# -V5_0.net
KiCad netlist of a schematic drawn in Altium Designer
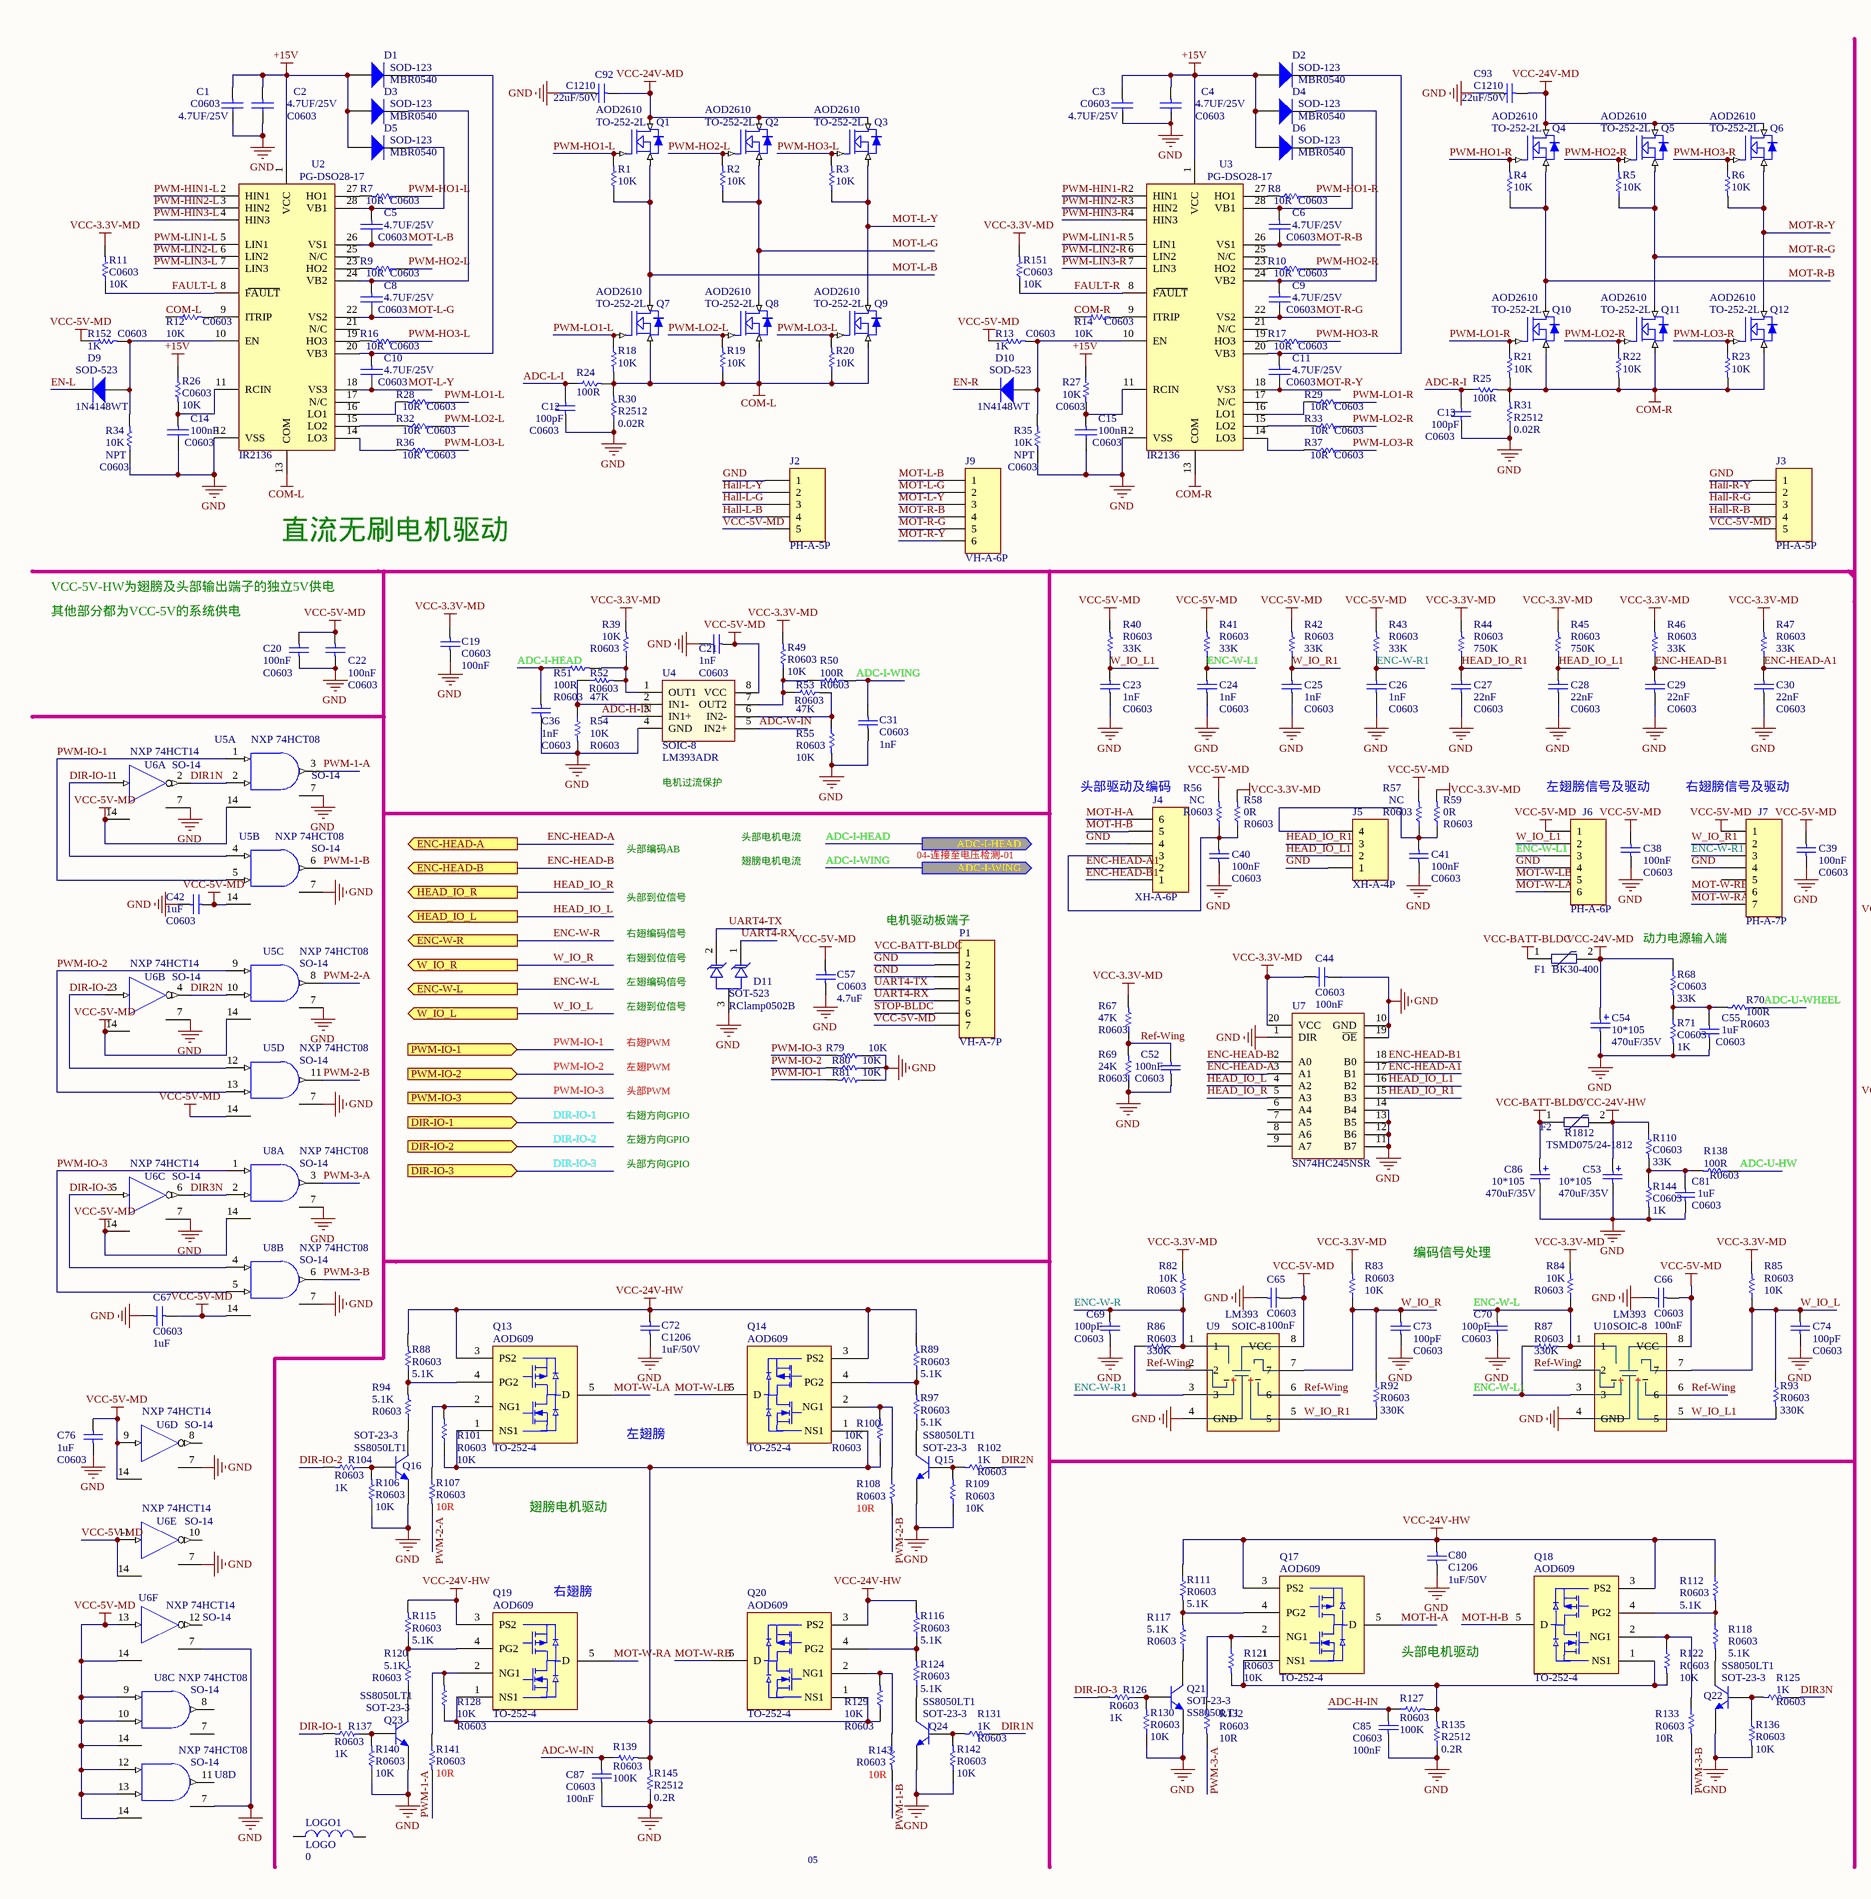
[diagram p0: 电机驱动板-V5.0.SchDoc, left]
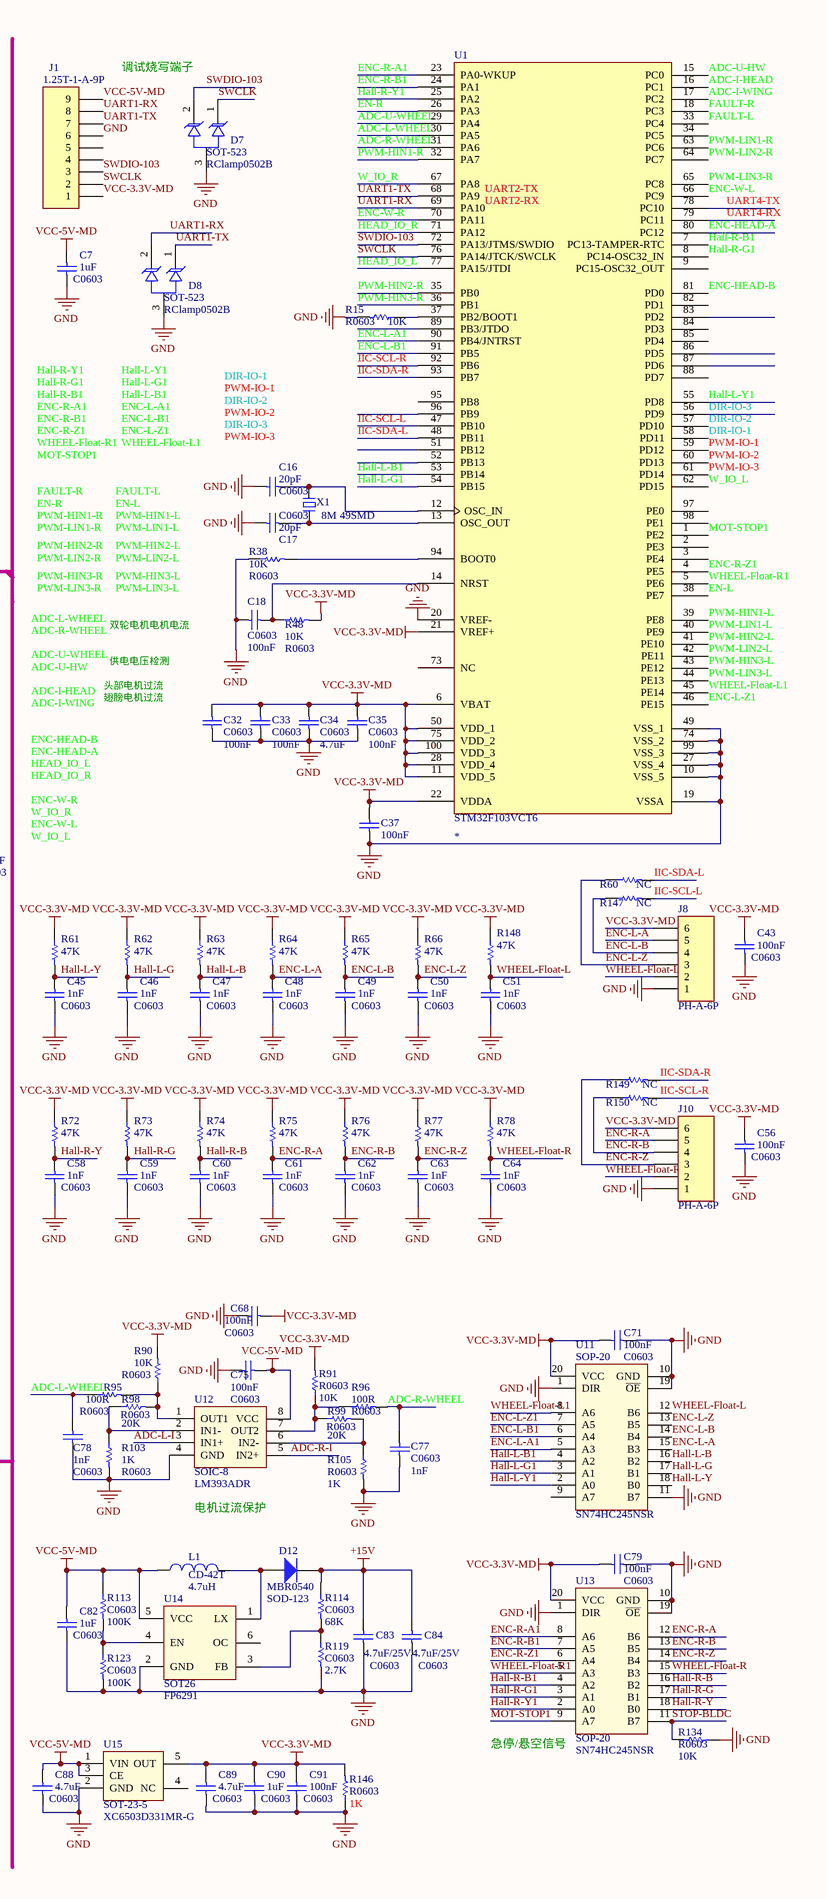
[diagram p1: 电机驱动板-V5.0.SchDoc, right]

(export (version "E")
  (design (tool "Eeschema 10.0.6"))
  (components
    (comp (ref "C1")
      (value "C0603")
      (footprint "C0603_M1608")
      (description "Capacitor")
      (fields (field (name "ALTIUM_VALUE") "4.7UF/25V"))
      (libsource (lib "*") (part "CAP"))
    )
    (comp (ref "C2")
      (value "C0603")
      (footprint "C0603_M1608")
      (description "Capacitor")
      (fields (field (name "ALTIUM_VALUE") "4.7UF/25V"))
      (libsource (lib "*") (part "CAP"))
    )
    (comp (ref "C3")
      (value "C0603")
      (footprint "C0603_M1608")
      (description "Capacitor")
      (fields (field (name "ALTIUM_VALUE") "4.7UF/25V"))
      (libsource (lib "*") (part "CAP"))
    )
    (comp (ref "C4")
      (value "C0603")
      (footprint "C0603_M1608")
      (description "Capacitor")
      (fields (field (name "ALTIUM_VALUE") "4.7UF/25V"))
      (libsource (lib "*") (part "CAP"))
    )
    (comp (ref "C5")
      (value "C0603")
      (footprint "C0603_M1608")
      (description "Capacitor")
      (fields (field (name "ALTIUM_VALUE") "4.7UF/25V"))
      (libsource (lib "*") (part "CAP"))
    )
    (comp (ref "C6")
      (value "C0603")
      (footprint "C0603_M1608")
      (description "Capacitor")
      (fields (field (name "ALTIUM_VALUE") "4.7UF/25V"))
      (libsource (lib "*") (part "CAP"))
    )
    (comp (ref "C7")
      (value "C0603")
      (footprint "C0603_M1608")
      (description "Capacitor")
      (fields (field (name "ALTIUM_VALUE") "1uF"))
      (libsource (lib "Miscellaneous Devices") (part "Cap"))
    )
    (comp (ref "C8")
      (value "C0603")
      (footprint "C0603_M1608")
      (description "Capacitor")
      (fields (field (name "ALTIUM_VALUE") "4.7UF/25V"))
      (libsource (lib "*") (part "CAP"))
    )
    (comp (ref "C9")
      (value "C0603")
      (footprint "C0603_M1608")
      (description "Capacitor")
      (fields (field (name "ALTIUM_VALUE") "4.7UF/25V"))
      (libsource (lib "*") (part "CAP"))
    )
    (comp (ref "C10")
      (value "C0603")
      (footprint "C0603_M1608")
      (description "Capacitor")
      (fields (field (name "ALTIUM_VALUE") "4.7UF/25V"))
      (libsource (lib "*") (part "CAP"))
    )
    (comp (ref "C11")
      (value "C0603")
      (footprint "C0603_M1608")
      (description "Capacitor")
      (fields (field (name "ALTIUM_VALUE") "4.7UF/25V"))
      (libsource (lib "*") (part "CAP"))
    )
    (comp (ref "C12")
      (value "C0603")
      (footprint "C0603_M1608")
      (description "Multilayer Ceramic Capacitor 0603")
      (fields (field (name "ALTIUM_VALUE") "100pF"))
      (libsource (lib "1.电阻、电容、电感原理库") (part "MCC0603"))
    )
    (comp (ref "C13")
      (value "C0603")
      (footprint "C0603_M1608")
      (description "Multilayer Ceramic Capacitor 0603")
      (fields (field (name "ALTIUM_VALUE") "100pF"))
      (libsource (lib "1.电阻、电容、电感原理库") (part "MCC0603"))
    )
    (comp (ref "C14")
      (value "C0603")
      (footprint "C0603_M1608")
      (description "Capacitor")
      (fields (field (name "ALTIUM_VALUE") "100nF"))
      (libsource (lib "*") (part "CAP"))
    )
    (comp (ref "C15")
      (value "C0603")
      (footprint "C0603_M1608")
      (description "Capacitor")
      (fields (field (name "ALTIUM_VALUE") "100nF"))
      (libsource (lib "*") (part "CAP"))
    )
    (comp (ref "C16")
      (value "C0603")
      (footprint "C0603_M1608")
      (description "Multilayer Ceramic Capacitor 0603")
      (fields (field (name "ALTIUM_VALUE") "20pF"))
      (libsource (lib "1.电阻、电容、电感原理库") (part "MCC0603"))
    )
    (comp (ref "C17")
      (value "C0603")
      (footprint "C0603_M1608")
      (description "Multilayer Ceramic Capacitor 0603")
      (fields (field (name "ALTIUM_VALUE") "20pF"))
      (libsource (lib "1.电阻、电容、电感原理库") (part "MCC0603"))
    )
    (comp (ref "C18")
      (value "C0603")
      (footprint "C0603_M1608")
      (description "Multilayer Ceramic Capacitor 0603")
      (fields (field (name "ALTIUM_VALUE") "100nF"))
      (libsource (lib "1.电阻、电容、电感原理库") (part "MCC0603"))
    )
    (comp (ref "C19")
      (value "C0603")
      (footprint "C0603_M1608")
      (description "Multilayer Ceramic Capacitor 0603")
      (fields (field (name "ALTIUM_VALUE") "100nF"))
      (libsource (lib "1.电阻、电容、电感原理库") (part "MCC0603"))
    )
    (comp (ref "C20")
      (value "C0603")
      (footprint "C0603_M1608")
      (description "Multilayer Ceramic Capacitor 0603")
      (fields (field (name "ALTIUM_VALUE") "100nF"))
      (libsource (lib "1.电阻、电容、电感原理库") (part "MCC0603"))
    )
    (comp (ref "C21")
      (value "C0603")
      (footprint "C0603_M1608")
      (description "Multilayer Ceramic Capacitor 0603")
      (fields (field (name "ALTIUM_VALUE") "1nF"))
      (libsource (lib "1.电阻、电容、电感原理库") (part "MCC0603"))
    )
    (comp (ref "C22")
      (value "C0603")
      (footprint "C0603_M1608")
      (description "Multilayer Ceramic Capacitor 0603")
      (fields (field (name "ALTIUM_VALUE") "100nF"))
      (libsource (lib "1.电阻、电容、电感原理库") (part "MCC0603"))
    )
    (comp (ref "C23")
      (value "C0603")
      (footprint "C0603_M1608")
      (description "Multilayer Ceramic Capacitor 0603")
      (fields (field (name "ALTIUM_VALUE") "1nF"))
      (libsource (lib "1.电阻、电容、电感原理库") (part "MCC0603"))
    )
    (comp (ref "C24")
      (value "C0603")
      (footprint "C0603_M1608")
      (description "Multilayer Ceramic Capacitor 0603")
      (fields (field (name "ALTIUM_VALUE") "1nF"))
      (libsource (lib "1.电阻、电容、电感原理库") (part "MCC0603"))
    )
    (comp (ref "C25")
      (value "C0603")
      (footprint "C0603_M1608")
      (description "Multilayer Ceramic Capacitor 0603")
      (fields (field (name "ALTIUM_VALUE") "1nF"))
      (libsource (lib "1.电阻、电容、电感原理库") (part "MCC0603"))
    )
    (comp (ref "C26")
      (value "C0603")
      (footprint "C0603_M1608")
      (description "Multilayer Ceramic Capacitor 0603")
      (fields (field (name "ALTIUM_VALUE") "1nF"))
      (libsource (lib "1.电阻、电容、电感原理库") (part "MCC0603"))
    )
    (comp (ref "C27")
      (value "C0603")
      (footprint "C0603_M1608")
      (description "Multilayer Ceramic Capacitor 0603")
      (fields (field (name "ALTIUM_VALUE") "22nF"))
      (libsource (lib "1.电阻、电容、电感原理库") (part "MCC0603"))
    )
    (comp (ref "C28")
      (value "C0603")
      (footprint "C0603_M1608")
      (description "Multilayer Ceramic Capacitor 0603")
      (fields (field (name "ALTIUM_VALUE") "22nF"))
      (libsource (lib "1.电阻、电容、电感原理库") (part "MCC0603"))
    )
    (comp (ref "C29")
      (value "C0603")
      (footprint "C0603_M1608")
      (description "Multilayer Ceramic Capacitor 0603")
      (fields (field (name "ALTIUM_VALUE") "22nF"))
      (libsource (lib "1.电阻、电容、电感原理库") (part "MCC0603"))
    )
    (comp (ref "C30")
      (value "C0603")
      (footprint "C0603_M1608")
      (description "Multilayer Ceramic Capacitor 0603")
      (fields (field (name "ALTIUM_VALUE") "22nF"))
      (libsource (lib "1.电阻、电容、电感原理库") (part "MCC0603"))
    )
    (comp (ref "C31")
      (value "C0603")
      (footprint "C0603_M1608")
      (description "Multilayer Ceramic Capacitor 0603")
      (fields (field (name "ALTIUM_VALUE") "1nF"))
      (libsource (lib "1.电阻、电容、电感原理库") (part "MCC0603"))
    )
    (comp (ref "C32")
      (value "C0603")
      (footprint "C0603_M1608")
      (description "Multilayer Ceramic Capacitor 0603")
      (fields (field (name "ALTIUM_VALUE") "100nF"))
      (libsource (lib "1.电阻、电容、电感原理库") (part "MCC0603"))
    )
    (comp (ref "C33")
      (value "C0603")
      (footprint "C0603_M1608")
      (description "Multilayer Ceramic Capacitor 0603")
      (fields (field (name "ALTIUM_VALUE") "100nF"))
      (libsource (lib "1.电阻、电容、电感原理库") (part "MCC0603"))
    )
    (comp (ref "C34")
      (value "C0603")
      (footprint "C0603_M1608")
      (description "Multilayer Ceramic Capacitor 0603")
      (fields (field (name "ALTIUM_VALUE") "4.7uF"))
      (libsource (lib "1.电阻、电容、电感原理库") (part "MCC0603"))
    )
    (comp (ref "C35")
      (value "C0603")
      (footprint "C0603_M1608")
      (description "Multilayer Ceramic Capacitor 0603")
      (fields (field (name "ALTIUM_VALUE") "100nF"))
      (libsource (lib "1.电阻、电容、电感原理库") (part "MCC0603"))
    )
    (comp (ref "C36")
      (value "C0603")
      (footprint "C0603_M1608")
      (description "Multilayer Ceramic Capacitor 0603")
      (fields (field (name "ALTIUM_VALUE") "1nF"))
      (libsource (lib "1.电阻、电容、电感原理库") (part "MCC0603"))
    )
    (comp (ref "C37")
      (value "100nF")
      (footprint "C0603_M1608")
      (description "Capacitor")
      (fields (field (name "Comment") "C0603"))
      (libsource (lib "") (part "Cap_1"))
    )
    (comp (ref "C38")
      (value "C0603")
      (footprint "C0603_M1608")
      (description "Multilayer Ceramic Capacitor 0603")
      (fields (field (name "ALTIUM_VALUE") "100nF"))
      (libsource (lib "1.电阻、电容、电感原理库") (part "MCC0603"))
    )
    (comp (ref "C39")
      (value "C0603")
      (footprint "C0603_M1608")
      (description "Multilayer Ceramic Capacitor 0603")
      (fields (field (name "ALTIUM_VALUE") "100nF"))
      (libsource (lib "1.电阻、电容、电感原理库") (part "MCC0603"))
    )
    (comp (ref "C40")
      (value "C0603")
      (footprint "C0603_M1608")
      (description "Multilayer Ceramic Capacitor 0603")
      (fields (field (name "ALTIUM_VALUE") "100nF"))
      (libsource (lib "1.电阻、电容、电感原理库") (part "MCC0603"))
    )
    (comp (ref "C41")
      (value "C0603")
      (footprint "C0603_M1608")
      (description "Multilayer Ceramic Capacitor 0603")
      (fields (field (name "ALTIUM_VALUE") "100nF"))
      (libsource (lib "1.电阻、电容、电感原理库") (part "MCC0603"))
    )
    (comp (ref "C42")
      (value "C0603")
      (footprint "C0603_M1608")
      (description "Capacitor")
      (fields (field (name "ALTIUM_VALUE") "1uF") (field (name "PUBLISHER") "Altium Limited"))
      (libsource (lib "Miscellaneous Devices") (part "Cap"))
    )
    (comp (ref "C43")
      (value "C0603")
      (footprint "C0603_M1608")
      (description "Multilayer Ceramic Capacitor 0603")
      (fields (field (name "ALTIUM_VALUE") "100nF"))
      (libsource (lib "1.电阻、电容、电感原理库") (part "MCC0603"))
    )
    (comp (ref "C44")
      (value "C0603")
      (footprint "C0603_M1608")
      (description "Multilayer Ceramic Capacitor 0603")
      (fields (field (name "ALTIUM_VALUE") "100nF"))
      (libsource (lib "1.电阻、电容、电感原理库") (part "MCC0603"))
    )
    (comp (ref "C45")
      (value "C0603")
      (footprint "C0603_M1608")
      (description "Multilayer Ceramic Capacitor 0603")
      (fields (field (name "ALTIUM_VALUE") "1nF"))
      (libsource (lib "1.电阻、电容、电感原理库") (part "MCC0603"))
    )
    (comp (ref "C46")
      (value "C0603")
      (footprint "C0603_M1608")
      (description "Multilayer Ceramic Capacitor 0603")
      (fields (field (name "ALTIUM_VALUE") "1nF"))
      (libsource (lib "1.电阻、电容、电感原理库") (part "MCC0603"))
    )
    (comp (ref "C47")
      (value "C0603")
      (footprint "C0603_M1608")
      (description "Multilayer Ceramic Capacitor 0603")
      (fields (field (name "ALTIUM_VALUE") "1nF"))
      (libsource (lib "1.电阻、电容、电感原理库") (part "MCC0603"))
    )
    (comp (ref "C48")
      (value "C0603")
      (footprint "C0603_M1608")
      (description "Multilayer Ceramic Capacitor 0603")
      (fields (field (name "ALTIUM_VALUE") "1nF"))
      (libsource (lib "1.电阻、电容、电感原理库") (part "MCC0603"))
    )
    (comp (ref "C49")
      (value "C0603")
      (footprint "C0603_M1608")
      (description "Multilayer Ceramic Capacitor 0603")
      (fields (field (name "ALTIUM_VALUE") "1nF"))
      (libsource (lib "1.电阻、电容、电感原理库") (part "MCC0603"))
    )
    (comp (ref "C50")
      (value "C0603")
      (footprint "C0603_M1608")
      (description "Multilayer Ceramic Capacitor 0603")
      (fields (field (name "ALTIUM_VALUE") "1nF"))
      (libsource (lib "1.电阻、电容、电感原理库") (part "MCC0603"))
    )
    (comp (ref "C51")
      (value "C0603")
      (footprint "C0603_M1608")
      (description "Multilayer Ceramic Capacitor 0603")
      (fields (field (name "ALTIUM_VALUE") "1nF"))
      (libsource (lib "1.电阻、电容、电感原理库") (part "MCC0603"))
    )
    (comp (ref "C52")
      (value "C0603")
      (footprint "C0603_M1608")
      (description "Multilayer Ceramic Capacitor 0603")
      (fields (field (name "ALTIUM_VALUE") "100nF"))
      (libsource (lib "1.电阻、电容、电感原理库") (part "MCC0603"))
    )
    (comp (ref "C53")
      (value "10*105")
      (footprint "CAP_SMD_10*105")
      (description "SMD Capacitor 10*105")
      (fields (field (name "ALTIUM_VALUE") "470uF/35V"))
      (libsource (lib "1.电阻、电容、电感原理库") (part "CAP_SMD_10*105"))
    )
    (comp (ref "C54")
      (value "10*105")
      (footprint "CAP_SMD_10*105")
      (description "SMD Capacitor 10*105")
      (fields (field (name "ALTIUM_VALUE") "470uF/35V"))
      (libsource (lib "1.电阻、电容、电感原理库") (part "CAP_SMD_10*105"))
    )
    (comp (ref "C55")
      (value "C0603")
      (footprint "C0603_M1608")
      (description "Multilayer Ceramic Capacitor 0603")
      (fields (field (name "ALTIUM_VALUE") "1uF"))
      (libsource (lib "1.电阻、电容、电感原理库") (part "MCC0603"))
    )
    (comp (ref "C56")
      (value "C0603")
      (footprint "C0603_M1608")
      (description "Multilayer Ceramic Capacitor 0603")
      (fields (field (name "ALTIUM_VALUE") "100nF"))
      (libsource (lib "1.电阻、电容、电感原理库") (part "MCC0603"))
    )
    (comp (ref "C57")
      (value "C0603")
      (footprint "C0603_M1608")
      (description "Capacitor")
      (fields (field (name "ALTIUM_VALUE") "4.7uF"))
      (libsource (lib "Miscellaneous Devices") (part "Cap"))
    )
    (comp (ref "C58")
      (value "C0603")
      (footprint "C0603_M1608")
      (description "Multilayer Ceramic Capacitor 0603")
      (fields (field (name "ALTIUM_VALUE") "1nF"))
      (libsource (lib "1.电阻、电容、电感原理库") (part "MCC0603"))
    )
    (comp (ref "C59")
      (value "C0603")
      (footprint "C0603_M1608")
      (description "Multilayer Ceramic Capacitor 0603")
      (fields (field (name "ALTIUM_VALUE") "1nF"))
      (libsource (lib "1.电阻、电容、电感原理库") (part "MCC0603"))
    )
    (comp (ref "C60")
      (value "C0603")
      (footprint "C0603_M1608")
      (description "Multilayer Ceramic Capacitor 0603")
      (fields (field (name "ALTIUM_VALUE") "1nF"))
      (libsource (lib "1.电阻、电容、电感原理库") (part "MCC0603"))
    )
    (comp (ref "C61")
      (value "C0603")
      (footprint "C0603_M1608")
      (description "Multilayer Ceramic Capacitor 0603")
      (fields (field (name "ALTIUM_VALUE") "1nF"))
      (libsource (lib "1.电阻、电容、电感原理库") (part "MCC0603"))
    )
    (comp (ref "C62")
      (value "C0603")
      (footprint "C0603_M1608")
      (description "Multilayer Ceramic Capacitor 0603")
      (fields (field (name "ALTIUM_VALUE") "1nF"))
      (libsource (lib "1.电阻、电容、电感原理库") (part "MCC0603"))
    )
    (comp (ref "C63")
      (value "C0603")
      (footprint "C0603_M1608")
      (description "Multilayer Ceramic Capacitor 0603")
      (fields (field (name "ALTIUM_VALUE") "1nF"))
      (libsource (lib "1.电阻、电容、电感原理库") (part "MCC0603"))
    )
    (comp (ref "C64")
      (value "C0603")
      (footprint "C0603_M1608")
      (description "Multilayer Ceramic Capacitor 0603")
      (fields (field (name "ALTIUM_VALUE") "1nF"))
      (libsource (lib "1.电阻、电容、电感原理库") (part "MCC0603"))
    )
    (comp (ref "C65")
      (value "C0603")
      (footprint "C0603_M1608")
      (description "Multilayer Ceramic Capacitor 0603")
      (fields (field (name "ALTIUM_VALUE") "100nF"))
      (libsource (lib "1.电阻、电容、电感原理库") (part "MCC0603"))
    )
    (comp (ref "C66")
      (value "C0603")
      (footprint "C0603_M1608")
      (description "Multilayer Ceramic Capacitor 0603")
      (fields (field (name "ALTIUM_VALUE") "100nF"))
      (libsource (lib "1.电阻、电容、电感原理库") (part "MCC0603"))
    )
    (comp (ref "C67")
      (value "C0603")
      (footprint "C0603_M1608")
      (description "Capacitor")
      (fields (field (name "ALTIUM_VALUE") "1uF") (field (name "PUBLISHER") "Altium Limited"))
      (libsource (lib "Miscellaneous Devices") (part "Cap"))
    )
    (comp (ref "C68")
      (value "C0603")
      (footprint "C0603_M1608")
      (description "Multilayer Ceramic Capacitor 0603")
      (fields (field (name "ALTIUM_VALUE") "100nF"))
      (libsource (lib "1.电阻、电容、电感原理库") (part "MCC0603"))
    )
    (comp (ref "C69")
      (value "C0603")
      (footprint "C0603_M1608")
      (description "Multilayer Ceramic Capacitor 0603")
      (fields (field (name "ALTIUM_VALUE") "100pF"))
      (libsource (lib "1.电阻、电容、电感原理库") (part "MCC0603"))
    )
    (comp (ref "C70")
      (value "C0603")
      (footprint "C0603_M1608")
      (description "Multilayer Ceramic Capacitor 0603")
      (fields (field (name "ALTIUM_VALUE") "100pF"))
      (libsource (lib "1.电阻、电容、电感原理库") (part "MCC0603"))
    )
    (comp (ref "C71")
      (value "C0603")
      (footprint "C0603_M1608")
      (description "Multilayer Ceramic Capacitor 0603")
      (fields (field (name "ALTIUM_VALUE") "100nF"))
      (libsource (lib "1.电阻、电容、电感原理库") (part "MCC0603"))
    )
    (comp (ref "C72")
      (value "C1206")
      (footprint "C1206_M3216")
      (description "Multilayer Ceramic Capacitor 1206")
      (fields (field (name "ALTIUM_VALUE") "1uF/50V"))
      (libsource (lib "1.电阻、电容、电感原理库") (part "MCC1206"))
    )
    (comp (ref "C73")
      (value "C0603")
      (footprint "C0603_M1608")
      (description "Multilayer Ceramic Capacitor 0603")
      (fields (field (name "ALTIUM_VALUE") "100pF"))
      (libsource (lib "1.电阻、电容、电感原理库") (part "MCC0603"))
    )
    (comp (ref "C74")
      (value "C0603")
      (footprint "C0603_M1608")
      (description "Multilayer Ceramic Capacitor 0603")
      (fields (field (name "ALTIUM_VALUE") "100pF"))
      (libsource (lib "1.电阻、电容、电感原理库") (part "MCC0603"))
    )
    (comp (ref "C75")
      (value "C0603")
      (footprint "C0603_M1608")
      (description "Multilayer Ceramic Capacitor 0603")
      (fields (field (name "ALTIUM_VALUE") "100nF"))
      (libsource (lib "1.电阻、电容、电感原理库") (part "MCC0603"))
    )
    (comp (ref "C76")
      (value "C0603")
      (footprint "C0603_M1608")
      (description "Capacitor")
      (fields (field (name "ALTIUM_VALUE") "1uF") (field (name "PUBLISHER") "Altium Limited"))
      (libsource (lib "Miscellaneous Devices") (part "Cap"))
    )
    (comp (ref "C77")
      (value "C0603")
      (footprint "C0603_M1608")
      (description "Multilayer Ceramic Capacitor 0603")
      (fields (field (name "ALTIUM_VALUE") "1nF"))
      (libsource (lib "1.电阻、电容、电感原理库") (part "MCC0603"))
    )
    (comp (ref "C78")
      (value "C0603")
      (footprint "C0603_M1608")
      (description "Multilayer Ceramic Capacitor 0603")
      (fields (field (name "ALTIUM_VALUE") "1nF"))
      (libsource (lib "1.电阻、电容、电感原理库") (part "MCC0603"))
    )
    (comp (ref "C79")
      (value "C0603")
      (footprint "C0603_M1608")
      (description "Multilayer Ceramic Capacitor 0603")
      (fields (field (name "ALTIUM_VALUE") "100nF"))
      (libsource (lib "1.电阻、电容、电感原理库") (part "MCC0603"))
    )
    (comp (ref "C80")
      (value "C1206")
      (footprint "C1206_M3216")
      (description "Multilayer Ceramic Capacitor 1206")
      (fields (field (name "ALTIUM_VALUE") "1uF/50V"))
      (libsource (lib "1.电阻、电容、电感原理库") (part "MCC1206"))
    )
    (comp (ref "C81")
      (value "C0603")
      (footprint "C0603_M1608")
      (description "Multilayer Ceramic Capacitor 0603")
      (fields (field (name "ALTIUM_VALUE") "1uF"))
      (libsource (lib "1.电阻、电容、电感原理库") (part "MCC0603"))
    )
    (comp (ref "C82")
      (value "C0603")
      (footprint "C0603_M1608")
      (description "Multilayer Ceramic Capacitor 0603")
      (fields (field (name "ALTIUM_VALUE") "1uF"))
      (libsource (lib "1.电阻、电容、电感原理库") (part "MCC0603"))
    )
    (comp (ref "C83")
      (value "C0603")
      (footprint "C0603_M1608")
      (description "Capacitor")
      (fields (field (name "ALTIUM_VALUE") "4.7uF/25V") (field (name "PUBLISHER") "Altium Limited"))
      (libsource (lib "Miscellaneous Devices") (part "Cap"))
    )
    (comp (ref "C84")
      (value "C0603")
      (footprint "C0603_M1608")
      (description "Capacitor")
      (fields (field (name "ALTIUM_VALUE") "4.7uF/25V"))
      (libsource (lib "Miscellaneous Devices") (part "Cap"))
    )
    (comp (ref "C85")
      (value "C0603")
      (footprint "C0603_M1608")
      (description "Capacitor")
      (fields (field (name "ALTIUM_VALUE") "100nF") (field (name "PUBLISHER") "Altium Limited"))
      (libsource (lib "Miscellaneous Devices") (part "Cap"))
    )
    (comp (ref "C86")
      (value "10*105")
      (footprint "CAP_SMD_10*105")
      (description "SMD Capacitor 10*105")
      (fields (field (name "ALTIUM_VALUE") "470uF/35V"))
      (libsource (lib "1.电阻、电容、电感原理库") (part "CAP_SMD_10*105"))
    )
    (comp (ref "C87")
      (value "C0603")
      (footprint "C0603_M1608")
      (description "Capacitor")
      (fields (field (name "ALTIUM_VALUE") "100nF") (field (name "PUBLISHER") "Altium Limited"))
      (libsource (lib "Miscellaneous Devices") (part "Cap"))
    )
    (comp (ref "C88")
      (value "C0603")
      (footprint "C0603_M1608")
      (description "Capacitor")
      (fields (field (name "ALTIUM_VALUE") "4.7uF") (field (name "PUBLISHER") "Altium Limited"))
      (libsource (lib "Miscellaneous Devices") (part "Cap"))
    )
    (comp (ref "C89")
      (value "C0603")
      (footprint "C0603_M1608")
      (description "Capacitor")
      (fields (field (name "ALTIUM_VALUE") "4.7uF"))
      (libsource (lib "Miscellaneous Devices") (part "Cap"))
    )
    (comp (ref "C90")
      (value "C0603")
      (footprint "C0603_M1608")
      (description "Capacitor")
      (fields (field (name "ALTIUM_VALUE") "1uF"))
      (libsource (lib "Miscellaneous Devices") (part "Cap"))
    )
    (comp (ref "C91")
      (value "C0603")
      (footprint "C0603_M1608")
      (description "Capacitor")
      (fields (field (name "ALTIUM_VALUE") "100nF"))
      (libsource (lib "Miscellaneous Devices") (part "Cap"))
    )
    (comp (ref "C92")
      (value "C1210")
      (footprint "C1210_M3225")
      (description "Multilayer Ceramic Capacitor 0603")
      (fields (field (name "ALTIUM_VALUE") "22uF/50V"))
      (libsource (lib "1.电阻、电容、电感原理库") (part "MCC0603"))
    )
    (comp (ref "C93")
      (value "C1210")
      (footprint "C1210_M3225")
      (description "Multilayer Ceramic Capacitor 0603")
      (fields (field (name "ALTIUM_VALUE") "22uF/50V"))
      (libsource (lib "1.电阻、电容、电感原理库") (part "MCC0603"))
    )
    (comp (ref "D1")
      (value "SOD-123")
      (footprint "SOD-123")
      (description "Default Diode")
      (fields (field (name "ALTIUM_VALUE") "MBR0540") (field (name "PUBLISHER") "Altium Limited"))
      (libsource (lib "Miscellaneous Devices") (part "Diode"))
    )
    (comp (ref "D2")
      (value "SOD-123")
      (footprint "SOD-123")
      (description "Default Diode")
      (fields (field (name "ALTIUM_VALUE") "MBR0540") (field (name "PUBLISHER") "Altium Limited"))
      (libsource (lib "Miscellaneous Devices") (part "Diode"))
    )
    (comp (ref "D3")
      (value "SOD-123")
      (footprint "SOD-123")
      (description "Default Diode")
      (fields (field (name "ALTIUM_VALUE") "MBR0540") (field (name "PUBLISHER") "Altium Limited"))
      (libsource (lib "Miscellaneous Devices") (part "Diode"))
    )
    (comp (ref "D4")
      (value "SOD-123")
      (footprint "SOD-123")
      (description "Default Diode")
      (fields (field (name "ALTIUM_VALUE") "MBR0540") (field (name "PUBLISHER") "Altium Limited"))
      (libsource (lib "Miscellaneous Devices") (part "Diode"))
    )
    (comp (ref "D5")
      (value "SOD-123")
      (footprint "SOD-123")
      (description "Default Diode")
      (fields (field (name "ALTIUM_VALUE") "MBR0540") (field (name "PUBLISHER") "Altium Limited"))
      (libsource (lib "Miscellaneous Devices") (part "Diode"))
    )
    (comp (ref "D6")
      (value "SOD-123")
      (footprint "SOD-123")
      (description "Default Diode")
      (fields (field (name "ALTIUM_VALUE") "MBR0540") (field (name "PUBLISHER") "Altium Limited"))
      (libsource (lib "Miscellaneous Devices") (part "Diode"))
    )
    (comp (ref "D7")
      (value "SOT-523")
      (footprint "SOT-523")
      (description "Ultra-Low Capacitance TVS for ESD and CDE Protection")
      (fields (field (name "ALTIUM_VALUE") "RClamp0502B"))
      (libsource (lib "2.二极管原理库") (part "RClamp0502B"))
    )
    (comp (ref "D8")
      (value "SOT-523")
      (footprint "SOT-523")
      (description "Ultra-Low Capacitance TVS for ESD and CDE Protection")
      (fields (field (name "ALTIUM_VALUE") "RClamp0502B"))
      (libsource (lib "2.二极管原理库") (part "RClamp0502B"))
    )
    (comp (ref "D9")
      (value "SOD-523")
      (footprint "SOD-523")
      (description "FAST SWITCHING DIODES")
      (fields (field (name "ALTIUM_VALUE") "1N4148WT"))
      (libsource (lib "2.二极管原理库") (part "1N4148WT"))
    )
    (comp (ref "D10")
      (value "SOD-523")
      (footprint "SOD-523")
      (description "FAST SWITCHING DIODES")
      (fields (field (name "ALTIUM_VALUE") "1N4148WT"))
      (libsource (lib "2.二极管原理库") (part "1N4148WT"))
    )
    (comp (ref "D11")
      (value "SOT-523")
      (footprint "SOT-523")
      (description "Ultra-Low Capacitance TVS for ESD and CDE Protection")
      (fields (field (name "ALTIUM_VALUE") "RClamp0502B"))
      (libsource (lib "2.二极管原理库") (part "RClamp0502B"))
    )
    (comp (ref "D12")
      (value "SOD-123")
      (footprint "SOD-123")
      (description "Default Diode")
      (fields (field (name "ALTIUM_VALUE") "MBR0540") (field (name "PUBLISHER") "Altium Limited"))
      (libsource (lib "Miscellaneous Devices") (part "Diode"))
    )
    (comp (ref "F1") (value "BK30-400") (footprint "FUSE-FRG-5MM") (libsource (lib "SCH") (part "PPTC")))
    (comp (ref "F2")
      (value "R1812")
      (footprint "R1812_M4532")
      (fields (field (name "ALTIUM_VALUE") "TSMD075/24-1812"))
      (libsource (lib "SCH") (part "PPTC"))
    )
    (comp (ref "J1")
      (value "1.25T-1-A-9P")
      (footprint "1.25T-1-A-9P")
      (description "Header, 1.25mm,9-Pin")
      (libsource (lib "7.PH XH VH KF2510连接器原理库") (part "1.25T-1-A-9P"))
    )
    (comp (ref "J2")
      (value "PH-A-5P")
      (footprint "PH-A-5P")
      (description "Header, 2.0mm,5-Pin")
      (libsource (lib "7.PH XH VH KF2510连接器原理库") (part "PH-A-5P"))
    )
    (comp (ref "J3")
      (value "PH-A-5P")
      (footprint "PH-A-5P")
      (description "Header, 2.0mm,5-Pin")
      (libsource (lib "7.PH XH VH KF2510连接器原理库") (part "PH-A-5P"))
    )
    (comp (ref "J4")
      (value "XH-A-6P")
      (footprint "XH-A-6P")
      (description "Header, 2.5mm,6-Pin")
      (libsource (lib "7.PH XH VH KF2510连接器原理库") (part "XH-A-6P"))
    )
    (comp (ref "J5")
      (value "XH-A-4P")
      (footprint "XH-A-4P")
      (description "Header, 2.5mm,4-Pin")
      (libsource (lib "7.PH XH VH KF2510连接器原理库") (part "XH-A-4P"))
    )
    (comp (ref "J6")
      (value "PH-A-6P")
      (footprint "PH-A-6P")
      (description "Header, 2.0mm,6-Pin")
      (libsource (lib "") (part "PH-A-6P_1"))
    )
    (comp (ref "J7")
      (value "PH-A-7P")
      (footprint "PH-A-7P")
      (description "Header, 2.0mm,7-Pin")
      (libsource (lib "7.PH XH VH KF2510连接器原理库") (part "PH-A-7P"))
    )
    (comp (ref "J8")
      (value "PH-A-6P")
      (footprint "PH-A-6P")
      (description "Header, 2.0mm,6-Pin")
      (libsource (lib "7.PH XH VH KF2510连接器原理库") (part "PH-A-6P"))
    )
    (comp (ref "J9")
      (value "VH-A-6P")
      (footprint "VH-A-6P")
      (description "Header, 3.96mm,6-Pin")
      (libsource (lib "7.PH XH VH KF2510连接器原理库") (part "VH-A-6P"))
    )
    (comp (ref "J10")
      (value "PH-A-6P")
      (footprint "PH-A-6P")
      (description "Header, 2.0mm,6-Pin")
      (libsource (lib "7.PH XH VH KF2510连接器原理库") (part "PH-A-6P"))
    )
    (comp (ref "L1")
      (value "CD-42T")
      (footprint "CD-42T")
      (description "Inductor")
      (fields (field (name "ALTIUM_VALUE") "4.7uH"))
      (libsource (lib "1.电阻、电容、电感原理库") (part "L3*3*2-3A"))
    )
    (comp (ref "LOGO1")
      (value "LOGO")
      (footprint "LOGO")
      (description "Inductor CD54 Type")
      (fields (field (name "ALTIUM_VALUE") "0"))
      (libsource (lib "1.电阻、电容、电感原理库") (part "L-CD54"))
    )
    (comp (ref "P1")
      (value "VH-A-7P")
      (footprint "VH-A-7P")
      (description "Header, 3.96mm,7-Pin")
      (libsource (lib "7.PH XH VH KF2510连接器原理库") (part "VH-A-7P"))
    )
    (comp (ref "Q1")
      (value "TO-252-2L")
      (footprint "TO-252-2L")
      (fields (field (name "ALTIUM_VALUE") "AOD2610"))
      (libsource (lib "SCH-S") (part "MOSN_1"))
    )
    (comp (ref "Q2")
      (value "TO-252-2L")
      (footprint "TO-252-2L")
      (fields (field (name "ALTIUM_VALUE") "AOD2610"))
      (libsource (lib "SCH-S") (part "MOSN_1"))
    )
    (comp (ref "Q3")
      (value "TO-252-2L")
      (footprint "TO-252-2L")
      (fields (field (name "ALTIUM_VALUE") "AOD2610"))
      (libsource (lib "SCH-S") (part "MOSN_1"))
    )
    (comp (ref "Q4")
      (value "TO-252-2L")
      (footprint "TO-252-2L")
      (fields (field (name "ALTIUM_VALUE") "AOD2610"))
      (libsource (lib "SCH-S") (part "MOSN_1"))
    )
    (comp (ref "Q5")
      (value "TO-252-2L")
      (footprint "TO-252-2L")
      (fields (field (name "ALTIUM_VALUE") "AOD2610"))
      (libsource (lib "SCH-S") (part "MOSN_1"))
    )
    (comp (ref "Q6")
      (value "TO-252-2L")
      (footprint "TO-252-2L")
      (fields (field (name "ALTIUM_VALUE") "AOD2610"))
      (libsource (lib "SCH-S") (part "MOSN_1"))
    )
    (comp (ref "Q7")
      (value "TO-252-2L")
      (footprint "TO-252-2L")
      (fields (field (name "ALTIUM_VALUE") "AOD2610"))
      (libsource (lib "SCH-S") (part "MOSN_1"))
    )
    (comp (ref "Q8")
      (value "TO-252-2L")
      (footprint "TO-252-2L")
      (fields (field (name "ALTIUM_VALUE") "AOD2610"))
      (libsource (lib "SCH-S") (part "MOSN_1"))
    )
    (comp (ref "Q9")
      (value "TO-252-2L")
      (footprint "TO-252-2L")
      (fields (field (name "ALTIUM_VALUE") "AOD2610"))
      (libsource (lib "SCH-S") (part "MOSN_1"))
    )
    (comp (ref "Q10")
      (value "TO-252-2L")
      (footprint "TO-252-2L")
      (fields (field (name "ALTIUM_VALUE") "AOD2610"))
      (libsource (lib "SCH-S") (part "MOSN_1"))
    )
    (comp (ref "Q11")
      (value "TO-252-2L")
      (footprint "TO-252-2L")
      (fields (field (name "ALTIUM_VALUE") "AOD2610"))
      (libsource (lib "SCH-S") (part "MOSN_1"))
    )
    (comp (ref "Q12")
      (value "TO-252-2L")
      (footprint "TO-252-2L")
      (fields (field (name "ALTIUM_VALUE") "AOD2610"))
      (libsource (lib "SCH-S") (part "MOSN_1"))
    )
    (comp (ref "Q13")
      (value "TO-252-4")
      (footprint "TO-252-4L")
      (fields (field (name "ALTIUM_VALUE") "AOD609"))
      (libsource (lib "CYSchlib") (part "MOS-DUAL-N/P"))
    )
    (comp (ref "Q14")
      (value "TO-252-4")
      (footprint "TO-252-4L")
      (fields (field (name "ALTIUM_VALUE") "AOD609"))
      (libsource (lib "") (part "MOS-DUAL-N/P_1"))
    )
    (comp (ref "Q15")
      (value "SOT-23-3")
      (footprint "SOT-23-3")
      (description "NPN Bipolar Transistor")
      (fields (field (name "ALTIUM_VALUE") "SS8050LT1"))
      (libsource (lib "3.三极管原理库") (part "SS8050LT1"))
    )
    (comp (ref "Q16")
      (value "SOT-23-3")
      (footprint "SOT-23-3")
      (description "NPN Bipolar Transistor")
      (fields (field (name "ALTIUM_VALUE") "SS8050LT1"))
      (libsource (lib "3.三极管原理库") (part "SS8050LT1"))
    )
    (comp (ref "Q17")
      (value "TO-252-4")
      (footprint "TO-252-4L")
      (fields (field (name "ALTIUM_VALUE") "AOD609"))
      (libsource (lib "CYSchlib") (part "MOS-DUAL-N/P"))
    )
    (comp (ref "Q18")
      (value "TO-252-4")
      (footprint "TO-252-4L")
      (fields (field (name "ALTIUM_VALUE") "AOD609"))
      (libsource (lib "") (part "MOS-DUAL-N/P_1"))
    )
    (comp (ref "Q19")
      (value "TO-252-4")
      (footprint "TO-252-4L")
      (fields (field (name "ALTIUM_VALUE") "AOD609"))
      (libsource (lib "CYSchlib") (part "MOS-DUAL-N/P"))
    )
    (comp (ref "Q20")
      (value "TO-252-4")
      (footprint "TO-252-4L")
      (fields (field (name "ALTIUM_VALUE") "AOD609"))
      (libsource (lib "") (part "MOS-DUAL-N/P_1"))
    )
    (comp (ref "Q21")
      (value "SOT-23-3")
      (footprint "SOT-23-3")
      (description "NPN Bipolar Transistor")
      (fields (field (name "ALTIUM_VALUE") "SS8050LT1"))
      (libsource (lib "3.三极管原理库") (part "SS8050LT1"))
    )
    (comp (ref "Q22")
      (value "SOT-23-3")
      (footprint "SOT-23-3")
      (description "NPN Bipolar Transistor")
      (fields (field (name "ALTIUM_VALUE") "SS8050LT1"))
      (libsource (lib "3.三极管原理库") (part "SS8050LT1"))
    )
    (comp (ref "Q23")
      (value "SOT-23-3")
      (footprint "SOT-23-3")
      (description "NPN Bipolar Transistor")
      (fields (field (name "ALTIUM_VALUE") "SS8050LT1"))
      (libsource (lib "3.三极管原理库") (part "SS8050LT1"))
    )
    (comp (ref "Q24")
      (value "SOT-23-3")
      (footprint "SOT-23-3")
      (description "NPN Bipolar Transistor")
      (fields (field (name "ALTIUM_VALUE") "SS8050LT1"))
      (libsource (lib "3.三极管原理库") (part "SS8050LT1"))
    )
    (comp (ref "R1")
      (value "10K")
      (footprint "R0603_M1608")
      (description "Resistor")
      (fields (field (name "PUBLISHER") "Altium Limited"))
      (libsource (lib "Miscellaneous Devices") (part "Res1"))
    )
    (comp (ref "R2")
      (value "10K")
      (footprint "R0603_M1608")
      (description "Resistor")
      (fields (field (name "PUBLISHER") "Altium Limited"))
      (libsource (lib "Miscellaneous Devices") (part "Res1"))
    )
    (comp (ref "R3")
      (value "10K")
      (footprint "R0603_M1608")
      (description "Resistor")
      (fields (field (name "PUBLISHER") "Altium Limited"))
      (libsource (lib "Miscellaneous Devices") (part "Res1"))
    )
    (comp (ref "R4")
      (value "10K")
      (footprint "R0603_M1608")
      (description "Resistor")
      (fields (field (name "PUBLISHER") "Altium Limited"))
      (libsource (lib "Miscellaneous Devices") (part "Res1"))
    )
    (comp (ref "R5")
      (value "10K")
      (footprint "R0603_M1608")
      (description "Resistor")
      (fields (field (name "PUBLISHER") "Altium Limited"))
      (libsource (lib "Miscellaneous Devices") (part "Res1"))
    )
    (comp (ref "R6")
      (value "10K")
      (footprint "R0603_M1608")
      (description "Resistor")
      (fields (field (name "PUBLISHER") "Altium Limited"))
      (libsource (lib "Miscellaneous Devices") (part "Res1"))
    )
    (comp (ref "R7")
      (value "C0603")
      (footprint "R0603_M1608")
      (description "Resistor")
      (fields (field (name "ALTIUM_VALUE") "10R"))
      (libsource (lib "Miscellaneous Devices") (part "Res1"))
    )
    (comp (ref "R8")
      (value "C0603")
      (footprint "R0603_M1608")
      (description "Resistor")
      (fields (field (name "ALTIUM_VALUE") "10R"))
      (libsource (lib "Miscellaneous Devices") (part "Res1"))
    )
    (comp (ref "R9")
      (value "C0603")
      (footprint "R0603_M1608")
      (description "Resistor")
      (fields (field (name "ALTIUM_VALUE") "10R"))
      (libsource (lib "Miscellaneous Devices") (part "Res1"))
    )
    (comp (ref "R10")
      (value "C0603")
      (footprint "R0603_M1608")
      (description "Resistor")
      (fields (field (name "ALTIUM_VALUE") "10R"))
      (libsource (lib "Miscellaneous Devices") (part "Res1"))
    )
    (comp (ref "R11")
      (value "C0603")
      (footprint "R0603_M1608")
      (description "Resistor")
      (fields (field (name "ALTIUM_VALUE") "10K"))
      (libsource (lib "Miscellaneous Devices") (part "Res1"))
    )
    (comp (ref "R12")
      (value "C0603")
      (footprint "R0603_M1608")
      (description "Resistor")
      (fields (field (name "ALTIUM_VALUE") "10K"))
      (libsource (lib "Miscellaneous Devices") (part "Res1"))
    )
    (comp (ref "R13")
      (value "C0603")
      (footprint "R0603_M1608")
      (description "Resistor")
      (fields (field (name "ALTIUM_VALUE") "1K"))
      (libsource (lib "Miscellaneous Devices") (part "Res1"))
    )
    (comp (ref "R14")
      (value "C0603")
      (footprint "R0603_M1608")
      (description "Resistor")
      (fields (field (name "ALTIUM_VALUE") "10K"))
      (libsource (lib "Miscellaneous Devices") (part "Res1"))
    )
    (comp (ref "R15")
      (value "R0603")
      (footprint "R0603_M1608")
      (description "Resistor")
      (fields (field (name "ALTIUM_VALUE") "10K"))
      (libsource (lib "1.电阻、电容、电感原理库") (part "R0603_M1608"))
    )
    (comp (ref "R16")
      (value "C0603")
      (footprint "R0603_M1608")
      (description "Resistor")
      (fields (field (name "ALTIUM_VALUE") "10R"))
      (libsource (lib "Miscellaneous Devices") (part "Res1"))
    )
    (comp (ref "R17")
      (value "C0603")
      (footprint "R0603_M1608")
      (description "Resistor")
      (fields (field (name "ALTIUM_VALUE") "10R"))
      (libsource (lib "Miscellaneous Devices") (part "Res1"))
    )
    (comp (ref "R18")
      (value "10K")
      (footprint "R0603_M1608")
      (description "Resistor")
      (fields (field (name "PUBLISHER") "Altium Limited"))
      (libsource (lib "Miscellaneous Devices") (part "Res1"))
    )
    (comp (ref "R19")
      (value "10K")
      (footprint "R0603_M1608")
      (description "Resistor")
      (fields (field (name "PUBLISHER") "Altium Limited"))
      (libsource (lib "Miscellaneous Devices") (part "Res1"))
    )
    (comp (ref "R20")
      (value "10K")
      (footprint "R0603_M1608")
      (description "Resistor")
      (fields (field (name "PUBLISHER") "Altium Limited"))
      (libsource (lib "Miscellaneous Devices") (part "Res1"))
    )
    (comp (ref "R21")
      (value "10K")
      (footprint "R0603_M1608")
      (description "Resistor")
      (fields (field (name "PUBLISHER") "Altium Limited"))
      (libsource (lib "Miscellaneous Devices") (part "Res1"))
    )
    (comp (ref "R22")
      (value "10K")
      (footprint "R0603_M1608")
      (description "Resistor")
      (fields (field (name "PUBLISHER") "Altium Limited"))
      (libsource (lib "Miscellaneous Devices") (part "Res1"))
    )
    (comp (ref "R23")
      (value "10K")
      (footprint "R0603_M1608")
      (description "Resistor")
      (fields (field (name "PUBLISHER") "Altium Limited"))
      (libsource (lib "Miscellaneous Devices") (part "Res1"))
    )
    (comp (ref "R24")
      (value "100R")
      (footprint "R0603_M1608")
      (description "Resistor")
      (fields (field (name "PUBLISHER") "Altium Limited"))
      (libsource (lib "Miscellaneous Devices") (part "Res1"))
    )
    (comp (ref "R25")
      (value "100R")
      (footprint "R0603_M1608")
      (description "Resistor")
      (fields (field (name "PUBLISHER") "Altium Limited"))
      (libsource (lib "Miscellaneous Devices") (part "Res1"))
    )
    (comp (ref "R26")
      (value "C0603")
      (footprint "R0603_M1608")
      (description "Resistor")
      (fields (field (name "ALTIUM_VALUE") "10K"))
      (libsource (lib "Miscellaneous Devices") (part "Res1"))
    )
    (comp (ref "R27")
      (value "C0603")
      (footprint "R0603_M1608")
      (description "Resistor")
      (fields (field (name "ALTIUM_VALUE") "10K"))
      (libsource (lib "Miscellaneous Devices") (part "Res1"))
    )
    (comp (ref "R28")
      (value "C0603")
      (footprint "R0603_M1608")
      (description "Resistor")
      (fields (field (name "ALTIUM_VALUE") "10R"))
      (libsource (lib "Miscellaneous Devices") (part "Res1"))
    )
    (comp (ref "R29")
      (value "C0603")
      (footprint "R0603_M1608")
      (description "Resistor")
      (fields (field (name "ALTIUM_VALUE") "10R"))
      (libsource (lib "Miscellaneous Devices") (part "Res1"))
    )
    (comp (ref "R30")
      (value "R2512")
      (footprint "R2512_M6332")
      (description "Resistor")
      (fields (field (name "ALTIUM_VALUE") "0.02R"))
      (libsource (lib "1.电阻、电容、电感原理库") (part "R2512_M6332"))
    )
    (comp (ref "R31")
      (value "R2512")
      (footprint "R2512_M6332")
      (description "Resistor")
      (fields (field (name "ALTIUM_VALUE") "0.02R"))
      (libsource (lib "1.电阻、电容、电感原理库") (part "R2512_M6332"))
    )
    (comp (ref "R32")
      (value "C0603")
      (footprint "R0603_M1608")
      (description "Resistor")
      (fields (field (name "ALTIUM_VALUE") "10R"))
      (libsource (lib "Miscellaneous Devices") (part "Res1"))
    )
    (comp (ref "R33")
      (value "C0603")
      (footprint "R0603_M1608")
      (description "Resistor")
      (fields (field (name "ALTIUM_VALUE") "10R"))
      (libsource (lib "Miscellaneous Devices") (part "Res1"))
    )
    (comp (ref "R34")
      (value "C0603")
      (footprint "R0603_M1608")
      (description "Resistor")
      (fields (field (name "ALTIUM_VALUE") "10K") (field (name "ALTIUM_UNNAMED_1") "NPT"))
      (libsource (lib "Miscellaneous Devices") (part "Res1"))
    )
    (comp (ref "R35")
      (value "C0603")
      (footprint "R0603_M1608")
      (description "Resistor")
      (fields (field (name "ALTIUM_VALUE") "10K") (field (name "ALTIUM_UNNAMED_1") "NPT"))
      (libsource (lib "Miscellaneous Devices") (part "Res1"))
    )
    (comp (ref "R36")
      (value "C0603")
      (footprint "R0603_M1608")
      (description "Resistor")
      (fields (field (name "ALTIUM_VALUE") "10R"))
      (libsource (lib "Miscellaneous Devices") (part "Res1"))
    )
    (comp (ref "R37")
      (value "C0603")
      (footprint "R0603_M1608")
      (description "Resistor")
      (fields (field (name "ALTIUM_VALUE") "10R"))
      (libsource (lib "Miscellaneous Devices") (part "Res1"))
    )
    (comp (ref "R38")
      (value "R0603")
      (footprint "R0603_M1608")
      (description "Resistor")
      (fields (field (name "ALTIUM_VALUE") "10K"))
      (libsource (lib "1.电阻、电容、电感原理库") (part "R0603_M1608"))
    )
    (comp (ref "R39")
      (value "R0603")
      (footprint "R0603_M1608")
      (description "Resistor")
      (fields (field (name "ALTIUM_VALUE") "10K"))
      (libsource (lib "1.电阻、电容、电感原理库") (part "R0603_M1608"))
    )
    (comp (ref "R40")
      (value "R0603")
      (footprint "R0603_M1608")
      (description "Resistor")
      (fields (field (name "ALTIUM_VALUE") "33K"))
      (libsource (lib "1.电阻、电容、电感原理库") (part "R0603_M1608"))
    )
    (comp (ref "R41")
      (value "R0603")
      (footprint "R0603_M1608")
      (description "Resistor")
      (fields (field (name "ALTIUM_VALUE") "33K"))
      (libsource (lib "1.电阻、电容、电感原理库") (part "R0603_M1608"))
    )
    (comp (ref "R42")
      (value "R0603")
      (footprint "R0603_M1608")
      (description "Resistor")
      (fields (field (name "ALTIUM_VALUE") "33K"))
      (libsource (lib "1.电阻、电容、电感原理库") (part "R0603_M1608"))
    )
    (comp (ref "R43")
      (value "R0603")
      (footprint "R0603_M1608")
      (description "Resistor")
      (fields (field (name "ALTIUM_VALUE") "33K"))
      (libsource (lib "1.电阻、电容、电感原理库") (part "R0603_M1608"))
    )
    (comp (ref "R44")
      (value "R0603")
      (footprint "R0603_M1608")
      (description "Resistor")
      (fields (field (name "ALTIUM_VALUE") "750K"))
      (libsource (lib "1.电阻、电容、电感原理库") (part "R0603_M1608"))
    )
    (comp (ref "R45")
      (value "R0603")
      (footprint "R0603_M1608")
      (description "Resistor")
      (fields (field (name "ALTIUM_VALUE") "750K"))
      (libsource (lib "1.电阻、电容、电感原理库") (part "R0603_M1608"))
    )
    (comp (ref "R46")
      (value "R0603")
      (footprint "R0603_M1608")
      (description "Resistor")
      (fields (field (name "ALTIUM_VALUE") "33K"))
      (libsource (lib "1.电阻、电容、电感原理库") (part "R0603_M1608"))
    )
    (comp (ref "R47")
      (value "R0603")
      (footprint "R0603_M1608")
      (description "Resistor")
      (fields (field (name "ALTIUM_VALUE") "33K"))
      (libsource (lib "1.电阻、电容、电感原理库") (part "R0603_M1608"))
    )
    (comp (ref "R48")
      (value "R0603")
      (footprint "R0603_M1608")
      (description "Resistor")
      (fields (field (name "ALTIUM_VALUE") "10K"))
      (libsource (lib "1.电阻、电容、电感原理库") (part "R0603_M1608"))
    )
    (comp (ref "R49")
      (value "R0603")
      (footprint "R0603_M1608")
      (description "Resistor")
      (fields (field (name "ALTIUM_VALUE") "10K"))
      (libsource (lib "1.电阻、电容、电感原理库") (part "R0603_M1608"))
    )
    (comp (ref "R50")
      (value "R0603")
      (footprint "R0603_M1608")
      (description "Resistor")
      (fields (field (name "ALTIUM_VALUE") "100R"))
      (libsource (lib "1.电阻、电容、电感原理库") (part "R0603_M1608"))
    )
    (comp (ref "R51")
      (value "R0603")
      (footprint "R0603_M1608")
      (description "Resistor")
      (fields (field (name "ALTIUM_VALUE") "100R"))
      (libsource (lib "1.电阻、电容、电感原理库") (part "R0603_M1608"))
    )
    (comp (ref "R52")
      (value "R0603")
      (footprint "R0603_M1608")
      (description "Resistor")
      (fields (field (name "ALTIUM_VALUE") "47K"))
      (libsource (lib "1.电阻、电容、电感原理库") (part "R0603_M1608"))
    )
    (comp (ref "R53")
      (value "R0603")
      (footprint "R0603_M1608")
      (description "Resistor")
      (fields (field (name "ALTIUM_VALUE") "47K"))
      (libsource (lib "1.电阻、电容、电感原理库") (part "R0603_M1608"))
    )
    (comp (ref "R54")
      (value "R0603")
      (footprint "R0603_M1608")
      (description "Resistor")
      (fields (field (name "ALTIUM_VALUE") "10K"))
      (libsource (lib "1.电阻、电容、电感原理库") (part "R0603_M1608"))
    )
    (comp (ref "R55")
      (value "R0603")
      (footprint "R0603_M1608")
      (description "Resistor")
      (fields (field (name "ALTIUM_VALUE") "10K"))
      (libsource (lib "1.电阻、电容、电感原理库") (part "R0603_M1608"))
    )
    (comp (ref "R56")
      (value "R0603")
      (footprint "R0603_M1608")
      (description "Resistor")
      (fields (field (name "ALTIUM_VALUE") "NC"))
      (libsource (lib "1.电阻、电容、电感原理库") (part "R0603_M1608"))
    )
    (comp (ref "R57")
      (value "R0603")
      (footprint "R0603_M1608")
      (description "Resistor")
      (fields (field (name "ALTIUM_VALUE") "NC"))
      (libsource (lib "1.电阻、电容、电感原理库") (part "R0603_M1608"))
    )
    (comp (ref "R58")
      (value "R0603")
      (footprint "R0603_M1608")
      (description "Resistor")
      (fields (field (name "ALTIUM_VALUE") "0R"))
      (libsource (lib "1.电阻、电容、电感原理库") (part "R0603_M1608"))
    )
    (comp (ref "R59")
      (value "R0603")
      (footprint "R0603_M1608")
      (description "Resistor")
      (fields (field (name "ALTIUM_VALUE") "0R"))
      (libsource (lib "1.电阻、电容、电感原理库") (part "R0603_M1608"))
    )
    (comp (ref "R60")
      (value "NC")
      (footprint "R0603_M1608")
      (description "Resistor")
      (fields (field (name "Comment") "C0603"))
      (libsource (lib "Miscellaneous Devices") (part "Res1"))
    )
    (comp (ref "R61")
      (value "47K")
      (footprint "R0603_M1608")
      (description "Resistor")
      (fields (field (name "Comment") "C0603"))
      (libsource (lib "Miscellaneous Devices") (part "Res1"))
    )
    (comp (ref "R62")
      (value "47K")
      (footprint "R0603_M1608")
      (description "Resistor")
      (fields (field (name "Comment") "C0603"))
      (libsource (lib "Miscellaneous Devices") (part "Res1"))
    )
    (comp (ref "R63")
      (value "47K")
      (footprint "R0603_M1608")
      (description "Resistor")
      (fields (field (name "Comment") "C0603"))
      (libsource (lib "Miscellaneous Devices") (part "Res1"))
    )
    (comp (ref "R64")
      (value "47K")
      (footprint "R0603_M1608")
      (description "Resistor")
      (fields (field (name "Comment") "C0603"))
      (libsource (lib "Miscellaneous Devices") (part "Res1"))
    )
    (comp (ref "R65")
      (value "47K")
      (footprint "R0603_M1608")
      (description "Resistor")
      (fields (field (name "Comment") "C0603"))
      (libsource (lib "Miscellaneous Devices") (part "Res1"))
    )
    (comp (ref "R66")
      (value "47K")
      (footprint "R0603_M1608")
      (description "Resistor")
      (fields (field (name "Comment") "C0603"))
      (libsource (lib "Miscellaneous Devices") (part "Res1"))
    )
    (comp (ref "R67")
      (value "R0603")
      (footprint "R0603_M1608")
      (description "Resistor")
      (fields (field (name "ALTIUM_VALUE") "47K"))
      (libsource (lib "1.电阻、电容、电感原理库") (part "R0603_M1608"))
    )
    (comp (ref "R68")
      (value "C0603")
      (footprint "R0603_M1608")
      (description "Resistor")
      (fields (field (name "ALTIUM_VALUE") "33K"))
      (libsource (lib "Miscellaneous Devices") (part "Res1"))
    )
    (comp (ref "R69")
      (value "R0603")
      (footprint "R0603_M1608")
      (description "Resistor")
      (fields (field (name "ALTIUM_VALUE") "24K"))
      (libsource (lib "1.电阻、电容、电感原理库") (part "R0603_M1608"))
    )
    (comp (ref "R70")
      (value "R0603")
      (footprint "R0603_M1608")
      (description "Resistor")
      (fields (field (name "ALTIUM_VALUE") "100R") (field (name "PUBLISHER") "Altium Limited"))
      (libsource (lib "Miscellaneous Devices") (part "Res1"))
    )
    (comp (ref "R71")
      (value "C0603")
      (footprint "R0603_M1608")
      (description "Resistor")
      (fields (field (name "ALTIUM_VALUE") "1K"))
      (libsource (lib "Miscellaneous Devices") (part "Res1"))
    )
    (comp (ref "R72")
      (value "47K")
      (footprint "R0603_M1608")
      (description "Resistor")
      (fields (field (name "Comment") "C0603"))
      (libsource (lib "Miscellaneous Devices") (part "Res1"))
    )
    (comp (ref "R73")
      (value "47K")
      (footprint "R0603_M1608")
      (description "Resistor")
      (fields (field (name "Comment") "C0603"))
      (libsource (lib "Miscellaneous Devices") (part "Res1"))
    )
    (comp (ref "R74")
      (value "47K")
      (footprint "R0603_M1608")
      (description "Resistor")
      (fields (field (name "Comment") "C0603"))
      (libsource (lib "Miscellaneous Devices") (part "Res1"))
    )
    (comp (ref "R75")
      (value "47K")
      (footprint "R0603_M1608")
      (description "Resistor")
      (fields (field (name "Comment") "C0603"))
      (libsource (lib "Miscellaneous Devices") (part "Res1"))
    )
    (comp (ref "R76")
      (value "47K")
      (footprint "R0603_M1608")
      (description "Resistor")
      (fields (field (name "Comment") "C0603"))
      (libsource (lib "Miscellaneous Devices") (part "Res1"))
    )
    (comp (ref "R77")
      (value "47K")
      (footprint "R0603_M1608")
      (description "Resistor")
      (fields (field (name "Comment") "C0603"))
      (libsource (lib "Miscellaneous Devices") (part "Res1"))
    )
    (comp (ref "R78")
      (value "47K")
      (footprint "R0603_M1608")
      (description "Resistor")
      (fields (field (name "Comment") "C0603"))
      (libsource (lib "Miscellaneous Devices") (part "Res1"))
    )
    (comp (ref "R79")
      (value "10K")
      (footprint "R0603_M1608")
      (description "Resistor")
      (fields (field (name "Comment") "R0603") (field (name "PUBLISHER") "Altium Limited"))
      (libsource (lib "Miscellaneous Devices") (part "Res1"))
    )
    (comp (ref "R80")
      (value "10K")
      (footprint "R0603_M1608")
      (description "Resistor")
      (fields (field (name "Comment") "R0603") (field (name "PUBLISHER") "Altium Limited"))
      (libsource (lib "Miscellaneous Devices") (part "Res1"))
    )
    (comp (ref "R81")
      (value "10K")
      (footprint "R0603_M1608")
      (description "Resistor")
      (fields (field (name "Comment") "R0603") (field (name "PUBLISHER") "Altium Limited"))
      (libsource (lib "Miscellaneous Devices") (part "Res1"))
    )
    (comp (ref "R82")
      (value "R0603")
      (footprint "R0603_M1608")
      (description "Resistor")
      (fields (field (name "ALTIUM_VALUE") "10K"))
      (libsource (lib "1.电阻、电容、电感原理库") (part "R0603_M1608"))
    )
    (comp (ref "R83")
      (value "R0603")
      (footprint "R0603_M1608")
      (description "Resistor")
      (fields (field (name "ALTIUM_VALUE") "10K"))
      (libsource (lib "1.电阻、电容、电感原理库") (part "R0603_M1608"))
    )
    (comp (ref "R84")
      (value "R0603")
      (footprint "R0603_M1608")
      (description "Resistor")
      (fields (field (name "ALTIUM_VALUE") "10K"))
      (libsource (lib "1.电阻、电容、电感原理库") (part "R0603_M1608"))
    )
    (comp (ref "R85")
      (value "R0603")
      (footprint "R0603_M1608")
      (description "Resistor")
      (fields (field (name "ALTIUM_VALUE") "10K"))
      (libsource (lib "1.电阻、电容、电感原理库") (part "R0603_M1608"))
    )
    (comp (ref "R86")
      (value "R0603")
      (footprint "R0603_M1608")
      (description "Resistor")
      (fields (field (name "ALTIUM_VALUE") "330K"))
      (libsource (lib "1.电阻、电容、电感原理库") (part "R0603_M1608"))
    )
    (comp (ref "R87")
      (value "R0603")
      (footprint "R0603_M1608")
      (description "Resistor")
      (fields (field (name "ALTIUM_VALUE") "330K"))
      (libsource (lib "1.电阻、电容、电感原理库") (part "R0603_M1608"))
    )
    (comp (ref "R88")
      (value "R0603")
      (footprint "R0603_M1608")
      (description "Resistor")
      (fields (field (name "ALTIUM_VALUE") "5.1K") (field (name "PUBLISHER") "Altium Limited"))
      (libsource (lib "Miscellaneous Devices") (part "Res1"))
    )
    (comp (ref "R89")
      (value "R0603")
      (footprint "R0603_M1608")
      (description "Resistor")
      (fields (field (name "ALTIUM_VALUE") "5.1K") (field (name "PUBLISHER") "Altium Limited"))
      (libsource (lib "Miscellaneous Devices") (part "Res1"))
    )
    (comp (ref "R90")
      (value "R0603")
      (footprint "R0603_M1608")
      (description "Resistor")
      (fields (field (name "ALTIUM_VALUE") "10K"))
      (libsource (lib "1.电阻、电容、电感原理库") (part "R0603_M1608"))
    )
    (comp (ref "R91")
      (value "R0603")
      (footprint "R0603_M1608")
      (description "Resistor")
      (fields (field (name "ALTIUM_VALUE") "10K"))
      (libsource (lib "1.电阻、电容、电感原理库") (part "R0603_M1608"))
    )
    (comp (ref "R92")
      (value "R0603")
      (footprint "R0603_M1608")
      (description "Resistor")
      (fields (field (name "ALTIUM_VALUE") "330K"))
      (libsource (lib "1.电阻、电容、电感原理库") (part "R0603_M1608"))
    )
    (comp (ref "R93")
      (value "R0603")
      (footprint "R0603_M1608")
      (description "Resistor")
      (fields (field (name "ALTIUM_VALUE") "330K"))
      (libsource (lib "1.电阻、电容、电感原理库") (part "R0603_M1608"))
    )
    (comp (ref "R94")
      (value "R0603")
      (footprint "R0603_M1608")
      (description "Resistor")
      (fields (field (name "ALTIUM_VALUE") "5.1K") (field (name "PUBLISHER") "Altium Limited"))
      (libsource (lib "Miscellaneous Devices") (part "Res1"))
    )
    (comp (ref "R95")
      (value "R0603")
      (footprint "R0603_M1608")
      (description "Resistor")
      (fields (field (name "ALTIUM_VALUE") "100R"))
      (libsource (lib "1.电阻、电容、电感原理库") (part "R0603_M1608"))
    )
    (comp (ref "R96")
      (value "R0603")
      (footprint "R0603_M1608")
      (description "Resistor")
      (fields (field (name "ALTIUM_VALUE") "100R"))
      (libsource (lib "1.电阻、电容、电感原理库") (part "R0603_M1608"))
    )
    (comp (ref "R97")
      (value "R0603")
      (footprint "R0603_M1608")
      (description "Resistor")
      (fields (field (name "ALTIUM_VALUE") "5.1K") (field (name "PUBLISHER") "Altium Limited"))
      (libsource (lib "Miscellaneous Devices") (part "Res1"))
    )
    (comp (ref "R98")
      (value "R0603")
      (footprint "R0603_M1608")
      (description "Resistor")
      (fields (field (name "ALTIUM_VALUE") "20K"))
      (libsource (lib "1.电阻、电容、电感原理库") (part "R0603_M1608"))
    )
    (comp (ref "R99")
      (value "R0603")
      (footprint "R0603_M1608")
      (description "Resistor")
      (fields (field (name "ALTIUM_VALUE") "20K"))
      (libsource (lib "1.电阻、电容、电感原理库") (part "R0603_M1608"))
    )
    (comp (ref "R100")
      (value "R0603")
      (footprint "R0603_M1608")
      (description "Resistor")
      (fields (field (name "ALTIUM_VALUE") "10K") (field (name "PUBLISHER") "Altium Limited"))
      (libsource (lib "Miscellaneous Devices") (part "Res1"))
    )
    (comp (ref "R101")
      (value "R0603")
      (footprint "R0603_M1608")
      (description "Resistor")
      (fields (field (name "ALTIUM_VALUE") "10K") (field (name "PUBLISHER") "Altium Limited"))
      (libsource (lib "Miscellaneous Devices") (part "Res1"))
    )
    (comp (ref "R102")
      (value "R0603")
      (footprint "R0603_M1608")
      (description "Resistor")
      (fields (field (name "ALTIUM_VALUE") "1K") (field (name "PUBLISHER") "Altium Limited"))
      (libsource (lib "Miscellaneous Devices") (part "Res1"))
    )
    (comp (ref "R103")
      (value "R0603")
      (footprint "R0603_M1608")
      (description "Resistor")
      (fields (field (name "ALTIUM_VALUE") "1K"))
      (libsource (lib "1.电阻、电容、电感原理库") (part "R0603_M1608"))
    )
    (comp (ref "R104")
      (value "R0603")
      (footprint "R0603_M1608")
      (description "Resistor")
      (fields (field (name "ALTIUM_VALUE") "1K") (field (name "PUBLISHER") "Altium Limited"))
      (libsource (lib "Miscellaneous Devices") (part "Res1"))
    )
    (comp (ref "R105")
      (value "R0603")
      (footprint "R0603_M1608")
      (description "Resistor")
      (fields (field (name "ALTIUM_VALUE") "1K"))
      (libsource (lib "1.电阻、电容、电感原理库") (part "R0603_M1608"))
    )
    (comp (ref "R106")
      (value "R0603")
      (footprint "R0603_M1608")
      (description "Resistor")
      (fields (field (name "ALTIUM_VALUE") "10K") (field (name "PUBLISHER") "Altium Limited"))
      (libsource (lib "Miscellaneous Devices") (part "Res1"))
    )
    (comp (ref "R107")
      (value "R0603")
      (footprint "R0603_M1608")
      (description "Resistor")
      (fields (field (name "ALTIUM_VALUE") "10R") (field (name "PUBLISHER") "Altium Limited"))
      (libsource (lib "Miscellaneous Devices") (part "Res1"))
    )
    (comp (ref "R108")
      (value "R0603")
      (footprint "R0603_M1608")
      (description "Resistor")
      (fields (field (name "ALTIUM_VALUE") "10R") (field (name "PUBLISHER") "Altium Limited"))
      (libsource (lib "Miscellaneous Devices") (part "Res1"))
    )
    (comp (ref "R109")
      (value "R0603")
      (footprint "R0603_M1608")
      (description "Resistor")
      (fields (field (name "ALTIUM_VALUE") "10K") (field (name "PUBLISHER") "Altium Limited"))
      (libsource (lib "Miscellaneous Devices") (part "Res1"))
    )
    (comp (ref "R110")
      (value "C0603")
      (footprint "R0603_M1608")
      (description "Resistor")
      (fields (field (name "ALTIUM_VALUE") "33K"))
      (libsource (lib "Miscellaneous Devices") (part "Res1"))
    )
    (comp (ref "R111")
      (value "R0603")
      (footprint "R0603_M1608")
      (description "Resistor")
      (fields (field (name "ALTIUM_VALUE") "5.1K"))
      (libsource (lib "1.电阻、电容、电感原理库") (part "R0603_M1608"))
    )
    (comp (ref "R112")
      (value "R0603")
      (footprint "R0603_M1608")
      (description "Resistor")
      (fields (field (name "ALTIUM_VALUE") "5.1K"))
      (libsource (lib "1.电阻、电容、电感原理库") (part "R0603_M1608"))
    )
    (comp (ref "R113")
      (value "C0603")
      (footprint "R0603_M1608")
      (description "Resistor")
      (fields (field (name "ALTIUM_VALUE") "100K"))
      (libsource (lib "Miscellaneous Devices") (part "Res1"))
    )
    (comp (ref "R114")
      (value "C0603")
      (footprint "R0603_M1608")
      (description "Resistor")
      (fields (field (name "ALTIUM_VALUE") "68K"))
      (libsource (lib "Miscellaneous Devices") (part "Res1"))
    )
    (comp (ref "R115")
      (value "R0603")
      (footprint "R0603_M1608")
      (description "Resistor")
      (fields (field (name "ALTIUM_VALUE") "5.1K") (field (name "PUBLISHER") "Altium Limited"))
      (libsource (lib "Miscellaneous Devices") (part "Res1"))
    )
    (comp (ref "R116")
      (value "R0603")
      (footprint "R0603_M1608")
      (description "Resistor")
      (fields (field (name "ALTIUM_VALUE") "5.1K") (field (name "PUBLISHER") "Altium Limited"))
      (libsource (lib "Miscellaneous Devices") (part "Res1"))
    )
    (comp (ref "R117")
      (value "R0603")
      (footprint "R0603_M1608")
      (description "Resistor")
      (fields (field (name "ALTIUM_VALUE") "5.1K") (field (name "PUBLISHER") "Altium Limited"))
      (libsource (lib "Miscellaneous Devices") (part "Res1"))
    )
    (comp (ref "R118")
      (value "R0603")
      (footprint "R0603_M1608")
      (description "Resistor")
      (fields (field (name "ALTIUM_VALUE") "5.1K"))
      (libsource (lib "1.电阻、电容、电感原理库") (part "R0603_M1608"))
    )
    (comp (ref "R119")
      (value "C0603")
      (footprint "R0603_M1608")
      (description "Resistor")
      (fields (field (name "ALTIUM_VALUE") "2.7K"))
      (libsource (lib "Miscellaneous Devices") (part "Res1"))
    )
    (comp (ref "R120")
      (value "R0603")
      (footprint "R0603_M1608")
      (description "Resistor")
      (fields (field (name "ALTIUM_VALUE") "5.1K") (field (name "PUBLISHER") "Altium Limited"))
      (libsource (lib "Miscellaneous Devices") (part "Res1"))
    )
    (comp (ref "R121")
      (value "R0603")
      (footprint "R0603_M1608")
      (description "Resistor")
      (fields (field (name "ALTIUM_VALUE") "10K"))
      (libsource (lib "1.电阻、电容、电感原理库") (part "R0603_M1608"))
    )
    (comp (ref "R122")
      (value "R0603")
      (footprint "R0603_M1608")
      (description "Resistor")
      (fields (field (name "ALTIUM_VALUE") "10K"))
      (libsource (lib "1.电阻、电容、电感原理库") (part "R0603_M1608"))
    )
    (comp (ref "R123")
      (value "C0603")
      (footprint "R0603_M1608")
      (description "Resistor")
      (fields (field (name "ALTIUM_VALUE") "100K"))
      (libsource (lib "Miscellaneous Devices") (part "Res1"))
    )
    (comp (ref "R124")
      (value "R0603")
      (footprint "R0603_M1608")
      (description "Resistor")
      (fields (field (name "ALTIUM_VALUE") "5.1K") (field (name "PUBLISHER") "Altium Limited"))
      (libsource (lib "Miscellaneous Devices") (part "Res1"))
    )
    (comp (ref "R125")
      (value "R0603")
      (footprint "R0603_M1608")
      (description "Resistor")
      (fields (field (name "ALTIUM_VALUE") "1K") (field (name "PUBLISHER") "Altium Limited"))
      (libsource (lib "Miscellaneous Devices") (part "Res1"))
    )
    (comp (ref "R126")
      (value "R0603")
      (footprint "R0603_M1608")
      (description "Resistor")
      (fields (field (name "ALTIUM_VALUE") "1K") (field (name "PUBLISHER") "Altium Limited"))
      (libsource (lib "Miscellaneous Devices") (part "Res1"))
    )
    (comp (ref "R127")
      (value "R0603")
      (footprint "R0603_M1608")
      (description "Resistor")
      (fields (field (name "ALTIUM_VALUE") "100K") (field (name "PUBLISHER") "Altium Limited"))
      (libsource (lib "Miscellaneous Devices") (part "Res1"))
    )
    (comp (ref "R128")
      (value "R0603")
      (footprint "R0603_M1608")
      (description "Resistor")
      (fields (field (name "ALTIUM_VALUE") "10K") (field (name "PUBLISHER") "Altium Limited"))
      (libsource (lib "Miscellaneous Devices") (part "Res1"))
    )
    (comp (ref "R129")
      (value "R0603")
      (footprint "R0603_M1608")
      (description "Resistor")
      (fields (field (name "ALTIUM_VALUE") "10K") (field (name "PUBLISHER") "Altium Limited"))
      (libsource (lib "Miscellaneous Devices") (part "Res1"))
    )
    (comp (ref "R130")
      (value "R0603")
      (footprint "R0603_M1608")
      (description "Resistor")
      (fields (field (name "ALTIUM_VALUE") "10K") (field (name "PUBLISHER") "Altium Limited"))
      (libsource (lib "Miscellaneous Devices") (part "Res1"))
    )
    (comp (ref "R131")
      (value "R0603")
      (footprint "R0603_M1608")
      (description "Resistor")
      (fields (field (name "ALTIUM_VALUE") "1K") (field (name "PUBLISHER") "Altium Limited"))
      (libsource (lib "Miscellaneous Devices") (part "Res1"))
    )
    (comp (ref "R132")
      (value "R0603")
      (footprint "R0603_M1608")
      (description "Resistor")
      (fields (field (name "ALTIUM_VALUE") "10R"))
      (libsource (lib "1.电阻、电容、电感原理库") (part "R0603_M1608"))
    )
    (comp (ref "R133")
      (value "R0603")
      (footprint "R0603_M1608")
      (description "Resistor")
      (fields (field (name "ALTIUM_VALUE") "10R"))
      (libsource (lib "1.电阻、电容、电感原理库") (part "R0603_M1608"))
    )
    (comp (ref "R134")
      (value "R0603")
      (footprint "R0603_M1608")
      (description "Resistor")
      (fields (field (name "ALTIUM_VALUE") "10K") (field (name "PUBLISHER") "Altium Limited"))
      (libsource (lib "Miscellaneous Devices") (part "Res1"))
    )
    (comp (ref "R135")
      (value "R2512")
      (footprint "R2512_M6332")
      (description "Resistor")
      (fields (field (name "ALTIUM_VALUE") "0.2R"))
      (libsource (lib "1.电阻、电容、电感原理库") (part "R2512_M6332"))
    )
    (comp (ref "R136")
      (value "R0603")
      (footprint "R0603_M1608")
      (description "Resistor")
      (fields (field (name "ALTIUM_VALUE") "10K") (field (name "PUBLISHER") "Altium Limited"))
      (libsource (lib "Miscellaneous Devices") (part "Res1"))
    )
    (comp (ref "R137")
      (value "R0603")
      (footprint "R0603_M1608")
      (description "Resistor")
      (fields (field (name "ALTIUM_VALUE") "1K") (field (name "PUBLISHER") "Altium Limited"))
      (libsource (lib "Miscellaneous Devices") (part "Res1"))
    )
    (comp (ref "R138")
      (value "R0603")
      (footprint "R0603_M1608")
      (description "Resistor")
      (fields (field (name "ALTIUM_VALUE") "100R") (field (name "PUBLISHER") "Altium Limited"))
      (libsource (lib "Miscellaneous Devices") (part "Res1"))
    )
    (comp (ref "R139")
      (value "R0603")
      (footprint "R0603_M1608")
      (description "Resistor")
      (fields (field (name "ALTIUM_VALUE") "100K") (field (name "PUBLISHER") "Altium Limited"))
      (libsource (lib "Miscellaneous Devices") (part "Res1"))
    )
    (comp (ref "R140")
      (value "R0603")
      (footprint "R0603_M1608")
      (description "Resistor")
      (fields (field (name "ALTIUM_VALUE") "10K") (field (name "PUBLISHER") "Altium Limited"))
      (libsource (lib "Miscellaneous Devices") (part "Res1"))
    )
    (comp (ref "R141")
      (value "R0603")
      (footprint "R0603_M1608")
      (description "Resistor")
      (fields (field (name "ALTIUM_VALUE") "10R") (field (name "PUBLISHER") "Altium Limited"))
      (libsource (lib "Miscellaneous Devices") (part "Res1"))
    )
    (comp (ref "R142")
      (value "R0603")
      (footprint "R0603_M1608")
      (description "Resistor")
      (fields (field (name "ALTIUM_VALUE") "10K") (field (name "PUBLISHER") "Altium Limited"))
      (libsource (lib "Miscellaneous Devices") (part "Res1"))
    )
    (comp (ref "R143")
      (value "R0603")
      (footprint "R0603_M1608")
      (description "Resistor")
      (fields (field (name "ALTIUM_VALUE") "10R") (field (name "PUBLISHER") "Altium Limited"))
      (libsource (lib "Miscellaneous Devices") (part "Res1"))
    )
    (comp (ref "R144")
      (value "C0603")
      (footprint "R0603_M1608")
      (description "Resistor")
      (fields (field (name "ALTIUM_VALUE") "1K"))
      (libsource (lib "Miscellaneous Devices") (part "Res1"))
    )
    (comp (ref "R145")
      (value "R2512")
      (footprint "R2512_M6332")
      (description "Resistor")
      (fields (field (name "ALTIUM_VALUE") "0.2R"))
      (libsource (lib "1.电阻、电容、电感原理库") (part "R2512_M6332"))
    )
    (comp (ref "R146")
      (value "R0603")
      (footprint "R0603_M1608")
      (description "Resistor")
      (fields (field (name "ALTIUM_VALUE") "1K") (field (name "PUBLISHER") "Altium Limited"))
      (libsource (lib "Miscellaneous Devices") (part "Res1"))
    )
    (comp (ref "R147")
      (value "NC")
      (footprint "R0603_M1608")
      (description "Resistor")
      (fields (field (name "Comment") "C0603"))
      (libsource (lib "Miscellaneous Devices") (part "Res1"))
    )
    (comp (ref "R148")
      (value "47K")
      (footprint "R0603_M1608")
      (description "Resistor")
      (fields (field (name "Comment") "C0603"))
      (libsource (lib "Miscellaneous Devices") (part "Res1"))
    )
    (comp (ref "R149")
      (value "NC")
      (footprint "R0603_M1608")
      (description "Resistor")
      (fields (field (name "Comment") "C0603"))
      (libsource (lib "Miscellaneous Devices") (part "Res1"))
    )
    (comp (ref "R150")
      (value "NC")
      (footprint "R0603_M1608")
      (description "Resistor")
      (fields (field (name "Comment") "C0603"))
      (libsource (lib "Miscellaneous Devices") (part "Res1"))
    )
    (comp (ref "R151")
      (value "C0603")
      (footprint "R0603_M1608")
      (description "Resistor")
      (fields (field (name "ALTIUM_VALUE") "10K"))
      (libsource (lib "Miscellaneous Devices") (part "Res1"))
    )
    (comp (ref "R152")
      (value "C0603")
      (footprint "R0603_M1608")
      (description "Resistor")
      (fields (field (name "ALTIUM_VALUE") "1K"))
      (libsource (lib "Miscellaneous Devices") (part "Res1"))
    )
    (comp (ref "U1")
      (value "STM32F103VCT6")
      (footprint "LQFP100_N")
      (fields (field (name "ALTIUM_VALUE") "*"))
      (libsource (lib "5.芯片原理库") (part "STM32F103V8T6"))
    )
    (comp (ref "U2")
      (value "PG-DSO28-17")
      (footprint "PG-DSO28-17")
      (fields (field (name "ALTIUM_VALUE") "IR2136"))
      (libsource (lib "PCB_Project1") (part "6EDL04N02"))
    )
    (comp (ref "U3")
      (value "PG-DSO28-17")
      (footprint "PG-DSO28-17")
      (fields (field (name "ALTIUM_VALUE") "IR2136"))
      (libsource (lib "PCB_Project1") (part "6EDL04N02"))
    )
    (comp (ref "U4")
      (value "SOIC-8")
      (footprint "SOIC-8")
      (description "Dual Differential Comparators")
      (fields (field (name "ALTIUM_VALUE") "LM393ADR"))
      (libsource (lib "5.芯片原理库") (part "LM393ADR"))
    )
    (comp (ref "U5")
      (value "SO-14")
      (footprint "SOP-14")
      (description "Quadruple 2-Input Positive-AND Gate")
      (fields (field (name "ALTIUM_VALUE") "NXP 74HCT08") (field (name "PUBLISHER") "Altium Limited"))
      (libsource (lib "TI Logic Gate 1") (part "SN74AHCT08N"))
    )
    (comp (ref "U6")
      (value "SO-14")
      (footprint "SOP-14")
      (description "Hex Schmitt-Trigger Inverter")
      (fields (field (name "ALTIUM_VALUE") "NXP 74HCT14") (field (name "PUBLISHER") "Altium Limited"))
      (libsource (lib "TI Logic Gate 1") (part "SN74ACT14N"))
    )
    (comp (ref "U7")
      (value "SN74HC245NSR")
      (footprint "SOP-20")
      (description "Octal Bus Transceivers With 3-State Outputs")
      (fields (field (name "Comment") "SOIC-20"))
      (libsource (lib "5.芯片原理库") (part "SN74HC245NSR"))
    )
    (comp (ref "U8")
      (value "SO-14")
      (footprint "SOP-14")
      (description "Quadruple 2-Input Positive-AND Gate")
      (fields (field (name "ALTIUM_VALUE") "NXP 74HCT08") (field (name "PUBLISHER") "Altium Limited"))
      (libsource (lib "TI Logic Gate 1") (part "SN74AHCT08N"))
    )
    (comp (ref "U9")
      (value "SOIC-8")
      (footprint "SOIC-8")
      (fields (field (name "ALTIUM_VALUE") "LM393"))
      (libsource (lib "CYSchlib") (part "OP"))
    )
    (comp (ref "U10")
      (value "SOIC-8")
      (footprint "SOIC-8")
      (fields (field (name "ALTIUM_VALUE") "LM393"))
      (libsource (lib "CYSchlib") (part "OP"))
    )
    (comp (ref "U11")
      (value "SOP-20")
      (footprint "SOP-20")
      (fields (field (name "ALTIUM_VALUE") "SN74HC245NSR"))
      (libsource (lib "SCH") (part "74HC245"))
    )
    (comp (ref "U12")
      (value "SOIC-8")
      (footprint "SOIC-8")
      (description "Dual Differential Comparators")
      (fields (field (name "ALTIUM_VALUE") "LM393ADR"))
      (libsource (lib "5.芯片原理库") (part "LM393ADR"))
    )
    (comp (ref "U13")
      (value "SOP-20")
      (footprint "SOP-20")
      (fields (field (name "ALTIUM_VALUE") "SN74HC245NSR"))
      (libsource (lib "SCH") (part "74HC245"))
    )
    (comp (ref "U14")
      (value "SOT26")
      (footprint "SOT26")
      (fields (field (name "ALTIUM_VALUE") "FP6291"))
      (libsource (lib "SCH") (part "FP6291"))
    )
    (comp (ref "U15")
      (value "SOT-23-5")
      (footprint "SOT-23-5")
      (description "Capacitor-Less 500mA Low Power Consumption High Speed LDO Regulator")
      (fields (field (name "ALTIUM_VALUE") "XC6503D331MR-G"))
      (libsource (lib "4.电源芯片原理库") (part "XC6503D331MR-G"))
    )
    (comp (ref "X1") (value "8M 49SMD") (footprint "HC-49SMD") (libsource (lib "CYSchlib") (part "XTAL")))
  )
  (nets
    (net (code "1") (name "+15V") (class "Default")
      (node (ref "C1") (pin "1") (pinfunction "1_1") (pintype "passive"))
      (node (ref "C2") (pin "1") (pinfunction "1_1") (pintype "passive"))
      (node (ref "C3") (pin "1") (pinfunction "1_1") (pintype "passive"))
      (node (ref "C4") (pin "1") (pinfunction "1_1") (pintype "passive"))
      (node (ref "C83") (pin "1") (pinfunction "1_1") (pintype "passive"))
      (node (ref "C84") (pin "1") (pinfunction "1_1") (pintype "passive"))
      (node (ref "D1") (pin "1") (pinfunction "A_1") (pintype "passive"))
      (node (ref "D12") (pin "2") (pinfunction "K_2") (pintype "passive"))
      (node (ref "D2") (pin "1") (pinfunction "A_1") (pintype "passive"))
      (node (ref "D3") (pin "1") (pinfunction "A_1") (pintype "passive"))
      (node (ref "D4") (pin "1") (pinfunction "A_1") (pintype "passive"))
      (node (ref "D5") (pin "1") (pinfunction "A_1") (pintype "passive"))
      (node (ref "D6") (pin "1") (pinfunction "A_1") (pintype "passive"))
      (node (ref "R114") (pin "1") (pinfunction "1_1") (pintype "passive"))
      (node (ref "R26") (pin "1") (pinfunction "1_1") (pintype "passive"))
      (node (ref "R27") (pin "1") (pinfunction "1_1") (pintype "passive"))
      (node (ref "U2") (pin "1") (pinfunction "VCC_1") (pintype "passive"))
      (node (ref "U3") (pin "1") (pinfunction "VCC_1") (pintype "passive"))
    )
    (net (code "2") (name "/ADC-H-IN") (class "Default")
      (node (ref "C85") (pin "1") (pinfunction "1_1") (pintype "passive"))
      (node (ref "R127") (pin "1") (pinfunction "1_1") (pintype "passive"))
      (node (ref "U4") (pin "3") (pinfunction "IN1+_3") (pintype "passive"))
    )
    (net (code "3") (name "/ADC-I-HEAD") (class "Default")
      (node (ref "C36") (pin "1") (pinfunction "1_1") (pintype "passive"))
      (node (ref "R51") (pin "1") (pinfunction "1_1") (pintype "passive"))
      (node (ref "U1") (pin "16") (pinfunction "PC1_16") (pintype "passive"))
    )
    (net (code "4") (name "/ADC-I-WING") (class "Default")
      (node (ref "C31") (pin "1") (pinfunction "1_1") (pintype "passive"))
      (node (ref "R50") (pin "2") (pinfunction "2_2") (pintype "passive"))
      (node (ref "U1") (pin "17") (pinfunction "PC2_17") (pintype "passive"))
    )
    (net (code "5") (name "/ADC-L-I") (class "Default")
      (node (ref "C12") (pin "1") (pinfunction "1_1") (pintype "passive"))
      (node (ref "R24") (pin "1") (pinfunction "1_1") (pintype "passive"))
      (node (ref "U12") (pin "3") (pinfunction "IN1+_3") (pintype "passive"))
    )
    (net (code "6") (name "/ADC-L-WHEEL") (class "Default")
      (node (ref "C78") (pin "1") (pinfunction "1_1") (pintype "passive"))
      (node (ref "R95") (pin "1") (pinfunction "1_1") (pintype "passive"))
      (node (ref "U1") (pin "30") (pinfunction "PA5_30") (pintype "passive"))
    )
    (net (code "7") (name "/ADC-R-I") (class "Default")
      (node (ref "C13") (pin "1") (pinfunction "1_1") (pintype "passive"))
      (node (ref "R25") (pin "1") (pinfunction "1_1") (pintype "passive"))
      (node (ref "U12") (pin "5") (pinfunction "IN2+_5") (pintype "passive"))
    )
    (net (code "8") (name "/ADC-R-WHEEL") (class "Default")
      (node (ref "C77") (pin "1") (pinfunction "1_1") (pintype "passive"))
      (node (ref "R96") (pin "2") (pinfunction "2_2") (pintype "passive"))
      (node (ref "U1") (pin "31") (pinfunction "PA6_31") (pintype "passive"))
    )
    (net (code "9") (name "/ADC-U-HW") (class "Default")
      (node (ref "R138") (pin "1") (pinfunction "1_1") (pintype "passive"))
      (node (ref "U1") (pin "15") (pinfunction "PC0_15") (pintype "passive"))
    )
    (net (code "10") (name "/ADC-U-WHEEL") (class "Default")
      (node (ref "R70") (pin "1") (pinfunction "1_1") (pintype "passive"))
      (node (ref "U1") (pin "29") (pinfunction "PA4_29") (pintype "passive"))
    )
    (net (code "11") (name "/ADC-W-IN") (class "Default")
      (node (ref "C87") (pin "1") (pinfunction "1_1") (pintype "passive"))
      (node (ref "R139") (pin "1") (pinfunction "1_1") (pintype "passive"))
      (node (ref "U4") (pin "5") (pinfunction "IN2+_5") (pintype "passive"))
    )
    (net (code "12") (name "/DIR-IO-1") (class "Default")
      (node (ref "R137") (pin "2") (pinfunction "2_2") (pintype "passive"))
      (node (ref "U1") (pin "58") (pinfunction "PD11_58") (pintype "passive"))
      (node (ref "U5") (pin "4") (pinfunction "A_4") (pintype "input"))
      (node (ref "U6") (pin "1") (pinfunction "A_1") (pintype "input"))
    )
    (net (code "13") (name "/DIR-IO-2") (class "Default")
      (node (ref "R104") (pin "2") (pinfunction "2_2") (pintype "passive"))
      (node (ref "U1") (pin "57") (pinfunction "PD10_57") (pintype "passive"))
      (node (ref "U5") (pin "12") (pinfunction "A_12") (pintype "input"))
      (node (ref "U6") (pin "3") (pinfunction "A_3") (pintype "input"))
    )
    (net (code "14") (name "/DIR-IO-3") (class "Default")
      (node (ref "R126") (pin "2") (pinfunction "2_2") (pintype "passive"))
      (node (ref "U1") (pin "56") (pinfunction "PD9_56") (pintype "passive"))
      (node (ref "U6") (pin "5") (pinfunction "A_5") (pintype "input"))
      (node (ref "U8") (pin "4") (pinfunction "A_4") (pintype "input"))
    )
    (net (code "15") (name "/DIR1N") (class "Default")
      (node (ref "R131") (pin "1") (pinfunction "1_1") (pintype "passive"))
      (node (ref "U5") (pin "2") (pinfunction "B_2") (pintype "input"))
      (node (ref "U6") (pin "2") (pinfunction "Y_2") (pintype "output"))
    )
    (net (code "16") (name "/DIR2N") (class "Default")
      (node (ref "R102") (pin "1") (pinfunction "1_1") (pintype "passive"))
      (node (ref "U5") (pin "10") (pinfunction "B_10") (pintype "input"))
      (node (ref "U6") (pin "4") (pinfunction "Y_4") (pintype "output"))
    )
    (net (code "17") (name "/DIR3N") (class "Default")
      (node (ref "R125") (pin "1") (pinfunction "1_1") (pintype "passive"))
      (node (ref "U6") (pin "6") (pinfunction "Y_6") (pintype "output"))
      (node (ref "U8") (pin "2") (pinfunction "B_2") (pintype "input"))
    )
    (net (code "18") (name "/EN-L") (class "Default")
      (node (ref "D9") (pin "2") (pinfunction "K_2") (pintype "passive"))
      (node (ref "U1") (pin "38") (pinfunction "PE7_38") (pintype "passive"))
    )
    (net (code "19") (name "/EN-R") (class "Default")
      (node (ref "D10") (pin "2") (pinfunction "K_2") (pintype "passive"))
      (node (ref "U1") (pin "26") (pinfunction "PA3_26") (pintype "passive"))
    )
    (net (code "20") (name "/ENC-HEAD-A") (class "Default")
      (node (ref "U1") (pin "80") (pinfunction "PC12_80") (pintype "passive"))
      (node (ref "U7") (pin "3") (pinfunction "A1_3") (pintype "passive"))
    )
    (net (code "21") (name "/ENC-HEAD-A1") (class "Default")
      (node (ref "C30") (pin "1") (pinfunction "1_1") (pintype "passive"))
      (node (ref "J4") (pin "2") (pinfunction "2_2") (pintype "passive"))
      (node (ref "R47") (pin "1") (pinfunction "1_1") (pintype "passive"))
      (node (ref "U7") (pin "17") (pinfunction "B1_17") (pintype "passive"))
    )
    (net (code "22") (name "/ENC-HEAD-B") (class "Default")
      (node (ref "U1") (pin "81") (pinfunction "PD0_81") (pintype "passive"))
      (node (ref "U7") (pin "2") (pinfunction "A0_2") (pintype "passive"))
    )
    (net (code "23") (name "/ENC-HEAD-B1") (class "Default")
      (node (ref "C29") (pin "1") (pinfunction "1_1") (pintype "passive"))
      (node (ref "J4") (pin "1") (pinfunction "1_1") (pintype "passive"))
      (node (ref "R46") (pin "1") (pinfunction "1_1") (pintype "passive"))
      (node (ref "U7") (pin "18") (pinfunction "B0_18") (pintype "passive"))
    )
    (net (code "24") (name "/ENC-L-A") (class "Default")
      (node (ref "C48") (pin "1") (pinfunction "1_1") (pintype "passive"))
      (node (ref "J8") (pin "5") (pinfunction "5_5") (pintype "passive"))
      (node (ref "R64") (pin "2") (pinfunction "2_2") (pintype "passive"))
      (node (ref "U11") (pin "15") (pinfunction "B3_15") (pintype "passive"))
    )
    (net (code "25") (name "/ENC-L-A1") (class "Default")
      (node (ref "U1") (pin "90") (pinfunction "PB4/JNTRST_90") (pintype "passive"))
      (node (ref "U11") (pin "5") (pinfunction "A3_5") (pintype "passive"))
    )
    (net (code "26") (name "/ENC-L-B") (class "Default")
      (node (ref "C49") (pin "1") (pinfunction "1_1") (pintype "passive"))
      (node (ref "J8") (pin "4") (pinfunction "4_4") (pintype "passive"))
      (node (ref "R147") (pin "1") (pinfunction "1_1") (pintype "passive"))
      (node (ref "R65") (pin "2") (pinfunction "2_2") (pintype "passive"))
      (node (ref "U11") (pin "14") (pinfunction "B4_14") (pintype "passive"))
    )
    (net (code "27") (name "/ENC-L-B1") (class "Default")
      (node (ref "U1") (pin "91") (pinfunction "PB5_91") (pintype "passive"))
      (node (ref "U11") (pin "6") (pinfunction "A4_6") (pintype "passive"))
    )
    (net (code "28") (name "/ENC-L-Z") (class "Default")
      (node (ref "C50") (pin "1") (pinfunction "1_1") (pintype "passive"))
      (node (ref "J8") (pin "3") (pinfunction "3_3") (pintype "passive"))
      (node (ref "R60") (pin "1") (pinfunction "1_1") (pintype "passive"))
      (node (ref "R66") (pin "2") (pinfunction "2_2") (pintype "passive"))
      (node (ref "U11") (pin "13") (pinfunction "B5_13") (pintype "passive"))
    )
    (net (code "29") (name "/ENC-L-Z1") (class "Default")
      (node (ref "U1") (pin "46") (pinfunction "PE15_46") (pintype "passive"))
      (node (ref "U11") (pin "7") (pinfunction "A5_7") (pintype "passive"))
    )
    (net (code "30") (name "/ENC-R-A") (class "Default")
      (node (ref "C61") (pin "1") (pinfunction "1_1") (pintype "passive"))
      (node (ref "J10") (pin "5") (pinfunction "5_5") (pintype "passive"))
      (node (ref "R75") (pin "2") (pinfunction "2_2") (pintype "passive"))
      (node (ref "U13") (pin "12") (pinfunction "B6_12") (pintype "passive"))
    )
    (net (code "31") (name "/ENC-R-A1") (class "Default")
      (node (ref "U1") (pin "23") (pinfunction "PA0-WKUP_23") (pintype "passive"))
      (node (ref "U13") (pin "8") (pinfunction "A6_8") (pintype "passive"))
    )
    (net (code "32") (name "/ENC-R-B") (class "Default")
      (node (ref "C62") (pin "1") (pinfunction "1_1") (pintype "passive"))
      (node (ref "J10") (pin "4") (pinfunction "4_4") (pintype "passive"))
      (node (ref "R150") (pin "1") (pinfunction "1_1") (pintype "passive"))
      (node (ref "R76") (pin "2") (pinfunction "2_2") (pintype "passive"))
      (node (ref "U13") (pin "13") (pinfunction "B5_13") (pintype "passive"))
    )
    (net (code "33") (name "/ENC-R-B1") (class "Default")
      (node (ref "U1") (pin "24") (pinfunction "PA1_24") (pintype "passive"))
      (node (ref "U13") (pin "7") (pinfunction "A5_7") (pintype "passive"))
    )
    (net (code "34") (name "/ENC-R-Z") (class "Default")
      (node (ref "C63") (pin "1") (pinfunction "1_1") (pintype "passive"))
      (node (ref "J10") (pin "3") (pinfunction "3_3") (pintype "passive"))
      (node (ref "R149") (pin "1") (pinfunction "1_1") (pintype "passive"))
      (node (ref "R77") (pin "2") (pinfunction "2_2") (pintype "passive"))
      (node (ref "U13") (pin "14") (pinfunction "B4_14") (pintype "passive"))
    )
    (net (code "35") (name "/ENC-R-Z1") (class "Default")
      (node (ref "U1") (pin "4") (pinfunction "PE5_4") (pintype "passive"))
      (node (ref "U13") (pin "6") (pinfunction "A4_6") (pintype "passive"))
    )
    (net (code "36") (name "/ENC-W-L") (class "Default")
      (node (ref "C70") (pin "1") (pinfunction "1_1") (pintype "passive"))
      (node (ref "R84") (pin "1") (pinfunction "1_1") (pintype "passive"))
      (node (ref "R87") (pin "2") (pinfunction "2_2") (pintype "passive"))
      (node (ref "U1") (pin "66") (pinfunction "PC9_66") (pintype "passive"))
      (node (ref "U10") (pin "1") (pinfunction "1_1") (pintype "passive"))
    )
    (net (code "37") (name "/ENC-W-L1") (class "Default")
      (node (ref "C24") (pin "1") (pinfunction "1_1") (pintype "passive"))
      (node (ref "J6") (pin "3") (pinfunction "3_3") (pintype "passive"))
      (node (ref "R41") (pin "1") (pinfunction "1_1") (pintype "passive"))
      (node (ref "R87") (pin "1") (pinfunction "1_1") (pintype "passive"))
      (node (ref "U10") (pin "3") (pinfunction "3_3") (pintype "passive"))
    )
    (net (code "38") (name "/ENC-W-R") (class "Default")
      (node (ref "C69") (pin "1") (pinfunction "1_1") (pintype "passive"))
      (node (ref "R82") (pin "1") (pinfunction "1_1") (pintype "passive"))
      (node (ref "R86") (pin "2") (pinfunction "2_2") (pintype "passive"))
      (node (ref "U1") (pin "70") (pinfunction "PA11_70") (pintype "passive"))
      (node (ref "U9") (pin "1") (pinfunction "1_1") (pintype "passive"))
    )
    (net (code "39") (name "/ENC-W-R1") (class "Default")
      (node (ref "C26") (pin "1") (pinfunction "1_1") (pintype "passive"))
      (node (ref "J7") (pin "3") (pinfunction "3_3") (pintype "passive"))
      (node (ref "R43") (pin "1") (pinfunction "1_1") (pintype "passive"))
      (node (ref "R86") (pin "1") (pinfunction "1_1") (pintype "passive"))
      (node (ref "U9") (pin "3") (pinfunction "3_3") (pintype "passive"))
    )
    (net (code "40") (name "/FAULT-L") (class "Default")
      (node (ref "R11") (pin "1") (pinfunction "1_1") (pintype "passive"))
      (node (ref "U1") (pin "33") (pinfunction "PC4_33") (pintype "passive"))
      (node (ref "U2") (pin "8") (pinfunction "FAULT_8") (pintype "passive"))
    )
    (net (code "41") (name "/FAULT-R") (class "Default")
      (node (ref "R151") (pin "1") (pinfunction "1_1") (pintype "passive"))
      (node (ref "U1") (pin "18") (pinfunction "PC3_18") (pintype "passive"))
      (node (ref "U3") (pin "8") (pinfunction "FAULT_8") (pintype "passive"))
    )
    (net (code "42") (name "/HEAD_IO_L") (class "Default")
      (node (ref "U1") (pin "77") (pinfunction "PA15/JTDI_77") (pintype "passive"))
      (node (ref "U7") (pin "4") (pinfunction "A2_4") (pintype "passive"))
    )
    (net (code "43") (name "/HEAD_IO_L1") (class "Default")
      (node (ref "C28") (pin "1") (pinfunction "1_1") (pintype "passive"))
      (node (ref "J5") (pin "2") (pinfunction "2_2") (pintype "passive"))
      (node (ref "R45") (pin "1") (pinfunction "1_1") (pintype "passive"))
      (node (ref "U7") (pin "16") (pinfunction "B2_16") (pintype "passive"))
    )
    (net (code "44") (name "/HEAD_IO_R") (class "Default")
      (node (ref "U1") (pin "71") (pinfunction "PA12_71") (pintype "passive"))
      (node (ref "U7") (pin "5") (pinfunction "A3_5") (pintype "passive"))
    )
    (net (code "45") (name "/HEAD_IO_R1") (class "Default")
      (node (ref "C27") (pin "1") (pinfunction "1_1") (pintype "passive"))
      (node (ref "J5") (pin "3") (pinfunction "3_3") (pintype "passive"))
      (node (ref "R44") (pin "1") (pinfunction "1_1") (pintype "passive"))
      (node (ref "U7") (pin "15") (pinfunction "B3_15") (pintype "passive"))
    )
    (net (code "46") (name "/Hall-L-B") (class "Default")
      (node (ref "C47") (pin "1") (pinfunction "1_1") (pintype "passive"))
      (node (ref "J2") (pin "4") (pinfunction "4_4") (pintype "passive"))
      (node (ref "R63") (pin "2") (pinfunction "2_2") (pintype "passive"))
      (node (ref "U11") (pin "16") (pinfunction "B2_16") (pintype "passive"))
    )
    (net (code "47") (name "/Hall-L-B1") (class "Default")
      (node (ref "U1") (pin "53") (pinfunction "PB14_53") (pintype "passive"))
      (node (ref "U11") (pin "4") (pinfunction "A2_4") (pintype "passive"))
    )
    (net (code "48") (name "/Hall-L-G") (class "Default")
      (node (ref "C46") (pin "1") (pinfunction "1_1") (pintype "passive"))
      (node (ref "J2") (pin "3") (pinfunction "3_3") (pintype "passive"))
      (node (ref "R62") (pin "2") (pinfunction "2_2") (pintype "passive"))
      (node (ref "U11") (pin "17") (pinfunction "B1_17") (pintype "passive"))
    )
    (net (code "49") (name "/Hall-L-G1") (class "Default")
      (node (ref "U1") (pin "54") (pinfunction "PB15_54") (pintype "passive"))
      (node (ref "U11") (pin "3") (pinfunction "A1_3") (pintype "passive"))
    )
    (net (code "50") (name "/Hall-L-Y") (class "Default")
      (node (ref "C45") (pin "1") (pinfunction "1_1") (pintype "passive"))
      (node (ref "J2") (pin "2") (pinfunction "2_2") (pintype "passive"))
      (node (ref "R61") (pin "2") (pinfunction "2_2") (pintype "passive"))
      (node (ref "U11") (pin "18") (pinfunction "B0_18") (pintype "passive"))
    )
    (net (code "51") (name "/Hall-L-Y1") (class "Default")
      (node (ref "U1") (pin "55") (pinfunction "PD8_55") (pintype "passive"))
      (node (ref "U11") (pin "2") (pinfunction "A0_2") (pintype "passive"))
    )
    (net (code "52") (name "/Hall-R-B") (class "Default")
      (node (ref "C60") (pin "1") (pinfunction "1_1") (pintype "passive"))
      (node (ref "J3") (pin "4") (pinfunction "4_4") (pintype "passive"))
      (node (ref "R74") (pin "2") (pinfunction "2_2") (pintype "passive"))
      (node (ref "U13") (pin "16") (pinfunction "B2_16") (pintype "passive"))
    )
    (net (code "53") (name "/Hall-R-B1") (class "Default")
      (node (ref "U1") (pin "7") (pinfunction "PC13-TAMPER-RTC_7") (pintype "passive"))
      (node (ref "U13") (pin "4") (pinfunction "A2_4") (pintype "passive"))
    )
    (net (code "54") (name "/Hall-R-G") (class "Default")
      (node (ref "C59") (pin "1") (pinfunction "1_1") (pintype "passive"))
      (node (ref "J3") (pin "3") (pinfunction "3_3") (pintype "passive"))
      (node (ref "R73") (pin "2") (pinfunction "2_2") (pintype "passive"))
      (node (ref "U13") (pin "17") (pinfunction "B1_17") (pintype "passive"))
    )
    (net (code "55") (name "/Hall-R-G1") (class "Default")
      (node (ref "U1") (pin "8") (pinfunction "PC14-OSC32_IN_8") (pintype "passive"))
      (node (ref "U13") (pin "3") (pinfunction "A1_3") (pintype "passive"))
    )
    (net (code "56") (name "/Hall-R-Y") (class "Default")
      (node (ref "C58") (pin "1") (pinfunction "1_1") (pintype "passive"))
      (node (ref "J3") (pin "2") (pinfunction "2_2") (pintype "passive"))
      (node (ref "R72") (pin "2") (pinfunction "2_2") (pintype "passive"))
      (node (ref "U13") (pin "18") (pinfunction "B0_18") (pintype "passive"))
    )
    (net (code "57") (name "/Hall-R-Y1") (class "Default")
      (node (ref "U1") (pin "25") (pinfunction "PA2_25") (pintype "passive"))
      (node (ref "U13") (pin "2") (pinfunction "A0_2") (pintype "passive"))
    )
    (net (code "58") (name "/IIC-SCL-L") (class "Default")
      (node (ref "R147") (pin "2") (pinfunction "2_2") (pintype "passive"))
      (node (ref "U1") (pin "47") (pinfunction "PB10_47") (pintype "passive"))
    )
    (net (code "59") (name "/IIC-SCL-R") (class "Default")
      (node (ref "R150") (pin "2") (pinfunction "2_2") (pintype "passive"))
      (node (ref "U1") (pin "92") (pinfunction "PB6_92") (pintype "passive"))
    )
    (net (code "60") (name "/IIC-SDA-L") (class "Default")
      (node (ref "R60") (pin "2") (pinfunction "2_2") (pintype "passive"))
      (node (ref "U1") (pin "48") (pinfunction "PB11_48") (pintype "passive"))
    )
    (net (code "61") (name "/IIC-SDA-R") (class "Default")
      (node (ref "R149") (pin "2") (pinfunction "2_2") (pintype "passive"))
      (node (ref "U1") (pin "93") (pinfunction "PB7_93") (pintype "passive"))
    )
    (net (code "62") (name "/MOT-H-A") (class "Default")
      (node (ref "J4") (pin "6") (pinfunction "6_6") (pintype "passive"))
      (node (ref "Q17") (pin "5") (pinfunction "D_5") (pintype "passive"))
    )
    (net (code "63") (name "/MOT-H-B") (class "Default")
      (node (ref "J4") (pin "5") (pinfunction "5_5") (pintype "passive"))
      (node (ref "Q18") (pin "5") (pinfunction "D_5") (pintype "passive"))
    )
    (net (code "64") (name "/MOT-L-B") (class "Default")
      (node (ref "C5") (pin "2") (pinfunction "2_2") (pintype "passive"))
      (node (ref "J9") (pin "1") (pinfunction "1_1") (pintype "passive"))
      (node (ref "Q1") (pin "2") (pinfunction "S_2") (pintype "input"))
      (node (ref "Q7") (pin "3") (pinfunction "D_3") (pintype "input"))
      (node (ref "R1") (pin "1") (pinfunction "1_1") (pintype "passive"))
      (node (ref "U2") (pin "26") (pinfunction "VS1_26") (pintype "passive"))
    )
    (net (code "65") (name "/MOT-L-G") (class "Default")
      (node (ref "C8") (pin "2") (pinfunction "2_2") (pintype "passive"))
      (node (ref "J9") (pin "2") (pinfunction "2_2") (pintype "passive"))
      (node (ref "Q2") (pin "2") (pinfunction "S_2") (pintype "input"))
      (node (ref "Q8") (pin "3") (pinfunction "D_3") (pintype "input"))
      (node (ref "R2") (pin "1") (pinfunction "1_1") (pintype "passive"))
      (node (ref "U2") (pin "22") (pinfunction "VS2_22") (pintype "passive"))
    )
    (net (code "66") (name "/MOT-L-Y") (class "Default")
      (node (ref "C10") (pin "2") (pinfunction "2_2") (pintype "passive"))
      (node (ref "J9") (pin "3") (pinfunction "3_3") (pintype "passive"))
      (node (ref "Q3") (pin "2") (pinfunction "S_2") (pintype "input"))
      (node (ref "Q9") (pin "3") (pinfunction "D_3") (pintype "input"))
      (node (ref "R3") (pin "1") (pinfunction "1_1") (pintype "passive"))
      (node (ref "U2") (pin "18") (pinfunction "VS3_18") (pintype "passive"))
    )
    (net (code "67") (name "/MOT-R-B") (class "Default")
      (node (ref "C6") (pin "2") (pinfunction "2_2") (pintype "passive"))
      (node (ref "J9") (pin "4") (pinfunction "4_4") (pintype "passive"))
      (node (ref "Q10") (pin "3") (pinfunction "D_3") (pintype "input"))
      (node (ref "Q4") (pin "2") (pinfunction "S_2") (pintype "input"))
      (node (ref "R4") (pin "1") (pinfunction "1_1") (pintype "passive"))
      (node (ref "U3") (pin "26") (pinfunction "VS1_26") (pintype "passive"))
    )
    (net (code "68") (name "/MOT-R-G") (class "Default")
      (node (ref "C9") (pin "2") (pinfunction "2_2") (pintype "passive"))
      (node (ref "J9") (pin "5") (pinfunction "5_5") (pintype "passive"))
      (node (ref "Q11") (pin "3") (pinfunction "D_3") (pintype "input"))
      (node (ref "Q5") (pin "2") (pinfunction "S_2") (pintype "input"))
      (node (ref "R5") (pin "1") (pinfunction "1_1") (pintype "passive"))
      (node (ref "U3") (pin "22") (pinfunction "VS2_22") (pintype "passive"))
    )
    (net (code "69") (name "/MOT-R-Y") (class "Default")
      (node (ref "C11") (pin "2") (pinfunction "2_2") (pintype "passive"))
      (node (ref "J9") (pin "6") (pinfunction "6_6") (pintype "passive"))
      (node (ref "Q12") (pin "3") (pinfunction "D_3") (pintype "input"))
      (node (ref "Q6") (pin "2") (pinfunction "S_2") (pintype "input"))
      (node (ref "R6") (pin "2") (pinfunction "2_2") (pintype "passive"))
      (node (ref "U3") (pin "18") (pinfunction "VS3_18") (pintype "passive"))
    )
    (net (code "70") (name "/MOT-STOP1") (class "Default")
      (node (ref "U1") (pin "1") (pinfunction "PE2_1") (pintype "passive"))
      (node (ref "U13") (pin "9") (pinfunction "A7_9") (pintype "passive"))
    )
    (net (code "71") (name "/MOT-W-LA") (class "Default")
      (node (ref "J6") (pin "6") (pinfunction "6_6") (pintype "passive"))
      (node (ref "Q13") (pin "5") (pinfunction "D_5") (pintype "passive"))
    )
    (net (code "72") (name "/MOT-W-LB") (class "Default")
      (node (ref "J6") (pin "5") (pinfunction "5_5") (pintype "passive"))
      (node (ref "Q14") (pin "5") (pinfunction "D_5") (pintype "passive"))
    )
    (net (code "73") (name "/MOT-W-RA") (class "Default")
      (node (ref "J7") (pin "7") (pinfunction "7_7") (pintype "passive"))
      (node (ref "Q19") (pin "5") (pinfunction "D_5") (pintype "passive"))
    )
    (net (code "74") (name "/MOT-W-RB") (class "Default")
      (node (ref "J7") (pin "6") (pinfunction "6_6") (pintype "passive"))
      (node (ref "Q20") (pin "5") (pinfunction "D_5") (pintype "passive"))
    )
    (net (code "75") (name "/PWM-1-A") (class "Default")
      (node (ref "R141") (pin "2") (pinfunction "2_2") (pintype "passive"))
      (node (ref "U5") (pin "3") (pinfunction "Y_3") (pintype "output"))
    )
    (net (code "76") (name "/PWM-1-B") (class "Default")
      (node (ref "R143") (pin "2") (pinfunction "2_2") (pintype "passive"))
      (node (ref "U5") (pin "6") (pinfunction "Y_6") (pintype "output"))
    )
    (net (code "77") (name "/PWM-2-A") (class "Default")
      (node (ref "R107") (pin "2") (pinfunction "2_2") (pintype "passive"))
      (node (ref "U5") (pin "8") (pinfunction "Y_8") (pintype "output"))
    )
    (net (code "78") (name "/PWM-2-B") (class "Default")
      (node (ref "R108") (pin "2") (pinfunction "2_2") (pintype "passive"))
      (node (ref "U5") (pin "11") (pinfunction "Y_11") (pintype "output"))
    )
    (net (code "79") (name "/PWM-3-A") (class "Default")
      (node (ref "R132") (pin "2") (pinfunction "2_2") (pintype "passive"))
      (node (ref "U8") (pin "3") (pinfunction "Y_3") (pintype "output"))
    )
    (net (code "80") (name "/PWM-3-B") (class "Default")
      (node (ref "R133") (pin "2") (pinfunction "2_2") (pintype "passive"))
      (node (ref "U8") (pin "6") (pinfunction "Y_6") (pintype "output"))
    )
    (net (code "81") (name "/PWM-HIN1-L") (class "Default")
      (node (ref "U1") (pin "39") (pinfunction "PE8_39") (pintype "passive"))
      (node (ref "U2") (pin "2") (pinfunction "HIN1_2") (pintype "passive"))
    )
    (net (code "82") (name "/PWM-HIN1-R") (class "Default")
      (node (ref "U1") (pin "32") (pinfunction "PA7_32") (pintype "passive"))
      (node (ref "U3") (pin "2") (pinfunction "HIN1_2") (pintype "passive"))
    )
    (net (code "83") (name "/PWM-HIN2-L") (class "Default")
      (node (ref "U1") (pin "41") (pinfunction "PE10_41") (pintype "passive"))
      (node (ref "U2") (pin "3") (pinfunction "HIN2_3") (pintype "passive"))
    )
    (net (code "84") (name "/PWM-HIN2-R") (class "Default")
      (node (ref "U1") (pin "35") (pinfunction "PB0_35") (pintype "passive"))
      (node (ref "U3") (pin "3") (pinfunction "HIN2_3") (pintype "passive"))
    )
    (net (code "85") (name "/PWM-HIN3-L") (class "Default")
      (node (ref "U1") (pin "43") (pinfunction "PE12_43") (pintype "passive"))
      (node (ref "U2") (pin "4") (pinfunction "HIN3_4") (pintype "passive"))
    )
    (net (code "86") (name "/PWM-HIN3-R") (class "Default")
      (node (ref "U1") (pin "36") (pinfunction "PB1_36") (pintype "passive"))
      (node (ref "U3") (pin "4") (pinfunction "HIN3_4") (pintype "passive"))
    )
    (net (code "87") (name "/PWM-HO1-L") (class "Default")
      (node (ref "Q1") (pin "1") (pinfunction "G_1") (pintype "input"))
      (node (ref "R1") (pin "2") (pinfunction "2_2") (pintype "passive"))
      (node (ref "R7") (pin "1") (pinfunction "1_1") (pintype "passive"))
    )
    (net (code "88") (name "/PWM-HO1-R") (class "Default")
      (node (ref "Q4") (pin "1") (pinfunction "G_1") (pintype "input"))
      (node (ref "R4") (pin "2") (pinfunction "2_2") (pintype "passive"))
      (node (ref "R8") (pin "1") (pinfunction "1_1") (pintype "passive"))
    )
    (net (code "89") (name "/PWM-HO2-L") (class "Default")
      (node (ref "Q2") (pin "1") (pinfunction "G_1") (pintype "input"))
      (node (ref "R2") (pin "2") (pinfunction "2_2") (pintype "passive"))
      (node (ref "R9") (pin "1") (pinfunction "1_1") (pintype "passive"))
    )
    (net (code "90") (name "/PWM-HO2-R") (class "Default")
      (node (ref "Q5") (pin "1") (pinfunction "G_1") (pintype "input"))
      (node (ref "R10") (pin "1") (pinfunction "1_1") (pintype "passive"))
      (node (ref "R5") (pin "2") (pinfunction "2_2") (pintype "passive"))
    )
    (net (code "91") (name "/PWM-HO3-L") (class "Default")
      (node (ref "Q3") (pin "1") (pinfunction "G_1") (pintype "input"))
      (node (ref "R16") (pin "1") (pinfunction "1_1") (pintype "passive"))
      (node (ref "R3") (pin "2") (pinfunction "2_2") (pintype "passive"))
    )
    (net (code "92") (name "/PWM-HO3-R") (class "Default")
      (node (ref "Q6") (pin "1") (pinfunction "G_1") (pintype "input"))
      (node (ref "R17") (pin "1") (pinfunction "1_1") (pintype "passive"))
      (node (ref "R6") (pin "1") (pinfunction "1_1") (pintype "passive"))
    )
    (net (code "93") (name "/PWM-IO-1") (class "Default")
      (node (ref "R81") (pin "2") (pinfunction "2_2") (pintype "passive"))
      (node (ref "U1") (pin "59") (pinfunction "PD12_59") (pintype "passive"))
      (node (ref "U5") (pin "1") (pinfunction "A_1") (pintype "input"))
      (node (ref "U5") (pin "5") (pinfunction "B_5") (pintype "input"))
    )
    (net (code "94") (name "/PWM-IO-2") (class "Default")
      (node (ref "R80") (pin "2") (pinfunction "2_2") (pintype "passive"))
      (node (ref "U1") (pin "60") (pinfunction "PD13_60") (pintype "passive"))
      (node (ref "U5") (pin "13") (pinfunction "B_13") (pintype "input"))
      (node (ref "U5") (pin "9") (pinfunction "A_9") (pintype "input"))
    )
    (net (code "95") (name "/PWM-IO-3") (class "Default")
      (node (ref "R79") (pin "2") (pinfunction "2_2") (pintype "passive"))
      (node (ref "U1") (pin "61") (pinfunction "PD14_61") (pintype "passive"))
      (node (ref "U8") (pin "1") (pinfunction "A_1") (pintype "input"))
      (node (ref "U8") (pin "5") (pinfunction "B_5") (pintype "input"))
    )
    (net (code "96") (name "/PWM-LIN1-L") (class "Default")
      (node (ref "U1") (pin "40") (pinfunction "PE9_40") (pintype "passive"))
      (node (ref "U2") (pin "5") (pinfunction "LIN1_5") (pintype "passive"))
    )
    (net (code "97") (name "/PWM-LIN1-R") (class "Default")
      (node (ref "U1") (pin "63") (pinfunction "PC6_63") (pintype "passive"))
      (node (ref "U3") (pin "5") (pinfunction "LIN1_5") (pintype "passive"))
    )
    (net (code "98") (name "/PWM-LIN2-L") (class "Default")
      (node (ref "U1") (pin "42") (pinfunction "PE11_42") (pintype "passive"))
      (node (ref "U2") (pin "6") (pinfunction "LIN2_6") (pintype "passive"))
    )
    (net (code "99") (name "/PWM-LIN2-R") (class "Default")
      (node (ref "U1") (pin "64") (pinfunction "PC7_64") (pintype "passive"))
      (node (ref "U3") (pin "6") (pinfunction "LIN2_6") (pintype "passive"))
    )
    (net (code "100") (name "/PWM-LIN3-L") (class "Default")
      (node (ref "U1") (pin "44") (pinfunction "PE13_44") (pintype "passive"))
      (node (ref "U2") (pin "7") (pinfunction "LIN3_7") (pintype "passive"))
    )
    (net (code "101") (name "/PWM-LIN3-R") (class "Default")
      (node (ref "U1") (pin "65") (pinfunction "PC8_65") (pintype "passive"))
      (node (ref "U3") (pin "7") (pinfunction "LIN3_7") (pintype "passive"))
    )
    (net (code "102") (name "/PWM-LO1-L") (class "Default")
      (node (ref "Q7") (pin "1") (pinfunction "G_1") (pintype "input"))
      (node (ref "R18") (pin "1") (pinfunction "1_1") (pintype "passive"))
      (node (ref "R28") (pin "1") (pinfunction "1_1") (pintype "passive"))
    )
    (net (code "103") (name "/PWM-LO1-R") (class "Default")
      (node (ref "Q10") (pin "1") (pinfunction "G_1") (pintype "input"))
      (node (ref "R21") (pin "1") (pinfunction "1_1") (pintype "passive"))
      (node (ref "R29") (pin "1") (pinfunction "1_1") (pintype "passive"))
    )
    (net (code "104") (name "/PWM-LO2-L") (class "Default")
      (node (ref "Q8") (pin "1") (pinfunction "G_1") (pintype "input"))
      (node (ref "R19") (pin "2") (pinfunction "2_2") (pintype "passive"))
      (node (ref "R32") (pin "1") (pinfunction "1_1") (pintype "passive"))
    )
    (net (code "105") (name "/PWM-LO2-R") (class "Default")
      (node (ref "Q11") (pin "1") (pinfunction "G_1") (pintype "input"))
      (node (ref "R22") (pin "1") (pinfunction "1_1") (pintype "passive"))
      (node (ref "R33") (pin "1") (pinfunction "1_1") (pintype "passive"))
    )
    (net (code "106") (name "/PWM-LO3-L") (class "Default")
      (node (ref "Q9") (pin "1") (pinfunction "G_1") (pintype "input"))
      (node (ref "R20") (pin "2") (pinfunction "2_2") (pintype "passive"))
      (node (ref "R36") (pin "1") (pinfunction "1_1") (pintype "passive"))
    )
    (net (code "107") (name "/PWM-LO3-R") (class "Default")
      (node (ref "Q12") (pin "1") (pinfunction "G_1") (pintype "input"))
      (node (ref "R23") (pin "1") (pinfunction "1_1") (pintype "passive"))
      (node (ref "R37") (pin "1") (pinfunction "1_1") (pintype "passive"))
    )
    (net (code "108") (name "/Ref-Wing") (class "Default")
      (node (ref "C52") (pin "1") (pinfunction "1_1") (pintype "passive"))
      (node (ref "R67") (pin "1") (pinfunction "1_1") (pintype "passive"))
      (node (ref "R69") (pin "2") (pinfunction "2_2") (pintype "passive"))
      (node (ref "U10") (pin "2") (pinfunction "2_2") (pintype "passive"))
      (node (ref "U10") (pin "6") (pinfunction "6_6") (pintype "passive"))
      (node (ref "U9") (pin "2") (pinfunction "2_2") (pintype "passive"))
      (node (ref "U9") (pin "6") (pinfunction "6_6") (pintype "passive"))
    )
    (net (code "109") (name "/STOP-BLDC") (class "Default")
      (node (ref "P1") (pin "6") (pinfunction "6_6") (pintype "passive"))
      (node (ref "R134") (pin "2") (pinfunction "2_2") (pintype "passive"))
      (node (ref "U13") (pin "11") (pinfunction "B7_11") (pintype "passive"))
    )
    (net (code "110") (name "/SWCLK") (class "Default")
      (node (ref "D7") (pin "1") (pinfunction "1_1") (pintype "passive"))
      (node (ref "J1") (pin "2") (pinfunction "2_2") (pintype "passive"))
      (node (ref "U1") (pin "76") (pinfunction "PA14/JTCK/SWCLK_76") (pintype "passive"))
    )
    (net (code "111") (name "/SWDIO-103") (class "Default")
      (node (ref "D7") (pin "2") (pinfunction "2_2") (pintype "passive"))
      (node (ref "J1") (pin "3") (pinfunction "3_3") (pintype "passive"))
      (node (ref "U1") (pin "72") (pinfunction "PA13/JTMS/SWDIO_72") (pintype "passive"))
    )
    (net (code "112") (name "/UART1-RX") (class "Default")
      (node (ref "D8") (pin "2") (pinfunction "2_2") (pintype "passive"))
      (node (ref "J1") (pin "8") (pinfunction "8_8") (pintype "passive"))
      (node (ref "U1") (pin "69") (pinfunction "PA10_69") (pintype "passive"))
    )
    (net (code "113") (name "/UART1-TX") (class "Default")
      (node (ref "D8") (pin "1") (pinfunction "1_1") (pintype "passive"))
      (node (ref "J1") (pin "7") (pinfunction "7_7") (pintype "passive"))
      (node (ref "U1") (pin "68") (pinfunction "PA9_68") (pintype "passive"))
    )
    (net (code "116") (name "/UART4-RX") (class "Default")
      (node (ref "D11") (pin "1") (pinfunction "1_1") (pintype "passive"))
      (node (ref "P1") (pin "5") (pinfunction "5_5") (pintype "passive"))
      (node (ref "U1") (pin "79") (pinfunction "PC11_79") (pintype "passive"))
    )
    (net (code "117") (name "/UART4-TX") (class "Default")
      (node (ref "D11") (pin "2") (pinfunction "2_2") (pintype "passive"))
      (node (ref "P1") (pin "4") (pinfunction "4_4") (pintype "passive"))
      (node (ref "U1") (pin "78") (pinfunction "PC10_78") (pintype "passive"))
    )
    (net (code "118") (name "/WHEEL-Float-L") (class "Default")
      (node (ref "C51") (pin "1") (pinfunction "1_1") (pintype "passive"))
      (node (ref "J8") (pin "2") (pinfunction "2_2") (pintype "passive"))
      (node (ref "R148") (pin "2") (pinfunction "2_2") (pintype "passive"))
      (node (ref "U11") (pin "12") (pinfunction "B6_12") (pintype "passive"))
    )
    (net (code "119") (name "/WHEEL-Float-L1") (class "Default")
      (node (ref "U1") (pin "45") (pinfunction "PE14_45") (pintype "passive"))
      (node (ref "U11") (pin "8") (pinfunction "A6_8") (pintype "passive"))
    )
    (net (code "120") (name "/WHEEL-Float-R") (class "Default")
      (node (ref "C64") (pin "1") (pinfunction "1_1") (pintype "passive"))
      (node (ref "J10") (pin "2") (pinfunction "2_2") (pintype "passive"))
      (node (ref "R78") (pin "2") (pinfunction "2_2") (pintype "passive"))
      (node (ref "U13") (pin "15") (pinfunction "B3_15") (pintype "passive"))
    )
    (net (code "121") (name "/WHEEL-Float-R1") (class "Default")
      (node (ref "U1") (pin "5") (pinfunction "PE6_5") (pintype "passive"))
      (node (ref "U13") (pin "5") (pinfunction "A3_5") (pintype "passive"))
    )
    (net (code "122") (name "/W_IO_L") (class "Default")
      (node (ref "C74") (pin "1") (pinfunction "1_1") (pintype "passive"))
      (node (ref "R85") (pin "1") (pinfunction "1_1") (pintype "passive"))
      (node (ref "R93") (pin "1") (pinfunction "1_1") (pintype "passive"))
      (node (ref "U1") (pin "62") (pinfunction "PD15_62") (pintype "passive"))
      (node (ref "U10") (pin "7") (pinfunction "7_7") (pintype "passive"))
    )
    (net (code "123") (name "/W_IO_L1") (class "Default")
      (node (ref "C23") (pin "1") (pinfunction "1_1") (pintype "passive"))
      (node (ref "J6") (pin "2") (pinfunction "2_2") (pintype "passive"))
      (node (ref "R40") (pin "1") (pinfunction "1_1") (pintype "passive"))
      (node (ref "R93") (pin "2") (pinfunction "2_2") (pintype "passive"))
      (node (ref "U10") (pin "5") (pinfunction "5_5") (pintype "passive"))
    )
    (net (code "124") (name "/W_IO_R") (class "Default")
      (node (ref "C73") (pin "1") (pinfunction "1_1") (pintype "passive"))
      (node (ref "R83") (pin "1") (pinfunction "1_1") (pintype "passive"))
      (node (ref "R92") (pin "1") (pinfunction "1_1") (pintype "passive"))
      (node (ref "U1") (pin "67") (pinfunction "PA8_67") (pintype "passive"))
      (node (ref "U9") (pin "7") (pinfunction "7_7") (pintype "passive"))
    )
    (net (code "125") (name "/W_IO_R1") (class "Default")
      (node (ref "C25") (pin "1") (pinfunction "1_1") (pintype "passive"))
      (node (ref "J7") (pin "2") (pinfunction "2_2") (pintype "passive"))
      (node (ref "R42") (pin "1") (pinfunction "1_1") (pintype "passive"))
      (node (ref "R92") (pin "2") (pinfunction "2_2") (pintype "passive"))
      (node (ref "U9") (pin "5") (pinfunction "5_5") (pintype "passive"))
    )
    (net (code "126") (name "COM-L") (class "Default")
      (node (ref "Q7") (pin "2") (pinfunction "S_2") (pintype "input"))
      (node (ref "Q8") (pin "2") (pinfunction "S_2") (pintype "input"))
      (node (ref "Q9") (pin "2") (pinfunction "S_2") (pintype "input"))
      (node (ref "R12") (pin "1") (pinfunction "1_1") (pintype "passive"))
      (node (ref "R18") (pin "2") (pinfunction "2_2") (pintype "passive"))
      (node (ref "R19") (pin "1") (pinfunction "1_1") (pintype "passive"))
      (node (ref "R20") (pin "1") (pinfunction "1_1") (pintype "passive"))
      (node (ref "R24") (pin "2") (pinfunction "2_2") (pintype "passive"))
      (node (ref "R30") (pin "2") (pinfunction "2_2") (pintype "passive"))
      (node (ref "U2") (pin "13") (pinfunction "COM_13") (pintype "passive"))
    )
    (net (code "127") (name "COM-R") (class "Default")
      (node (ref "Q10") (pin "2") (pinfunction "S_2") (pintype "input"))
      (node (ref "Q11") (pin "2") (pinfunction "S_2") (pintype "input"))
      (node (ref "Q12") (pin "2") (pinfunction "S_2") (pintype "input"))
      (node (ref "R14") (pin "1") (pinfunction "1_1") (pintype "passive"))
      (node (ref "R21") (pin "2") (pinfunction "2_2") (pintype "passive"))
      (node (ref "R22") (pin "2") (pinfunction "2_2") (pintype "passive"))
      (node (ref "R23") (pin "2") (pinfunction "2_2") (pintype "passive"))
      (node (ref "R25") (pin "2") (pinfunction "2_2") (pintype "passive"))
      (node (ref "R31") (pin "2") (pinfunction "2_2") (pintype "passive"))
      (node (ref "U3") (pin "13") (pinfunction "COM_13") (pintype "passive"))
    )
    (net (code "128") (name "GND") (class "Default")
      (node (ref "C1") (pin "2") (pinfunction "2_2") (pintype "passive"))
      (node (ref "C12") (pin "2") (pinfunction "2_2") (pintype "passive"))
      (node (ref "C13") (pin "2") (pinfunction "2_2") (pintype "passive"))
      (node (ref "C14") (pin "2") (pinfunction "2_2") (pintype "passive"))
      (node (ref "C15") (pin "2") (pinfunction "2_2") (pintype "passive"))
      (node (ref "C16") (pin "1") (pinfunction "1_1") (pintype "passive"))
      (node (ref "C17") (pin "1") (pinfunction "1_1") (pintype "passive"))
      (node (ref "C18") (pin "1") (pinfunction "1_1") (pintype "passive"))
      (node (ref "C19") (pin "2") (pinfunction "2_2") (pintype "passive"))
      (node (ref "C2") (pin "2") (pinfunction "2_2") (pintype "passive"))
      (node (ref "C20") (pin "1") (pinfunction "1_1") (pintype "passive"))
      (node (ref "C21") (pin "2") (pinfunction "2_2") (pintype "passive"))
      (node (ref "C22") (pin "1") (pinfunction "1_1") (pintype "passive"))
      (node (ref "C23") (pin "2") (pinfunction "2_2") (pintype "passive"))
      (node (ref "C24") (pin "2") (pinfunction "2_2") (pintype "passive"))
      (node (ref "C25") (pin "2") (pinfunction "2_2") (pintype "passive"))
      (node (ref "C26") (pin "2") (pinfunction "2_2") (pintype "passive"))
      (node (ref "C27") (pin "2") (pinfunction "2_2") (pintype "passive"))
      (node (ref "C28") (pin "2") (pinfunction "2_2") (pintype "passive"))
      (node (ref "C29") (pin "2") (pinfunction "2_2") (pintype "passive"))
      (node (ref "C3") (pin "2") (pinfunction "2_2") (pintype "passive"))
      (node (ref "C30") (pin "2") (pinfunction "2_2") (pintype "passive"))
      (node (ref "C31") (pin "2") (pinfunction "2_2") (pintype "passive"))
      (node (ref "C32") (pin "1") (pinfunction "1_1") (pintype "passive"))
      (node (ref "C33") (pin "1") (pinfunction "1_1") (pintype "passive"))
      (node (ref "C34") (pin "1") (pinfunction "1_1") (pintype "passive"))
      (node (ref "C35") (pin "1") (pinfunction "1_1") (pintype "passive"))
      (node (ref "C36") (pin "2") (pinfunction "2_2") (pintype "passive"))
      (node (ref "C37") (pin "1") (pinfunction "1_1") (pintype "passive"))
      (node (ref "C38") (pin "2") (pinfunction "2_2") (pintype "passive"))
      (node (ref "C39") (pin "2") (pinfunction "2_2") (pintype "passive"))
      (node (ref "C4") (pin "2") (pinfunction "2_2") (pintype "passive"))
      (node (ref "C40") (pin "2") (pinfunction "2_2") (pintype "passive"))
      (node (ref "C41") (pin "2") (pinfunction "2_2") (pintype "passive"))
      (node (ref "C42") (pin "1") (pinfunction "1_1") (pintype "passive"))
      (node (ref "C43") (pin "2") (pinfunction "2_2") (pintype "passive"))
      (node (ref "C44") (pin "1") (pinfunction "1_1") (pintype "passive"))
      (node (ref "C45") (pin "2") (pinfunction "2_2") (pintype "passive"))
      (node (ref "C46") (pin "2") (pinfunction "2_2") (pintype "passive"))
      (node (ref "C47") (pin "2") (pinfunction "2_2") (pintype "passive"))
      (node (ref "C48") (pin "2") (pinfunction "2_2") (pintype "passive"))
      (node (ref "C49") (pin "2") (pinfunction "2_2") (pintype "passive"))
      (node (ref "C50") (pin "2") (pinfunction "2_2") (pintype "passive"))
      (node (ref "C51") (pin "2") (pinfunction "2_2") (pintype "passive"))
      (node (ref "C52") (pin "2") (pinfunction "2_2") (pintype "passive"))
      (node (ref "C53") (pin "2") (pinfunction "2_2") (pintype "passive"))
      (node (ref "C54") (pin "2") (pinfunction "2_2") (pintype "passive"))
      (node (ref "C55") (pin "2") (pinfunction "2_2") (pintype "passive"))
      (node (ref "C56") (pin "2") (pinfunction "2_2") (pintype "passive"))
      (node (ref "C57") (pin "1") (pinfunction "1_1") (pintype "passive"))
      (node (ref "C58") (pin "2") (pinfunction "2_2") (pintype "passive"))
      (node (ref "C59") (pin "2") (pinfunction "2_2") (pintype "passive"))
      (node (ref "C60") (pin "2") (pinfunction "2_2") (pintype "passive"))
      (node (ref "C61") (pin "2") (pinfunction "2_2") (pintype "passive"))
      (node (ref "C62") (pin "2") (pinfunction "2_2") (pintype "passive"))
      (node (ref "C63") (pin "2") (pinfunction "2_2") (pintype "passive"))
      (node (ref "C64") (pin "2") (pinfunction "2_2") (pintype "passive"))
      (node (ref "C65") (pin "1") (pinfunction "1_1") (pintype "passive"))
      (node (ref "C66") (pin "1") (pinfunction "1_1") (pintype "passive"))
      (node (ref "C67") (pin "1") (pinfunction "1_1") (pintype "passive"))
      (node (ref "C68") (pin "2") (pinfunction "2_2") (pintype "passive"))
      (node (ref "C69") (pin "2") (pinfunction "2_2") (pintype "passive"))
      (node (ref "C7") (pin "1") (pinfunction "1_1") (pintype "passive"))
      (node (ref "C70") (pin "2") (pinfunction "2_2") (pintype "passive"))
      (node (ref "C71") (pin "2") (pinfunction "2_2") (pintype "passive"))
      (node (ref "C72") (pin "1") (pinfunction "1_1") (pintype "passive"))
      (node (ref "C73") (pin "2") (pinfunction "2_2") (pintype "passive"))
      (node (ref "C74") (pin "2") (pinfunction "2_2") (pintype "passive"))
      (node (ref "C75") (pin "2") (pinfunction "2_2") (pintype "passive"))
      (node (ref "C76") (pin "2") (pinfunction "2_2") (pintype "passive"))
      (node (ref "C77") (pin "2") (pinfunction "2_2") (pintype "passive"))
      (node (ref "C78") (pin "2") (pinfunction "2_2") (pintype "passive"))
      (node (ref "C79") (pin "2") (pinfunction "2_2") (pintype "passive"))
      (node (ref "C80") (pin "1") (pinfunction "1_1") (pintype "passive"))
      (node (ref "C81") (pin "2") (pinfunction "2_2") (pintype "passive"))
      (node (ref "C82") (pin "2") (pinfunction "2_2") (pintype "passive"))
      (node (ref "C83") (pin "2") (pinfunction "2_2") (pintype "passive"))
      (node (ref "C84") (pin "2") (pinfunction "2_2") (pintype "passive"))
      (node (ref "C85") (pin "2") (pinfunction "2_2") (pintype "passive"))
      (node (ref "C86") (pin "2") (pinfunction "2_2") (pintype "passive"))
      (node (ref "C87") (pin "2") (pinfunction "2_2") (pintype "passive"))
      (node (ref "C88") (pin "1") (pinfunction "1_1") (pintype "passive"))
      (node (ref "C89") (pin "2") (pinfunction "2_2") (pintype "passive"))
      (node (ref "C90") (pin "2") (pinfunction "2_2") (pintype "passive"))
      (node (ref "C91") (pin "2") (pinfunction "2_2") (pintype "passive"))
      (node (ref "C92") (pin "1") (pinfunction "1_1") (pintype "passive"))
      (node (ref "C93") (pin "1") (pinfunction "1_1") (pintype "passive"))
      (node (ref "D11") (pin "3") (pintype "passive"))
      (node (ref "D7") (pin "3") (pintype "passive"))
      (node (ref "D8") (pin "3") (pintype "passive"))
      (node (ref "J1") (pin "6") (pinfunction "6_6") (pintype "passive"))
      (node (ref "J10") (pin "1") (pinfunction "1_1") (pintype "passive"))
      (node (ref "J2") (pin "1") (pinfunction "1_1") (pintype "passive"))
      (node (ref "J3") (pin "1") (pinfunction "1_1") (pintype "passive"))
      (node (ref "J4") (pin "4") (pinfunction "4_4") (pintype "passive"))
      (node (ref "J5") (pin "1") (pinfunction "1_1") (pintype "passive"))
      (node (ref "J6") (pin "4") (pinfunction "4_4") (pintype "passive"))
      (node (ref "J7") (pin "4") (pinfunction "4_4") (pintype "passive"))
      (node (ref "J8") (pin "1") (pinfunction "1_1") (pintype "passive"))
      (node (ref "P1") (pin "2") (pinfunction "2_2") (pintype "passive"))
      (node (ref "P1") (pin "3") (pinfunction "3_3") (pintype "passive"))
      (node (ref "Q15") (pin "2") (pinfunction "E_2") (pintype "passive"))
      (node (ref "Q16") (pin "2") (pinfunction "E_2") (pintype "passive"))
      (node (ref "Q21") (pin "2") (pinfunction "E_2") (pintype "passive"))
      (node (ref "Q22") (pin "2") (pinfunction "E_2") (pintype "passive"))
      (node (ref "Q23") (pin "2") (pinfunction "E_2") (pintype "passive"))
      (node (ref "Q24") (pin "2") (pinfunction "E_2") (pintype "passive"))
      (node (ref "R103") (pin "2") (pinfunction "2_2") (pintype "passive"))
      (node (ref "R105") (pin "2") (pinfunction "2_2") (pintype "passive"))
      (node (ref "R106") (pin "1") (pinfunction "1_1") (pintype "passive"))
      (node (ref "R109") (pin "1") (pinfunction "1_1") (pintype "passive"))
      (node (ref "R119") (pin "2") (pinfunction "2_2") (pintype "passive"))
      (node (ref "R123") (pin "2") (pinfunction "2_2") (pintype "passive"))
      (node (ref "R130") (pin "1") (pinfunction "1_1") (pintype "passive"))
      (node (ref "R134") (pin "1") (pinfunction "1_1") (pintype "passive"))
      (node (ref "R135") (pin "1") (pinfunction "1_1") (pintype "passive"))
      (node (ref "R136") (pin "2") (pinfunction "2_2") (pintype "passive"))
      (node (ref "R140") (pin "1") (pinfunction "1_1") (pintype "passive"))
      (node (ref "R142") (pin "1") (pinfunction "1_1") (pintype "passive"))
      (node (ref "R144") (pin "2") (pinfunction "2_2") (pintype "passive"))
      (node (ref "R145") (pin "1") (pinfunction "1_1") (pintype "passive"))
      (node (ref "R146") (pin "1") (pinfunction "1_1") (pintype "passive"))
      (node (ref "R15") (pin "2") (pinfunction "2_2") (pintype "passive"))
      (node (ref "R30") (pin "1") (pinfunction "1_1") (pintype "passive"))
      (node (ref "R31") (pin "1") (pinfunction "1_1") (pintype "passive"))
      (node (ref "R34") (pin "1") (pinfunction "1_1") (pintype "passive"))
      (node (ref "R35") (pin "1") (pinfunction "1_1") (pintype "passive"))
      (node (ref "R38") (pin "1") (pinfunction "1_1") (pintype "passive"))
      (node (ref "R54") (pin "2") (pinfunction "2_2") (pintype "passive"))
      (node (ref "R55") (pin "2") (pinfunction "2_2") (pintype "passive"))
      (node (ref "R69") (pin "1") (pinfunction "1_1") (pintype "passive"))
      (node (ref "R71") (pin "2") (pinfunction "2_2") (pintype "passive"))
      (node (ref "R79") (pin "1") (pinfunction "1_1") (pintype "passive"))
      (node (ref "R80") (pin "1") (pinfunction "1_1") (pintype "passive"))
      (node (ref "R81") (pin "1") (pinfunction "1_1") (pintype "passive"))
      (node (ref "U1") (pin "10") (pinfunction "VSS_5_10") (pintype "passive"))
      (node (ref "U1") (pin "19") (pinfunction "VSSA_19") (pintype "passive"))
      (node (ref "U1") (pin "20") (pinfunction "VREF-_20") (pintype "passive"))
      (node (ref "U1") (pin "27") (pinfunction "VSS_4_27") (pintype "passive"))
      (node (ref "U1") (pin "49") (pinfunction "VSS_1_49") (pintype "passive"))
      (node (ref "U1") (pin "74") (pinfunction "VSS_2_74") (pintype "passive"))
      (node (ref "U1") (pin "99") (pinfunction "VSS_3_99") (pintype "passive"))
      (node (ref "U10") (pin "4") (pinfunction "GND_4") (pintype "passive"))
      (node (ref "U11") (pin "1") (pinfunction "DIR_1") (pintype "passive"))
      (node (ref "U11") (pin "10") (pinfunction "GND_10") (pintype "passive"))
      (node (ref "U11") (pin "11") (pinfunction "B7_11") (pintype "passive"))
      (node (ref "U11") (pin "19") (pinfunction "~{OE}_19") (pintype "passive"))
      (node (ref "U12") (pin "4") (pinfunction "GND_4") (pintype "passive"))
      (node (ref "U13") (pin "1") (pinfunction "DIR_1") (pintype "passive"))
      (node (ref "U13") (pin "10") (pinfunction "GND_10") (pintype "passive"))
      (node (ref "U13") (pin "19") (pinfunction "~{OE}_19") (pintype "passive"))
      (node (ref "U14") (pin "2") (pinfunction "GND_2") (pintype "passive"))
      (node (ref "U15") (pin "2") (pinfunction "GND_2") (pintype "passive"))
      (node (ref "U2") (pin "12") (pinfunction "VSS_12") (pintype "passive"))
      (node (ref "U3") (pin "12") (pinfunction "VSS_12") (pintype "passive"))
      (node (ref "U4") (pin "4") (pinfunction "GND_4") (pintype "passive"))
      (node (ref "U5") (pin "7") (pinfunction "GND_7") (pintype "power_in"))
      (node (ref "U6") (pin "7") (pinfunction "GND_7") (pintype "power_in"))
      (node (ref "U7") (pin "1") (pinfunction "DIR_1") (pintype "passive"))
      (node (ref "U7") (pin "10") (pinfunction "GND_10") (pintype "passive"))
      (node (ref "U7") (pin "11") (pinfunction "B7_11") (pintype "passive"))
      (node (ref "U7") (pin "12") (pinfunction "B6_12") (pintype "passive"))
      (node (ref "U7") (pin "13") (pinfunction "B5_13") (pintype "passive"))
      (node (ref "U7") (pin "14") (pinfunction "B4_14") (pintype "passive"))
      (node (ref "U7") (pin "19") (pinfunction "~{OE}_19") (pintype "passive"))
      (node (ref "U8") (pin "7") (pinfunction "GND_7") (pintype "power_in"))
      (node (ref "U9") (pin "4") (pinfunction "GND_4") (pintype "passive"))
    )
    (net (code "129") (name "Net-(C40-Pad1)") (class "Default")
      (node (ref "C40") (pin "1") (pinfunction "1_1") (pintype "passive"))
      (node (ref "J4") (pin "3") (pinfunction "3_3") (pintype "passive"))
      (node (ref "R56") (pin "1") (pinfunction "1_1") (pintype "passive"))
      (node (ref "R58") (pin "1") (pinfunction "1_1") (pintype "passive"))
    )
    (net (code "130") (name "Net-(C41-Pad1)") (class "Default")
      (node (ref "C41") (pin "1") (pinfunction "1_1") (pintype "passive"))
      (node (ref "J5") (pin "4") (pinfunction "4_4") (pintype "passive"))
      (node (ref "R57") (pin "1") (pinfunction "1_1") (pintype "passive"))
      (node (ref "R59") (pin "1") (pinfunction "1_1") (pintype "passive"))
    )
    (net (code "131") (name "Net-(C55-Pad1)") (class "Default")
      (node (ref "C55") (pin "1") (pinfunction "1_1") (pintype "passive"))
      (node (ref "R68") (pin "2") (pinfunction "2_2") (pintype "passive"))
      (node (ref "R70") (pin "2") (pinfunction "2_2") (pintype "passive"))
      (node (ref "R71") (pin "1") (pinfunction "1_1") (pintype "passive"))
    )
    (net (code "132") (name "Net-(C81-Pad1)") (class "Default")
      (node (ref "C81") (pin "1") (pinfunction "1_1") (pintype "passive"))
      (node (ref "R110") (pin "2") (pinfunction "2_2") (pintype "passive"))
      (node (ref "R138") (pin "2") (pinfunction "2_2") (pintype "passive"))
      (node (ref "R144") (pin "1") (pinfunction "1_1") (pintype "passive"))
    )
    (net (code "133") (name "Net-(D1-K)") (class "Default")
      (node (ref "C10") (pin "1") (pinfunction "1_1") (pintype "passive"))
      (node (ref "D1") (pin "2") (pinfunction "K_2") (pintype "passive"))
      (node (ref "U2") (pin "20") (pinfunction "VB3_20") (pintype "passive"))
    )
    (net (code "134") (name "Net-(D2-K)") (class "Default")
      (node (ref "C11") (pin "1") (pinfunction "1_1") (pintype "passive"))
      (node (ref "D2") (pin "2") (pinfunction "K_2") (pintype "passive"))
      (node (ref "U3") (pin "20") (pinfunction "VB3_20") (pintype "passive"))
    )
    (net (code "135") (name "Net-(D3-K)") (class "Default")
      (node (ref "C8") (pin "1") (pinfunction "1_1") (pintype "passive"))
      (node (ref "D3") (pin "2") (pinfunction "K_2") (pintype "passive"))
      (node (ref "U2") (pin "24") (pinfunction "VB2_24") (pintype "passive"))
    )
    (net (code "136") (name "Net-(D4-K)") (class "Default")
      (node (ref "C9") (pin "1") (pinfunction "1_1") (pintype "passive"))
      (node (ref "D4") (pin "2") (pinfunction "K_2") (pintype "passive"))
      (node (ref "U3") (pin "24") (pinfunction "VB2_24") (pintype "passive"))
    )
    (net (code "137") (name "Net-(D5-K)") (class "Default")
      (node (ref "C5") (pin "1") (pinfunction "1_1") (pintype "passive"))
      (node (ref "D5") (pin "2") (pinfunction "K_2") (pintype "passive"))
      (node (ref "U2") (pin "28") (pinfunction "VB1_28") (pintype "passive"))
    )
    (net (code "138") (name "Net-(D6-K)") (class "Default")
      (node (ref "C6") (pin "1") (pinfunction "1_1") (pintype "passive"))
      (node (ref "D6") (pin "2") (pinfunction "K_2") (pintype "passive"))
      (node (ref "U3") (pin "28") (pinfunction "VB1_28") (pintype "passive"))
    )
    (net (code "139") (name "Net-(D9-A)") (class "Default")
      (node (ref "D9") (pin "1") (pinfunction "A_1") (pintype "passive"))
      (node (ref "R152") (pin "2") (pinfunction "2_2") (pintype "passive"))
      (node (ref "R34") (pin "2") (pinfunction "2_2") (pintype "passive"))
      (node (ref "U2") (pin "10") (pinfunction "EN_10") (pintype "passive"))
    )
    (net (code "140") (name "Net-(D10-A)") (class "Default")
      (node (ref "D10") (pin "1") (pinfunction "A_1") (pintype "passive"))
      (node (ref "R13") (pin "2") (pinfunction "2_2") (pintype "passive"))
      (node (ref "R35") (pin "2") (pinfunction "2_2") (pintype "passive"))
      (node (ref "U3") (pin "10") (pinfunction "EN_10") (pintype "passive"))
    )
    (net (code "141") (name "Net-(D12-A)") (class "Default")
      (node (ref "D12") (pin "1") (pinfunction "A_1") (pintype "passive"))
      (node (ref "L1") (pin "2") (pinfunction "2_2") (pintype "passive"))
      (node (ref "U14") (pin "1") (pinfunction "LX_1") (pintype "passive"))
    )
    (net (code "142") (name "Net-(Q13-NG1)") (class "Default")
      (node (ref "Q13") (pin "2") (pinfunction "NG1_2") (pintype "passive"))
      (node (ref "R101") (pin "2") (pinfunction "2_2") (pintype "passive"))
      (node (ref "R107") (pin "1") (pinfunction "1_1") (pintype "passive"))
    )
    (net (code "143") (name "Net-(Q13-NS1)") (class "Default")
      (node (ref "Q13") (pin "1") (pinfunction "NS1_1") (pintype "passive"))
      (node (ref "Q14") (pin "1") (pinfunction "NS1_1") (pintype "passive"))
      (node (ref "Q19") (pin "1") (pinfunction "NS1_1") (pintype "passive"))
      (node (ref "Q20") (pin "1") (pinfunction "NS1_1") (pintype "passive"))
      (node (ref "R100") (pin "1") (pinfunction "1_1") (pintype "passive"))
      (node (ref "R101") (pin "1") (pinfunction "1_1") (pintype "passive"))
      (node (ref "R128") (pin "1") (pinfunction "1_1") (pintype "passive"))
      (node (ref "R129") (pin "1") (pinfunction "1_1") (pintype "passive"))
      (node (ref "R139") (pin "2") (pinfunction "2_2") (pintype "passive"))
      (node (ref "R145") (pin "2") (pinfunction "2_2") (pintype "passive"))
    )
    (net (code "144") (name "Net-(Q13-PG2)") (class "Default")
      (node (ref "Q13") (pin "4") (pinfunction "PG2_4") (pintype "passive"))
      (node (ref "R88") (pin "1") (pinfunction "1_1") (pintype "passive"))
      (node (ref "R94") (pin "2") (pinfunction "2_2") (pintype "passive"))
    )
    (net (code "145") (name "Net-(Q14-NG1)") (class "Default")
      (node (ref "Q14") (pin "2") (pinfunction "NG1_2") (pintype "passive"))
      (node (ref "R100") (pin "2") (pinfunction "2_2") (pintype "passive"))
      (node (ref "R108") (pin "1") (pinfunction "1_1") (pintype "passive"))
    )
    (net (code "146") (name "Net-(Q14-PG2)") (class "Default")
      (node (ref "Q14") (pin "4") (pinfunction "PG2_4") (pintype "passive"))
      (node (ref "R89") (pin "1") (pinfunction "1_1") (pintype "passive"))
      (node (ref "R97") (pin "2") (pinfunction "2_2") (pintype "passive"))
    )
    (net (code "147") (name "Net-(Q15-B)") (class "Default")
      (node (ref "Q15") (pin "1") (pinfunction "B_1") (pintype "passive"))
      (node (ref "R102") (pin "2") (pinfunction "2_2") (pintype "passive"))
      (node (ref "R109") (pin "2") (pinfunction "2_2") (pintype "passive"))
    )
    (net (code "148") (name "Net-(Q15-C)") (class "Default")
      (node (ref "Q15") (pin "3") (pinfunction "C_3") (pintype "passive"))
      (node (ref "R97") (pin "1") (pinfunction "1_1") (pintype "passive"))
    )
    (net (code "149") (name "Net-(Q16-B)") (class "Default")
      (node (ref "Q16") (pin "1") (pinfunction "B_1") (pintype "passive"))
      (node (ref "R104") (pin "1") (pinfunction "1_1") (pintype "passive"))
      (node (ref "R106") (pin "2") (pinfunction "2_2") (pintype "passive"))
    )
    (net (code "150") (name "Net-(Q16-C)") (class "Default")
      (node (ref "Q16") (pin "3") (pinfunction "C_3") (pintype "passive"))
      (node (ref "R94") (pin "1") (pinfunction "1_1") (pintype "passive"))
    )
    (net (code "151") (name "Net-(Q17-NG1)") (class "Default")
      (node (ref "Q17") (pin "2") (pinfunction "NG1_2") (pintype "passive"))
      (node (ref "R121") (pin "1") (pinfunction "1_1") (pintype "passive"))
      (node (ref "R132") (pin "1") (pinfunction "1_1") (pintype "passive"))
    )
    (net (code "152") (name "Net-(Q17-NS1)") (class "Default")
      (node (ref "Q17") (pin "1") (pinfunction "NS1_1") (pintype "passive"))
      (node (ref "Q18") (pin "1") (pinfunction "NS1_1") (pintype "passive"))
      (node (ref "R121") (pin "2") (pinfunction "2_2") (pintype "passive"))
      (node (ref "R122") (pin "2") (pinfunction "2_2") (pintype "passive"))
      (node (ref "R127") (pin "2") (pinfunction "2_2") (pintype "passive"))
      (node (ref "R135") (pin "2") (pinfunction "2_2") (pintype "passive"))
    )
    (net (code "153") (name "Net-(Q17-PG2)") (class "Default")
      (node (ref "Q17") (pin "4") (pinfunction "PG2_4") (pintype "passive"))
      (node (ref "R111") (pin "2") (pinfunction "2_2") (pintype "passive"))
      (node (ref "R117") (pin "2") (pinfunction "2_2") (pintype "passive"))
    )
    (net (code "154") (name "Net-(Q18-NG1)") (class "Default")
      (node (ref "Q18") (pin "2") (pinfunction "NG1_2") (pintype "passive"))
      (node (ref "R122") (pin "1") (pinfunction "1_1") (pintype "passive"))
      (node (ref "R133") (pin "1") (pinfunction "1_1") (pintype "passive"))
    )
    (net (code "155") (name "Net-(Q18-PG2)") (class "Default")
      (node (ref "Q18") (pin "4") (pinfunction "PG2_4") (pintype "passive"))
      (node (ref "R112") (pin "2") (pinfunction "2_2") (pintype "passive"))
      (node (ref "R118") (pin "1") (pinfunction "1_1") (pintype "passive"))
    )
    (net (code "156") (name "Net-(Q19-NG1)") (class "Default")
      (node (ref "Q19") (pin "2") (pinfunction "NG1_2") (pintype "passive"))
      (node (ref "R128") (pin "2") (pinfunction "2_2") (pintype "passive"))
      (node (ref "R141") (pin "1") (pinfunction "1_1") (pintype "passive"))
    )
    (net (code "157") (name "Net-(Q19-PG2)") (class "Default")
      (node (ref "Q19") (pin "4") (pinfunction "PG2_4") (pintype "passive"))
      (node (ref "R115") (pin "1") (pinfunction "1_1") (pintype "passive"))
      (node (ref "R120") (pin "2") (pinfunction "2_2") (pintype "passive"))
    )
    (net (code "158") (name "Net-(Q20-NG1)") (class "Default")
      (node (ref "Q20") (pin "2") (pinfunction "NG1_2") (pintype "passive"))
      (node (ref "R129") (pin "2") (pinfunction "2_2") (pintype "passive"))
      (node (ref "R143") (pin "1") (pinfunction "1_1") (pintype "passive"))
    )
    (net (code "159") (name "Net-(Q20-PG2)") (class "Default")
      (node (ref "Q20") (pin "4") (pinfunction "PG2_4") (pintype "passive"))
      (node (ref "R116") (pin "1") (pinfunction "1_1") (pintype "passive"))
      (node (ref "R124") (pin "2") (pinfunction "2_2") (pintype "passive"))
    )
    (net (code "160") (name "Net-(Q21-B)") (class "Default")
      (node (ref "Q21") (pin "1") (pinfunction "B_1") (pintype "passive"))
      (node (ref "R126") (pin "1") (pinfunction "1_1") (pintype "passive"))
      (node (ref "R130") (pin "2") (pinfunction "2_2") (pintype "passive"))
    )
    (net (code "161") (name "Net-(Q21-C)") (class "Default")
      (node (ref "Q21") (pin "3") (pinfunction "C_3") (pintype "passive"))
      (node (ref "R117") (pin "1") (pinfunction "1_1") (pintype "passive"))
    )
    (net (code "162") (name "Net-(Q22-B)") (class "Default")
      (node (ref "Q22") (pin "1") (pinfunction "B_1") (pintype "passive"))
      (node (ref "R125") (pin "2") (pinfunction "2_2") (pintype "passive"))
      (node (ref "R136") (pin "1") (pinfunction "1_1") (pintype "passive"))
    )
    (net (code "163") (name "Net-(Q22-C)") (class "Default")
      (node (ref "Q22") (pin "3") (pinfunction "C_3") (pintype "passive"))
      (node (ref "R118") (pin "2") (pinfunction "2_2") (pintype "passive"))
    )
    (net (code "164") (name "Net-(Q23-B)") (class "Default")
      (node (ref "Q23") (pin "1") (pinfunction "B_1") (pintype "passive"))
      (node (ref "R137") (pin "1") (pinfunction "1_1") (pintype "passive"))
      (node (ref "R140") (pin "2") (pinfunction "2_2") (pintype "passive"))
    )
    (net (code "165") (name "Net-(Q23-C)") (class "Default")
      (node (ref "Q23") (pin "3") (pinfunction "C_3") (pintype "passive"))
      (node (ref "R120") (pin "1") (pinfunction "1_1") (pintype "passive"))
    )
    (net (code "166") (name "Net-(Q24-B)") (class "Default")
      (node (ref "Q24") (pin "1") (pinfunction "B_1") (pintype "passive"))
      (node (ref "R131") (pin "2") (pinfunction "2_2") (pintype "passive"))
      (node (ref "R142") (pin "2") (pinfunction "2_2") (pintype "passive"))
    )
    (net (code "167") (name "Net-(Q24-C)") (class "Default")
      (node (ref "Q24") (pin "3") (pinfunction "C_3") (pintype "passive"))
      (node (ref "R124") (pin "1") (pinfunction "1_1") (pintype "passive"))
    )
    (net (code "168") (name "Net-(U1-BOOT0)") (class "Default")
      (node (ref "R38") (pin "2") (pinfunction "2_2") (pintype "passive"))
      (node (ref "U1") (pin "94") (pinfunction "BOOT0_94") (pintype "passive"))
    )
    (net (code "169") (name "Net-(U1-NRST)") (class "Default")
      (node (ref "C18") (pin "2") (pinfunction "2_2") (pintype "passive"))
      (node (ref "R48") (pin "1") (pinfunction "1_1") (pintype "passive"))
      (node (ref "U1") (pin "14") (pinfunction "NRST_14") (pintype "passive"))
    )
    (net (code "170") (name "Net-(U1-OSC_IN)") (class "Default")
      (node (ref "C16") (pin "2") (pinfunction "2_2") (pintype "passive"))
      (node (ref "U1") (pin "12") (pinfunction "OSC_IN_12") (pintype "passive"))
      (node (ref "X1") (pin "2") (pinfunction "2_2") (pintype "passive"))
    )
    (net (code "171") (name "Net-(U1-OSC_OUT)") (class "Default")
      (node (ref "C17") (pin "2") (pinfunction "2_2") (pintype "passive"))
      (node (ref "U1") (pin "13") (pinfunction "OSC_OUT_13") (pintype "passive"))
      (node (ref "X1") (pin "1") (pinfunction "1_1") (pintype "passive"))
    )
    (net (code "172") (name "Net-(U1-PB2{slash}BOOT1)") (class "Default")
      (node (ref "R15") (pin "1") (pinfunction "1_1") (pintype "passive"))
      (node (ref "U1") (pin "37") (pinfunction "PB2/BOOT1_37") (pintype "passive"))
    )
    (net (code "173") (name "Net-(U2-HO1)") (class "Default")
      (node (ref "R7") (pin "2") (pinfunction "2_2") (pintype "passive"))
      (node (ref "U2") (pin "27") (pinfunction "HO1_27") (pintype "passive"))
    )
    (net (code "174") (name "Net-(U2-HO2)") (class "Default")
      (node (ref "R9") (pin "2") (pinfunction "2_2") (pintype "passive"))
      (node (ref "U2") (pin "23") (pinfunction "HO2_23") (pintype "passive"))
    )
    (net (code "175") (name "Net-(U2-HO3)") (class "Default")
      (node (ref "R16") (pin "2") (pinfunction "2_2") (pintype "passive"))
      (node (ref "U2") (pin "19") (pinfunction "HO3_19") (pintype "passive"))
    )
    (net (code "176") (name "Net-(U2-ITRIP)") (class "Default")
      (node (ref "R12") (pin "2") (pinfunction "2_2") (pintype "passive"))
      (node (ref "U2") (pin "9") (pinfunction "ITRIP_9") (pintype "passive"))
    )
    (net (code "177") (name "Net-(U2-LO1)") (class "Default")
      (node (ref "R28") (pin "2") (pinfunction "2_2") (pintype "passive"))
      (node (ref "U2") (pin "16") (pinfunction "LO1_16") (pintype "passive"))
    )
    (net (code "178") (name "Net-(U2-LO2)") (class "Default")
      (node (ref "R32") (pin "2") (pinfunction "2_2") (pintype "passive"))
      (node (ref "U2") (pin "15") (pinfunction "LO2_15") (pintype "passive"))
    )
    (net (code "179") (name "Net-(U2-LO3)") (class "Default")
      (node (ref "R36") (pin "2") (pinfunction "2_2") (pintype "passive"))
      (node (ref "U2") (pin "14") (pinfunction "LO3_14") (pintype "passive"))
    )
    (net (code "180") (name "Net-(U2-RCIN)") (class "Default")
      (node (ref "C14") (pin "1") (pinfunction "1_1") (pintype "passive"))
      (node (ref "R26") (pin "2") (pinfunction "2_2") (pintype "passive"))
      (node (ref "U2") (pin "11") (pinfunction "RCIN_11") (pintype "passive"))
    )
    (net (code "181") (name "Net-(U3-HO1)") (class "Default")
      (node (ref "R8") (pin "2") (pinfunction "2_2") (pintype "passive"))
      (node (ref "U3") (pin "27") (pinfunction "HO1_27") (pintype "passive"))
    )
    (net (code "182") (name "Net-(U3-HO2)") (class "Default")
      (node (ref "R10") (pin "2") (pinfunction "2_2") (pintype "passive"))
      (node (ref "U3") (pin "23") (pinfunction "HO2_23") (pintype "passive"))
    )
    (net (code "183") (name "Net-(U3-HO3)") (class "Default")
      (node (ref "R17") (pin "2") (pinfunction "2_2") (pintype "passive"))
      (node (ref "U3") (pin "19") (pinfunction "HO3_19") (pintype "passive"))
    )
    (net (code "184") (name "Net-(U3-ITRIP)") (class "Default")
      (node (ref "R14") (pin "2") (pinfunction "2_2") (pintype "passive"))
      (node (ref "U3") (pin "9") (pinfunction "ITRIP_9") (pintype "passive"))
    )
    (net (code "185") (name "Net-(U3-LO1)") (class "Default")
      (node (ref "R29") (pin "2") (pinfunction "2_2") (pintype "passive"))
      (node (ref "U3") (pin "16") (pinfunction "LO1_16") (pintype "passive"))
    )
    (net (code "186") (name "Net-(U3-LO2)") (class "Default")
      (node (ref "R33") (pin "2") (pinfunction "2_2") (pintype "passive"))
      (node (ref "U3") (pin "15") (pinfunction "LO2_15") (pintype "passive"))
    )
    (net (code "187") (name "Net-(U3-LO3)") (class "Default")
      (node (ref "R37") (pin "2") (pinfunction "2_2") (pintype "passive"))
      (node (ref "U3") (pin "14") (pinfunction "LO3_14") (pintype "passive"))
    )
    (net (code "188") (name "Net-(U3-RCIN)") (class "Default")
      (node (ref "C15") (pin "1") (pinfunction "1_1") (pintype "passive"))
      (node (ref "R27") (pin "2") (pinfunction "2_2") (pintype "passive"))
      (node (ref "U3") (pin "11") (pinfunction "RCIN_11") (pintype "passive"))
    )
    (net (code "189") (name "Net-(U4-IN1-)") (class "Default")
      (node (ref "R52") (pin "1") (pinfunction "1_1") (pintype "passive"))
      (node (ref "R54") (pin "1") (pinfunction "1_1") (pintype "passive"))
      (node (ref "U4") (pin "2") (pinfunction "IN1-_2") (pintype "passive"))
    )
    (net (code "190") (name "Net-(U4-IN2-)") (class "Default")
      (node (ref "R53") (pin "2") (pinfunction "2_2") (pintype "passive"))
      (node (ref "R55") (pin "1") (pinfunction "1_1") (pintype "passive"))
      (node (ref "U4") (pin "6") (pinfunction "IN2-_6") (pintype "passive"))
    )
    (net (code "191") (name "Net-(U4-OUT1)") (class "Default")
      (node (ref "R39") (pin "1") (pinfunction "1_1") (pintype "passive"))
      (node (ref "R51") (pin "2") (pinfunction "2_2") (pintype "passive"))
      (node (ref "R52") (pin "2") (pinfunction "2_2") (pintype "passive"))
      (node (ref "U4") (pin "1") (pinfunction "OUT1_1") (pintype "passive"))
    )
    (net (code "192") (name "Net-(U4-OUT2)") (class "Default")
      (node (ref "R49") (pin "1") (pinfunction "1_1") (pintype "passive"))
      (node (ref "R50") (pin "1") (pinfunction "1_1") (pintype "passive"))
      (node (ref "R53") (pin "1") (pinfunction "1_1") (pintype "passive"))
      (node (ref "U4") (pin "7") (pinfunction "OUT2_7") (pintype "passive"))
    )
    (net (code "193") (name "Net-(U12-IN1-)") (class "Default")
      (node (ref "R103") (pin "1") (pinfunction "1_1") (pintype "passive"))
      (node (ref "R98") (pin "1") (pinfunction "1_1") (pintype "passive"))
      (node (ref "U12") (pin "2") (pinfunction "IN1-_2") (pintype "passive"))
    )
    (net (code "194") (name "Net-(U12-IN2-)") (class "Default")
      (node (ref "R105") (pin "1") (pinfunction "1_1") (pintype "passive"))
      (node (ref "R99") (pin "2") (pinfunction "2_2") (pintype "passive"))
      (node (ref "U12") (pin "6") (pinfunction "IN2-_6") (pintype "passive"))
    )
    (net (code "195") (name "Net-(U12-OUT1)") (class "Default")
      (node (ref "R90") (pin "1") (pinfunction "1_1") (pintype "passive"))
      (node (ref "R95") (pin "2") (pinfunction "2_2") (pintype "passive"))
      (node (ref "R98") (pin "2") (pinfunction "2_2") (pintype "passive"))
      (node (ref "U12") (pin "1") (pinfunction "OUT1_1") (pintype "passive"))
    )
    (net (code "196") (name "Net-(U12-OUT2)") (class "Default")
      (node (ref "R91") (pin "1") (pinfunction "1_1") (pintype "passive"))
      (node (ref "R96") (pin "1") (pinfunction "1_1") (pintype "passive"))
      (node (ref "R99") (pin "1") (pinfunction "1_1") (pintype "passive"))
      (node (ref "U12") (pin "7") (pinfunction "OUT2_7") (pintype "passive"))
    )
    (net (code "197") (name "Net-(U14-EN)") (class "Default")
      (node (ref "R113") (pin "2") (pinfunction "2_2") (pintype "passive"))
      (node (ref "R123") (pin "1") (pinfunction "1_1") (pintype "passive"))
      (node (ref "U14") (pin "4") (pinfunction "EN_4") (pintype "passive"))
    )
    (net (code "198") (name "Net-(U14-FB)") (class "Default")
      (node (ref "R114") (pin "2") (pinfunction "2_2") (pintype "passive"))
      (node (ref "R119") (pin "1") (pinfunction "1_1") (pintype "passive"))
      (node (ref "U14") (pin "3") (pinfunction "FB_3") (pintype "passive"))
    )
    (net (code "199") (name "VCC-3.3V-MD") (class "Default")
      (node (ref "C19") (pin "1") (pinfunction "1_1") (pintype "passive"))
      (node (ref "C32") (pin "2") (pinfunction "2_2") (pintype "passive"))
      (node (ref "C33") (pin "2") (pinfunction "2_2") (pintype "passive"))
      (node (ref "C34") (pin "2") (pinfunction "2_2") (pintype "passive"))
      (node (ref "C35") (pin "2") (pinfunction "2_2") (pintype "passive"))
      (node (ref "C37") (pin "2") (pinfunction "2_2") (pintype "passive"))
      (node (ref "C43") (pin "1") (pinfunction "1_1") (pintype "passive"))
      (node (ref "C44") (pin "2") (pinfunction "2_2") (pintype "passive"))
      (node (ref "C56") (pin "1") (pinfunction "1_1") (pintype "passive"))
      (node (ref "C68") (pin "1") (pinfunction "1_1") (pintype "passive"))
      (node (ref "C71") (pin "1") (pinfunction "1_1") (pintype "passive"))
      (node (ref "C79") (pin "1") (pinfunction "1_1") (pintype "passive"))
      (node (ref "C89") (pin "1") (pinfunction "1_1") (pintype "passive"))
      (node (ref "C90") (pin "1") (pinfunction "1_1") (pintype "passive"))
      (node (ref "C91") (pin "1") (pinfunction "1_1") (pintype "passive"))
      (node (ref "J1") (pin "1") (pinfunction "1_1") (pintype "passive"))
      (node (ref "J10") (pin "6") (pinfunction "6_6") (pintype "passive"))
      (node (ref "J8") (pin "6") (pinfunction "6_6") (pintype "passive"))
      (node (ref "R11") (pin "2") (pinfunction "2_2") (pintype "passive"))
      (node (ref "R146") (pin "2") (pinfunction "2_2") (pintype "passive"))
      (node (ref "R148") (pin "1") (pinfunction "1_1") (pintype "passive"))
      (node (ref "R151") (pin "2") (pinfunction "2_2") (pintype "passive"))
      (node (ref "R39") (pin "2") (pinfunction "2_2") (pintype "passive"))
      (node (ref "R44") (pin "2") (pinfunction "2_2") (pintype "passive"))
      (node (ref "R45") (pin "2") (pinfunction "2_2") (pintype "passive"))
      (node (ref "R46") (pin "2") (pinfunction "2_2") (pintype "passive"))
      (node (ref "R47") (pin "2") (pinfunction "2_2") (pintype "passive"))
      (node (ref "R48") (pin "2") (pinfunction "2_2") (pintype "passive"))
      (node (ref "R49") (pin "2") (pinfunction "2_2") (pintype "passive"))
      (node (ref "R58") (pin "2") (pinfunction "2_2") (pintype "passive"))
      (node (ref "R59") (pin "2") (pinfunction "2_2") (pintype "passive"))
      (node (ref "R61") (pin "1") (pinfunction "1_1") (pintype "passive"))
      (node (ref "R62") (pin "1") (pinfunction "1_1") (pintype "passive"))
      (node (ref "R63") (pin "1") (pinfunction "1_1") (pintype "passive"))
      (node (ref "R64") (pin "1") (pinfunction "1_1") (pintype "passive"))
      (node (ref "R65") (pin "1") (pinfunction "1_1") (pintype "passive"))
      (node (ref "R66") (pin "1") (pinfunction "1_1") (pintype "passive"))
      (node (ref "R67") (pin "2") (pinfunction "2_2") (pintype "passive"))
      (node (ref "R72") (pin "1") (pinfunction "1_1") (pintype "passive"))
      (node (ref "R73") (pin "1") (pinfunction "1_1") (pintype "passive"))
      (node (ref "R74") (pin "1") (pinfunction "1_1") (pintype "passive"))
      (node (ref "R75") (pin "1") (pinfunction "1_1") (pintype "passive"))
      (node (ref "R76") (pin "1") (pinfunction "1_1") (pintype "passive"))
      (node (ref "R77") (pin "1") (pinfunction "1_1") (pintype "passive"))
      (node (ref "R78") (pin "1") (pinfunction "1_1") (pintype "passive"))
      (node (ref "R82") (pin "2") (pinfunction "2_2") (pintype "passive"))
      (node (ref "R83") (pin "2") (pinfunction "2_2") (pintype "passive"))
      (node (ref "R84") (pin "2") (pinfunction "2_2") (pintype "passive"))
      (node (ref "R85") (pin "2") (pinfunction "2_2") (pintype "passive"))
      (node (ref "R90") (pin "2") (pinfunction "2_2") (pintype "passive"))
      (node (ref "R91") (pin "2") (pinfunction "2_2") (pintype "passive"))
      (node (ref "U1") (pin "100") (pinfunction "VDD_3_100") (pintype "passive"))
      (node (ref "U1") (pin "11") (pinfunction "VDD_5_11") (pintype "passive"))
      (node (ref "U1") (pin "21") (pinfunction "VREF+_21") (pintype "passive"))
      (node (ref "U1") (pin "22") (pinfunction "VDDA_22") (pintype "passive"))
      (node (ref "U1") (pin "28") (pinfunction "VDD_4_28") (pintype "passive"))
      (node (ref "U1") (pin "50") (pinfunction "VDD_1_50") (pintype "passive"))
      (node (ref "U1") (pin "6") (pinfunction "VBAT_6") (pintype "passive"))
      (node (ref "U1") (pin "75") (pinfunction "VDD_2_75") (pintype "passive"))
      (node (ref "U11") (pin "20") (pinfunction "VCC_20") (pintype "passive"))
      (node (ref "U13") (pin "20") (pinfunction "VCC_20") (pintype "passive"))
      (node (ref "U15") (pin "5") (pinfunction "OUT_5") (pintype "passive"))
      (node (ref "U7") (pin "20") (pinfunction "VCC_20") (pintype "passive"))
    )
    (net (code "200") (name "VCC-5V-MD") (class "Default")
      (node (ref "C20") (pin "2") (pinfunction "2_2") (pintype "passive"))
      (node (ref "C21") (pin "1") (pinfunction "1_1") (pintype "passive"))
      (node (ref "C22") (pin "2") (pinfunction "2_2") (pintype "passive"))
      (node (ref "C38") (pin "1") (pinfunction "1_1") (pintype "passive"))
      (node (ref "C39") (pin "1") (pinfunction "1_1") (pintype "passive"))
      (node (ref "C42") (pin "2") (pinfunction "2_2") (pintype "passive"))
      (node (ref "C57") (pin "2") (pinfunction "2_2") (pintype "passive"))
      (node (ref "C65") (pin "2") (pinfunction "2_2") (pintype "passive"))
      (node (ref "C66") (pin "2") (pinfunction "2_2") (pintype "passive"))
      (node (ref "C67") (pin "2") (pinfunction "2_2") (pintype "passive"))
      (node (ref "C7") (pin "2") (pinfunction "2_2") (pintype "passive"))
      (node (ref "C75") (pin "1") (pinfunction "1_1") (pintype "passive"))
      (node (ref "C76") (pin "1") (pinfunction "1_1") (pintype "passive"))
      (node (ref "C82") (pin "1") (pinfunction "1_1") (pintype "passive"))
      (node (ref "C88") (pin "2") (pinfunction "2_2") (pintype "passive"))
      (node (ref "J1") (pin "9") (pinfunction "9_9") (pintype "passive"))
      (node (ref "J2") (pin "5") (pinfunction "5_5") (pintype "passive"))
      (node (ref "J3") (pin "5") (pinfunction "5_5") (pintype "passive"))
      (node (ref "J6") (pin "1") (pinfunction "1_1") (pintype "passive"))
      (node (ref "J7") (pin "1") (pinfunction "1_1") (pintype "passive"))
      (node (ref "L1") (pin "1") (pinfunction "1_1") (pintype "passive"))
      (node (ref "P1") (pin "7") (pinfunction "7_7") (pintype "passive"))
      (node (ref "R113") (pin "1") (pinfunction "1_1") (pintype "passive"))
      (node (ref "R13") (pin "1") (pinfunction "1_1") (pintype "passive"))
      (node (ref "R152") (pin "1") (pinfunction "1_1") (pintype "passive"))
      (node (ref "R40") (pin "2") (pinfunction "2_2") (pintype "passive"))
      (node (ref "R41") (pin "2") (pinfunction "2_2") (pintype "passive"))
      (node (ref "R42") (pin "2") (pinfunction "2_2") (pintype "passive"))
      (node (ref "R43") (pin "2") (pinfunction "2_2") (pintype "passive"))
      (node (ref "R56") (pin "2") (pinfunction "2_2") (pintype "passive"))
      (node (ref "R57") (pin "2") (pinfunction "2_2") (pintype "passive"))
      (node (ref "U10") (pin "8") (pinfunction "VCC_8") (pintype "passive"))
      (node (ref "U12") (pin "8") (pinfunction "VCC_8") (pintype "passive"))
      (node (ref "U14") (pin "5") (pinfunction "VCC_5") (pintype "passive"))
      (node (ref "U15") (pin "1") (pinfunction "VIN_1") (pintype "passive"))
      (node (ref "U15") (pin "3") (pinfunction "CE_3") (pintype "passive"))
      (node (ref "U4") (pin "8") (pinfunction "VCC_8") (pintype "passive"))
      (node (ref "U5") (pin "14") (pinfunction "VCC_14") (pintype "power_in"))
      (node (ref "U6") (pin "11") (pinfunction "A_11") (pintype "input"))
      (node (ref "U6") (pin "13") (pinfunction "A_13") (pintype "input"))
      (node (ref "U6") (pin "14") (pinfunction "VCC_14") (pintype "power_in"))
      (node (ref "U6") (pin "9") (pinfunction "A_9") (pintype "input"))
      (node (ref "U8") (pin "10") (pinfunction "B_10") (pintype "input"))
      (node (ref "U8") (pin "12") (pinfunction "A_12") (pintype "input"))
      (node (ref "U8") (pin "13") (pinfunction "B_13") (pintype "input"))
      (node (ref "U8") (pin "14") (pinfunction "VCC_14") (pintype "power_in"))
      (node (ref "U8") (pin "9") (pinfunction "A_9") (pintype "input"))
      (node (ref "U9") (pin "8") (pinfunction "VCC_8") (pintype "passive"))
    )
    (net (code "201") (name "VCC-24V-HW") (class "Default")
      (node (ref "C53") (pin "1") (pinfunction "1_1") (pintype "passive"))
      (node (ref "C72") (pin "2") (pinfunction "2_2") (pintype "passive"))
      (node (ref "C80") (pin "2") (pinfunction "2_2") (pintype "passive"))
      (node (ref "F2") (pin "2") (pinfunction "2_2") (pintype "passive"))
      (node (ref "Q13") (pin "3") (pinfunction "PS2_3") (pintype "passive"))
      (node (ref "Q14") (pin "3") (pinfunction "PS2_3") (pintype "passive"))
      (node (ref "Q17") (pin "3") (pinfunction "PS2_3") (pintype "passive"))
      (node (ref "Q18") (pin "3") (pinfunction "PS2_3") (pintype "passive"))
      (node (ref "Q19") (pin "3") (pinfunction "PS2_3") (pintype "passive"))
      (node (ref "Q20") (pin "3") (pinfunction "PS2_3") (pintype "passive"))
      (node (ref "R110") (pin "1") (pinfunction "1_1") (pintype "passive"))
      (node (ref "R111") (pin "1") (pinfunction "1_1") (pintype "passive"))
      (node (ref "R112") (pin "1") (pinfunction "1_1") (pintype "passive"))
      (node (ref "R115") (pin "2") (pinfunction "2_2") (pintype "passive"))
      (node (ref "R116") (pin "2") (pinfunction "2_2") (pintype "passive"))
      (node (ref "R88") (pin "2") (pinfunction "2_2") (pintype "passive"))
      (node (ref "R89") (pin "2") (pinfunction "2_2") (pintype "passive"))
    )
    (net (code "202") (name "VCC-24V-MD") (class "Default")
      (node (ref "C54") (pin "1") (pinfunction "1_1") (pintype "passive"))
      (node (ref "C92") (pin "2") (pinfunction "2_2") (pintype "passive"))
      (node (ref "C93") (pin "2") (pinfunction "2_2") (pintype "passive"))
      (node (ref "F1") (pin "2") (pinfunction "2_2") (pintype "passive"))
      (node (ref "Q1") (pin "3") (pinfunction "D_3") (pintype "input"))
      (node (ref "Q2") (pin "3") (pinfunction "D_3") (pintype "input"))
      (node (ref "Q3") (pin "3") (pinfunction "D_3") (pintype "input"))
      (node (ref "Q4") (pin "3") (pinfunction "D_3") (pintype "input"))
      (node (ref "Q5") (pin "3") (pinfunction "D_3") (pintype "input"))
      (node (ref "Q6") (pin "3") (pinfunction "D_3") (pintype "input"))
      (node (ref "R68") (pin "1") (pinfunction "1_1") (pintype "passive"))
    )
    (net (code "203") (name "VCC-BATT-BLDC") (class "Default")
      (node (ref "C86") (pin "1") (pinfunction "1_1") (pintype "passive"))
      (node (ref "F1") (pin "1") (pinfunction "1_1") (pintype "passive"))
      (node (ref "F2") (pin "1") (pinfunction "1_1") (pintype "passive"))
      (node (ref "P1") (pin "1") (pinfunction "1_1") (pintype "passive"))
    )
    (net (code "204") (name "unconnected-(J1-Pad4)") (class "Default")
      (node (ref "J1") (pin "4") (pinfunction "4_4") (pintype "passive"))
    )
    (net (code "205") (name "unconnected-(J1-Pad5)") (class "Default")
      (node (ref "J1") (pin "5") (pinfunction "5_5") (pintype "passive"))
    )
    (net (code "206") (name "unconnected-(J7-Pad5)") (class "Default")
      (node (ref "J7") (pin "5") (pinfunction "5_5") (pintype "passive"))
    )
    (net (code "207") (name "unconnected-(LOGO1-Pad1)") (class "Default")
      (node (ref "LOGO1") (pin "1") (pinfunction "1_1") (pintype "passive"))
    )
    (net (code "208") (name "unconnected-(LOGO1-Pad2)") (class "Default")
      (node (ref "LOGO1") (pin "2") (pinfunction "2_2") (pintype "passive"))
    )
    (net (code "209") (name "unconnected-(U1-NC-Pad73)") (class "Default")
      (node (ref "U1") (pin "73") (pinfunction "NC_73") (pintype "passive"))
    )
    (net (code "210") (name "unconnected-(U1-PB3{slash}JTDO-Pad89)") (class "Default")
      (node (ref "U1") (pin "89") (pinfunction "PB3/JTDO_89") (pintype "passive"))
    )
    (net (code "211") (name "unconnected-(U1-PB8-Pad95)") (class "Default")
      (node (ref "U1") (pin "95") (pinfunction "PB8_95") (pintype "passive"))
    )
    (net (code "212") (name "unconnected-(U1-PB9-Pad96)") (class "Default")
      (node (ref "U1") (pin "96") (pinfunction "PB9_96") (pintype "passive"))
    )
    (net (code "213") (name "unconnected-(U1-PB12-Pad51)") (class "Default")
      (node (ref "U1") (pin "51") (pinfunction "PB12_51") (pintype "passive"))
    )
    (net (code "214") (name "unconnected-(U1-PB13-Pad52)") (class "Default")
      (node (ref "U1") (pin "52") (pinfunction "PB13_52") (pintype "passive"))
    )
    (net (code "215") (name "unconnected-(U1-PC5-Pad34)") (class "Default")
      (node (ref "U1") (pin "34") (pinfunction "PC5_34") (pintype "passive"))
    )
    (net (code "216") (name "unconnected-(U1-PC15-OSC32_OUT-Pad9)") (class "Default")
      (node (ref "U1") (pin "9") (pinfunction "PC15-OSC32_OUT_9") (pintype "passive"))
    )
    (net (code "217") (name "unconnected-(U1-PD1-Pad82)") (class "Default")
      (node (ref "U1") (pin "82") (pinfunction "PD1_82") (pintype "passive"))
    )
    (net (code "218") (name "unconnected-(U1-PD2-Pad83)") (class "Default")
      (node (ref "U1") (pin "83") (pinfunction "PD2_83") (pintype "passive"))
    )
    (net (code "219") (name "unconnected-(U1-PD3-Pad84)") (class "Default")
      (node (ref "U1") (pin "84") (pinfunction "PD3_84") (pintype "passive"))
    )
    (net (code "220") (name "unconnected-(U1-PD4-Pad85)") (class "Default")
      (node (ref "U1") (pin "85") (pinfunction "PD4_85") (pintype "passive"))
    )
    (net (code "221") (name "unconnected-(U1-PD5-Pad86)") (class "Default")
      (node (ref "U1") (pin "86") (pinfunction "PD5_86") (pintype "passive"))
    )
    (net (code "222") (name "unconnected-(U1-PD6-Pad87)") (class "Default")
      (node (ref "U1") (pin "87") (pinfunction "PD6_87") (pintype "passive"))
    )
    (net (code "223") (name "unconnected-(U1-PD7-Pad88)") (class "Default")
      (node (ref "U1") (pin "88") (pinfunction "PD7_88") (pintype "passive"))
    )
    (net (code "224") (name "unconnected-(U1-PE0-Pad97)") (class "Default")
      (node (ref "U1") (pin "97") (pinfunction "PE0_97") (pintype "passive"))
    )
    (net (code "225") (name "unconnected-(U1-PE1-Pad98)") (class "Default")
      (node (ref "U1") (pin "98") (pinfunction "PE1_98") (pintype "passive"))
    )
    (net (code "226") (name "unconnected-(U1-PE3-Pad2)") (class "Default")
      (node (ref "U1") (pin "2") (pinfunction "PE3_2") (pintype "passive"))
    )
    (net (code "227") (name "unconnected-(U1-PE4-Pad3)") (class "Default")
      (node (ref "U1") (pin "3") (pinfunction "PE4_3") (pintype "passive"))
    )
    (net (code "228") (name "unconnected-(U2-N{slash}C-Pad17)") (class "Default")
      (node (ref "U2") (pin "17") (pinfunction "N/C_17") (pintype "passive"))
    )
    (net (code "229") (name "unconnected-(U2-N{slash}C-Pad21)") (class "Default")
      (node (ref "U2") (pin "21") (pinfunction "N/C_21") (pintype "passive"))
    )
    (net (code "230") (name "unconnected-(U2-N{slash}C-Pad25)") (class "Default")
      (node (ref "U2") (pin "25") (pinfunction "N/C_25") (pintype "passive"))
    )
    (net (code "231") (name "unconnected-(U3-N{slash}C-Pad17)") (class "Default")
      (node (ref "U3") (pin "17") (pinfunction "N/C_17") (pintype "passive"))
    )
    (net (code "232") (name "unconnected-(U3-N{slash}C-Pad21)") (class "Default")
      (node (ref "U3") (pin "21") (pinfunction "N/C_21") (pintype "passive"))
    )
    (net (code "233") (name "unconnected-(U3-N{slash}C-Pad25)") (class "Default")
      (node (ref "U3") (pin "25") (pinfunction "N/C_25") (pintype "passive"))
    )
    (net (code "234") (name "unconnected-(U6D-Y-Pad8)") (class "Default")
      (node (ref "U6") (pin "8") (pinfunction "Y_8") (pintype "output"))
    )
    (net (code "235") (name "unconnected-(U6E-Y-Pad10)") (class "Default")
      (node (ref "U6") (pin "10") (pinfunction "Y_10") (pintype "output"))
    )
    (net (code "236") (name "unconnected-(U6F-Y-Pad12)") (class "Default")
      (node (ref "U6") (pin "12") (pinfunction "Y_12") (pintype "output"))
    )
    (net (code "237") (name "unconnected-(U7-A4-Pad6)") (class "Default")
      (node (ref "U7") (pin "6") (pinfunction "A4_6") (pintype "passive"))
    )
    (net (code "238") (name "unconnected-(U7-A5-Pad7)") (class "Default")
      (node (ref "U7") (pin "7") (pinfunction "A5_7") (pintype "passive"))
    )
    (net (code "239") (name "unconnected-(U7-A6-Pad8)") (class "Default")
      (node (ref "U7") (pin "8") (pinfunction "A6_8") (pintype "passive"))
    )
    (net (code "240") (name "unconnected-(U7-A7-Pad9)") (class "Default")
      (node (ref "U7") (pin "9") (pinfunction "A7_9") (pintype "passive"))
    )
    (net (code "241") (name "unconnected-(U8C-Y-Pad8)") (class "Default")
      (node (ref "U8") (pin "8") (pinfunction "Y_8") (pintype "output"))
    )
    (net (code "242") (name "unconnected-(U8D-Y-Pad11)") (class "Default")
      (node (ref "U8") (pin "11") (pinfunction "Y_11") (pintype "output"))
    )
    (net (code "243") (name "unconnected-(U11-A7-Pad9)") (class "Default")
      (node (ref "U11") (pin "9") (pinfunction "A7_9") (pintype "passive"))
    )
    (net (code "244") (name "unconnected-(U14-OC-Pad6)") (class "Default")
      (node (ref "U14") (pin "6") (pinfunction "OC_6") (pintype "passive"))
    )
    (net (code "245") (name "unconnected-(U15-NC-Pad4)") (class "Default")
      (node (ref "U15") (pin "4") (pinfunction "NC_4") (pintype "passive"))
    )
  )
)
